# HackerboatControlBoard.net
KiCad netlist of a schematic drawn in EAGLE
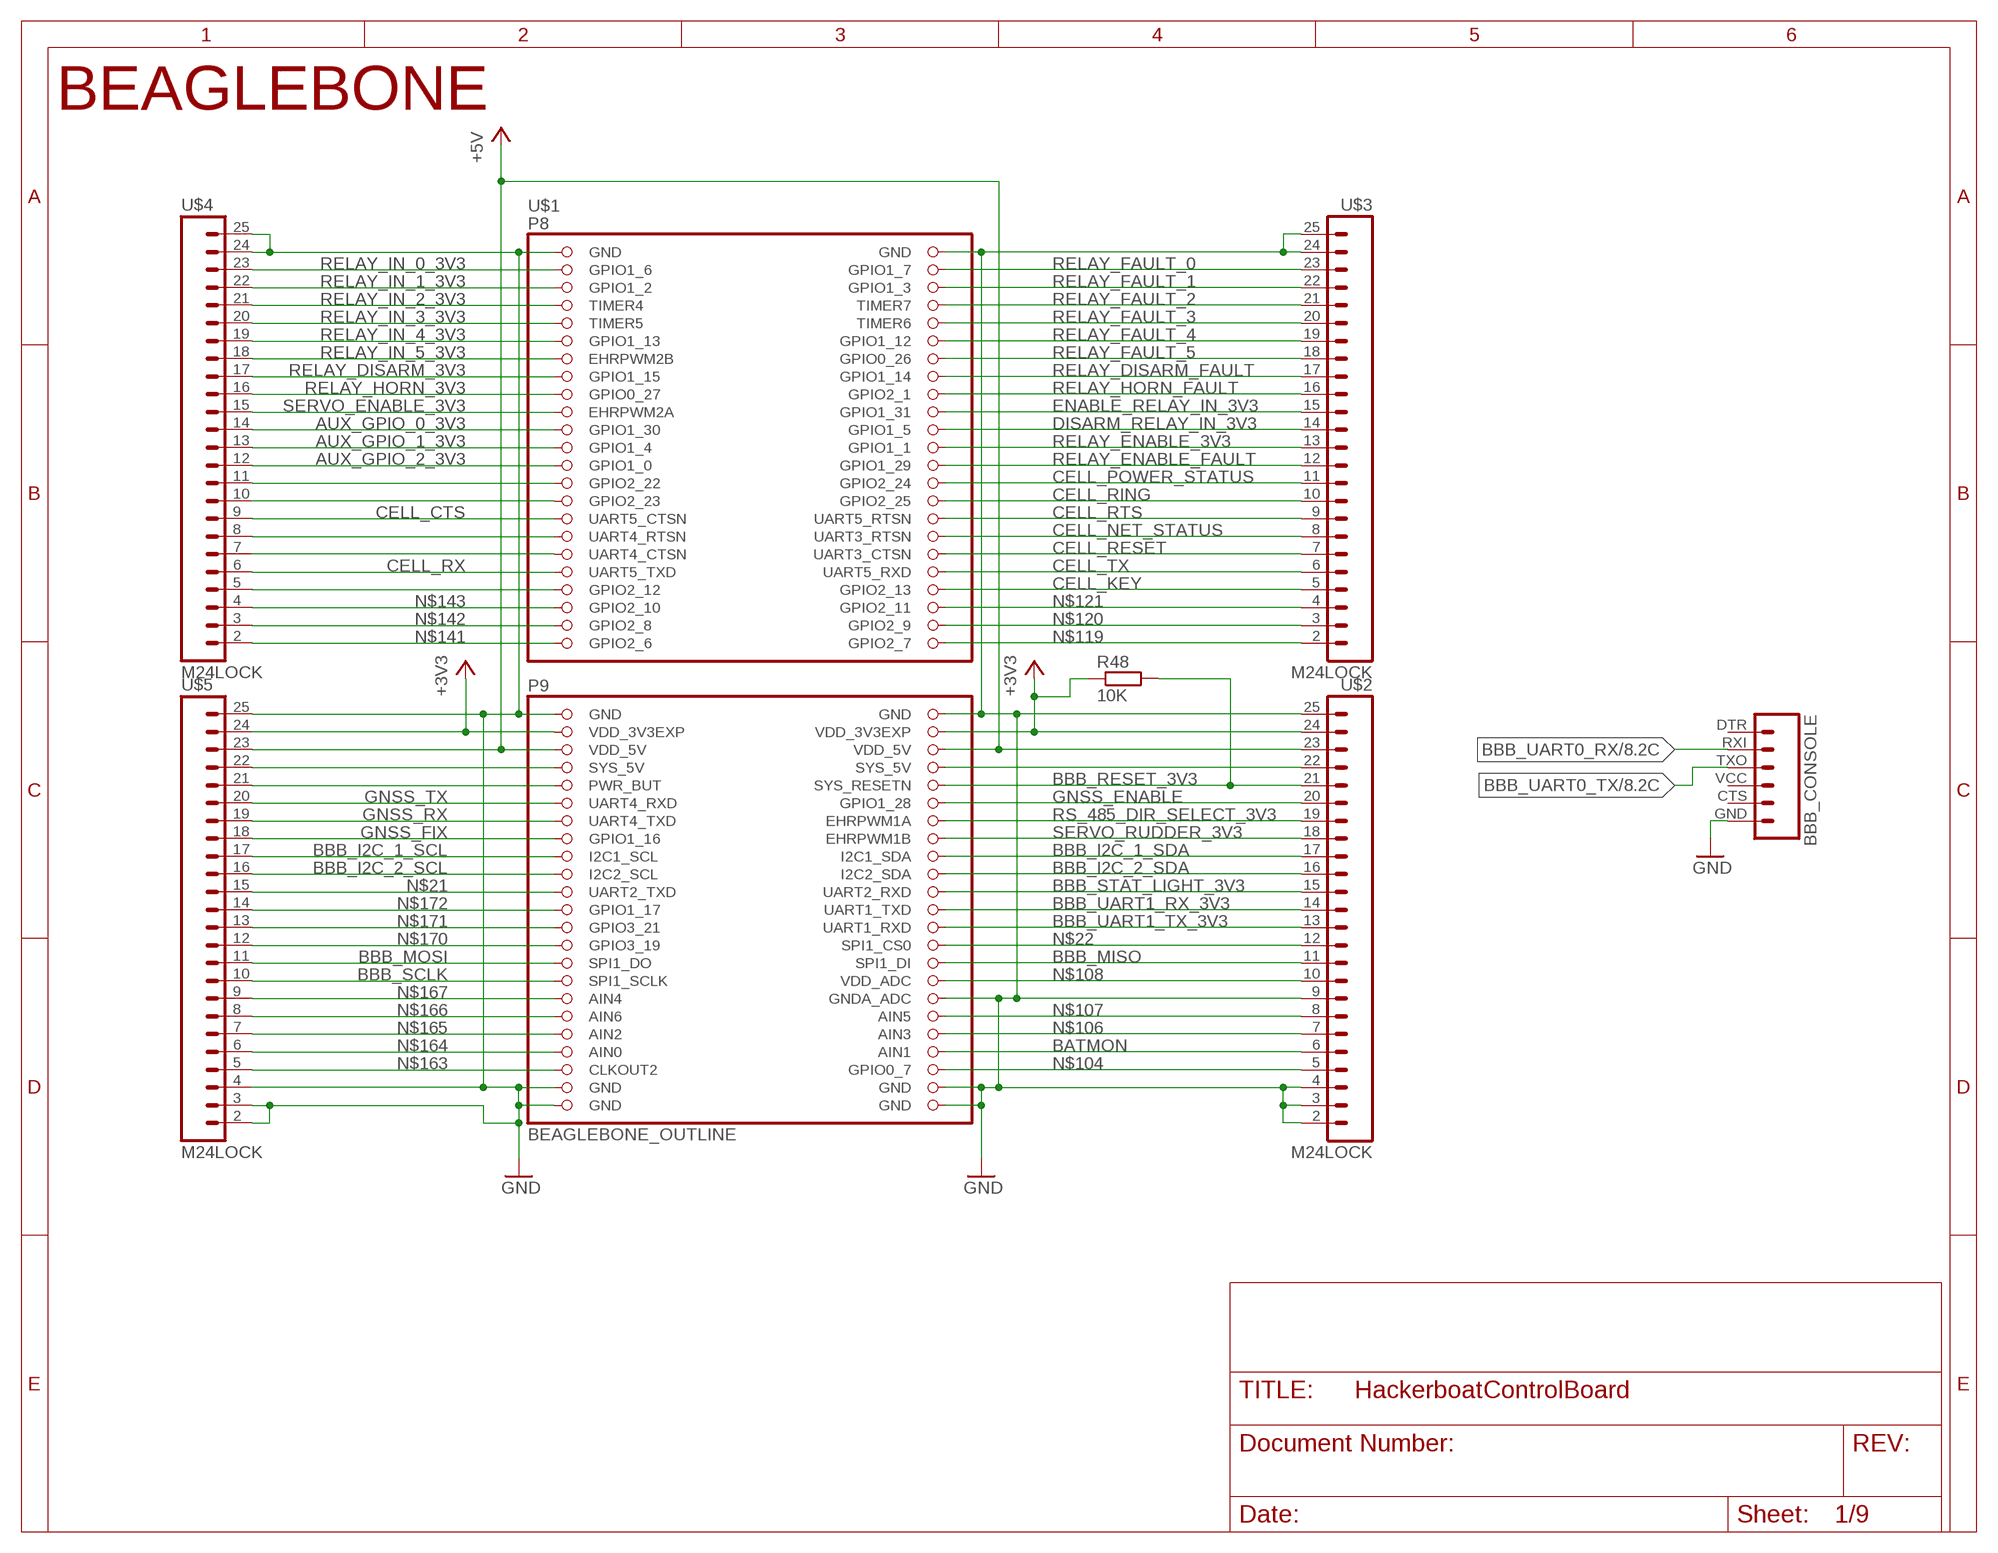
[diagram p0: schematic, sheet 1]
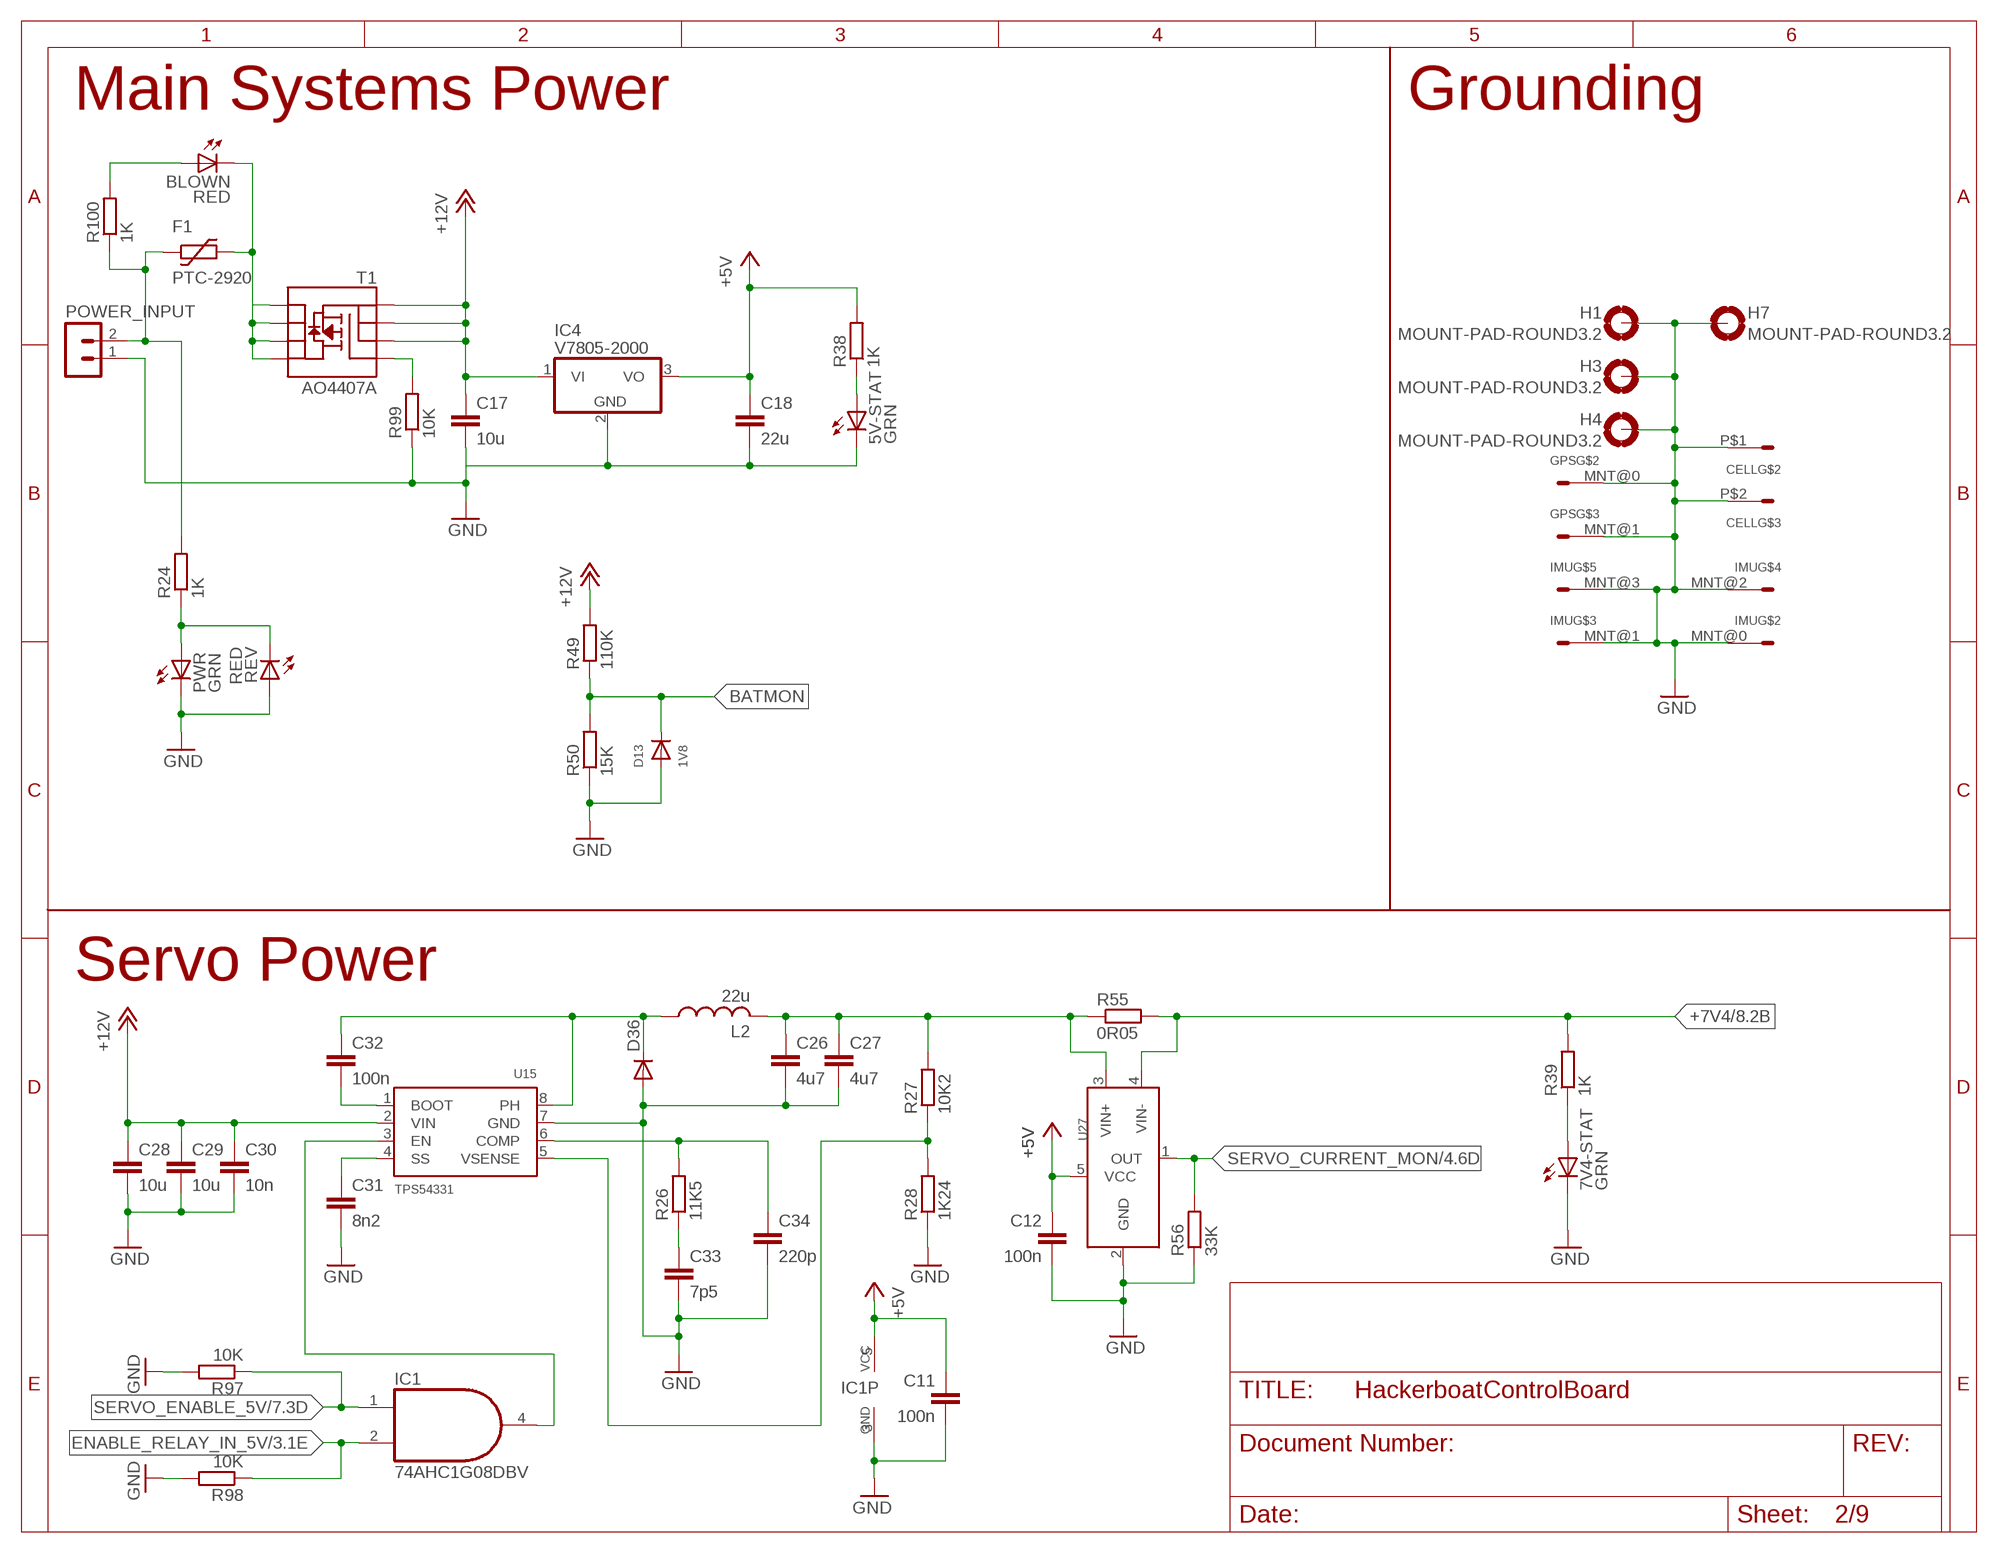
[diagram p1: schematic, sheet 2]
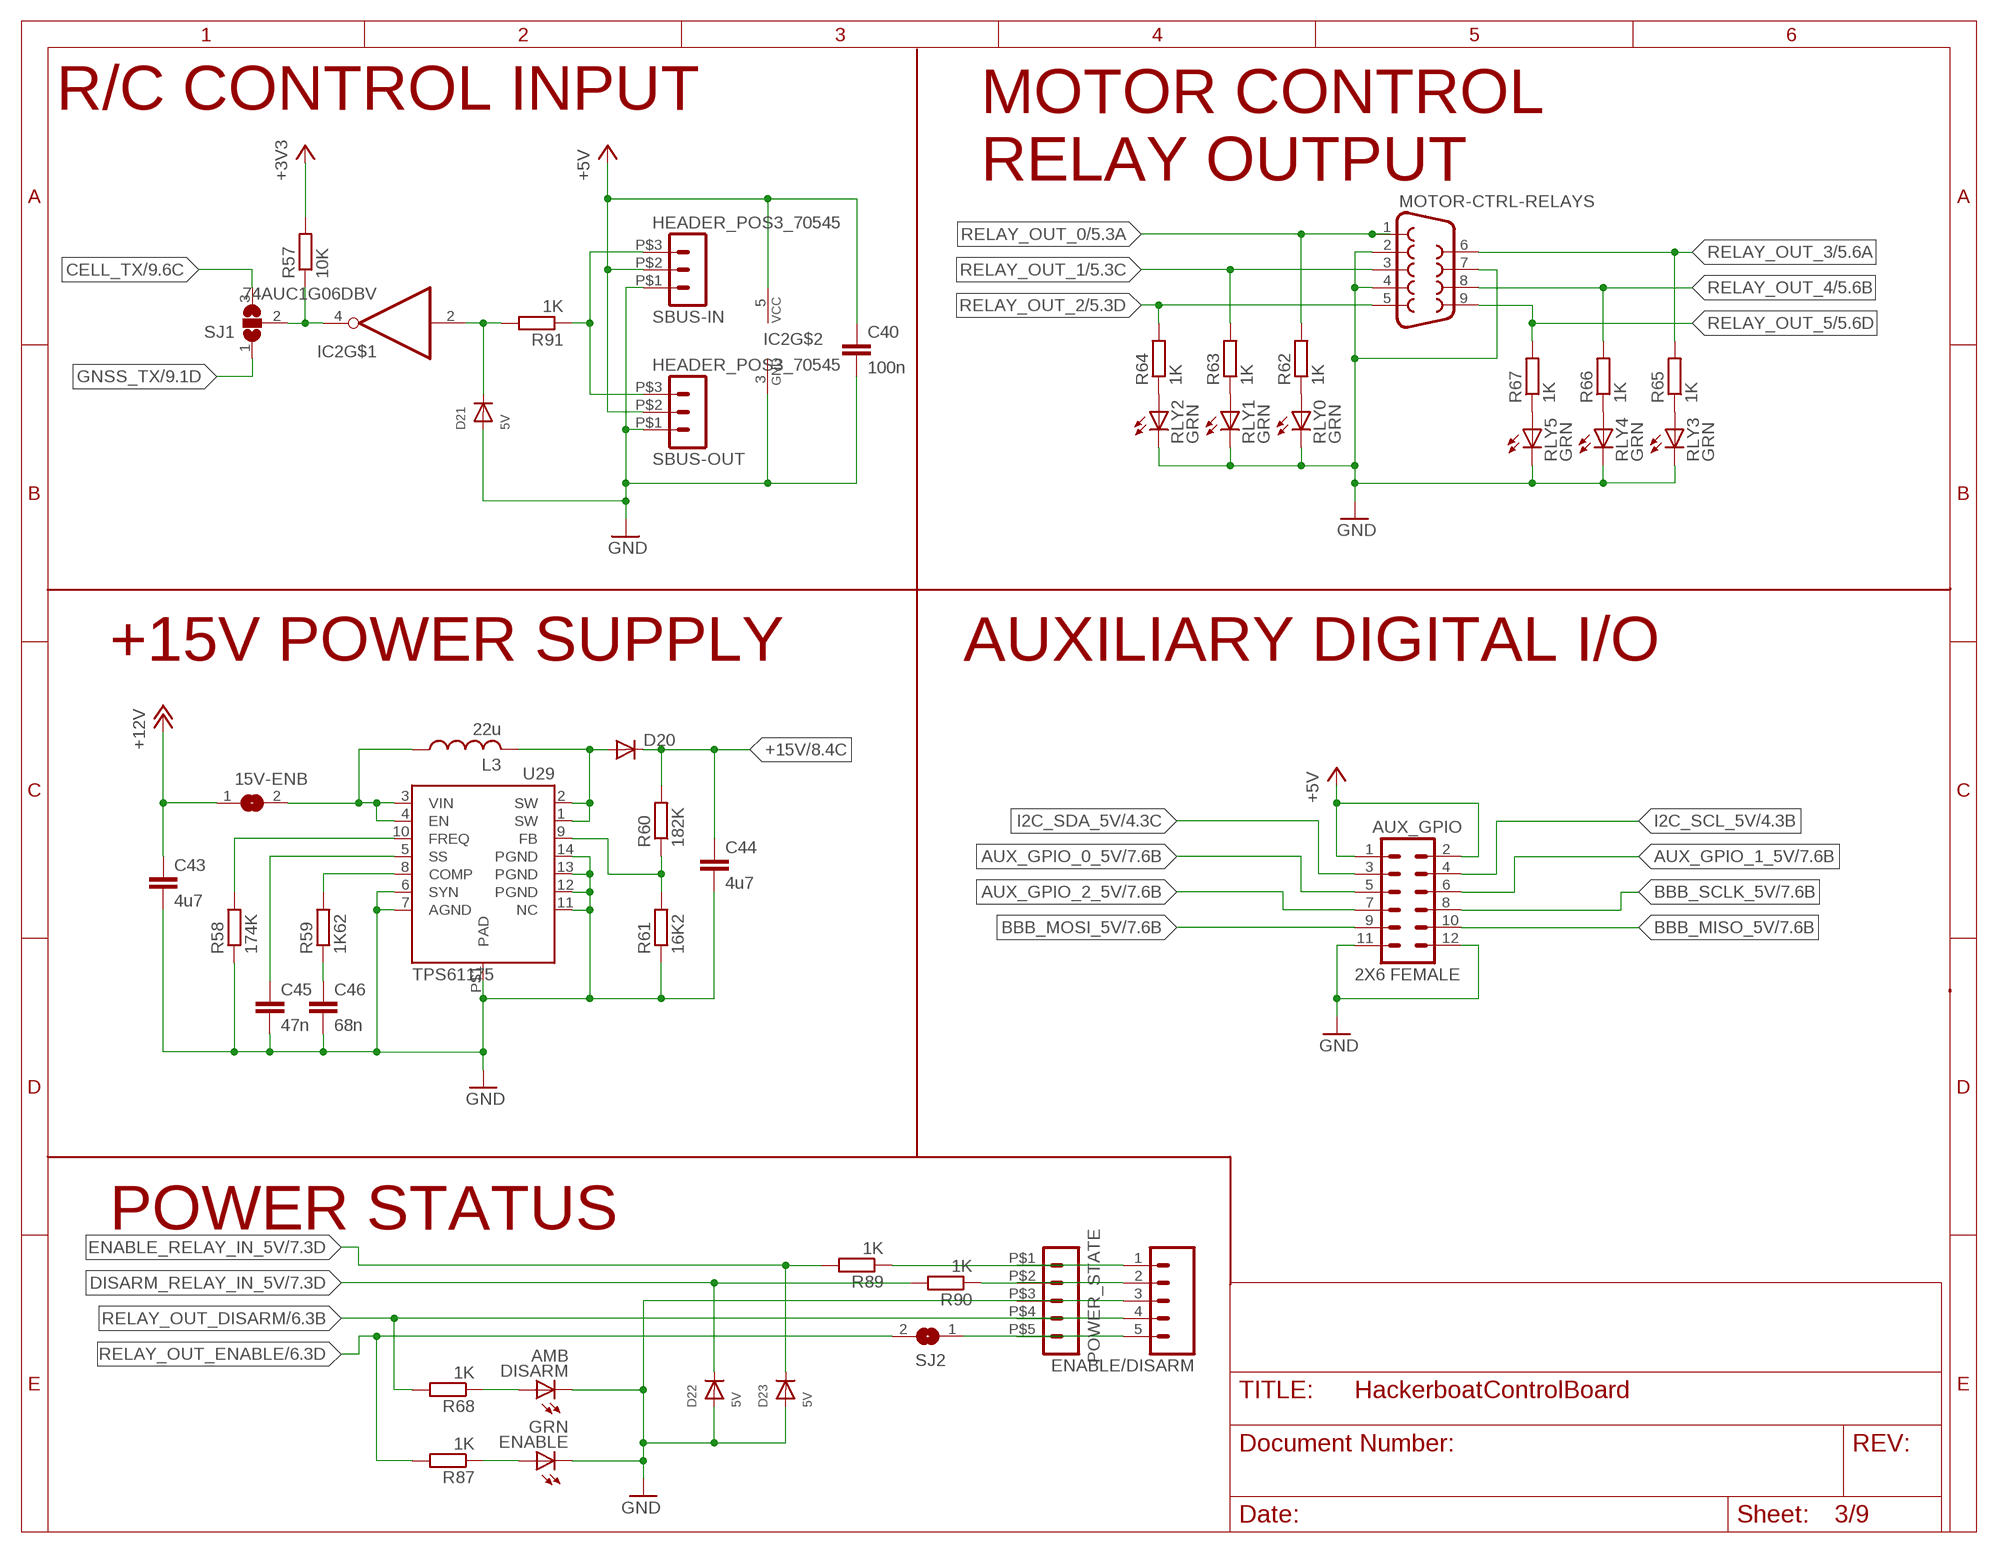
[diagram p2: schematic, sheet 3]
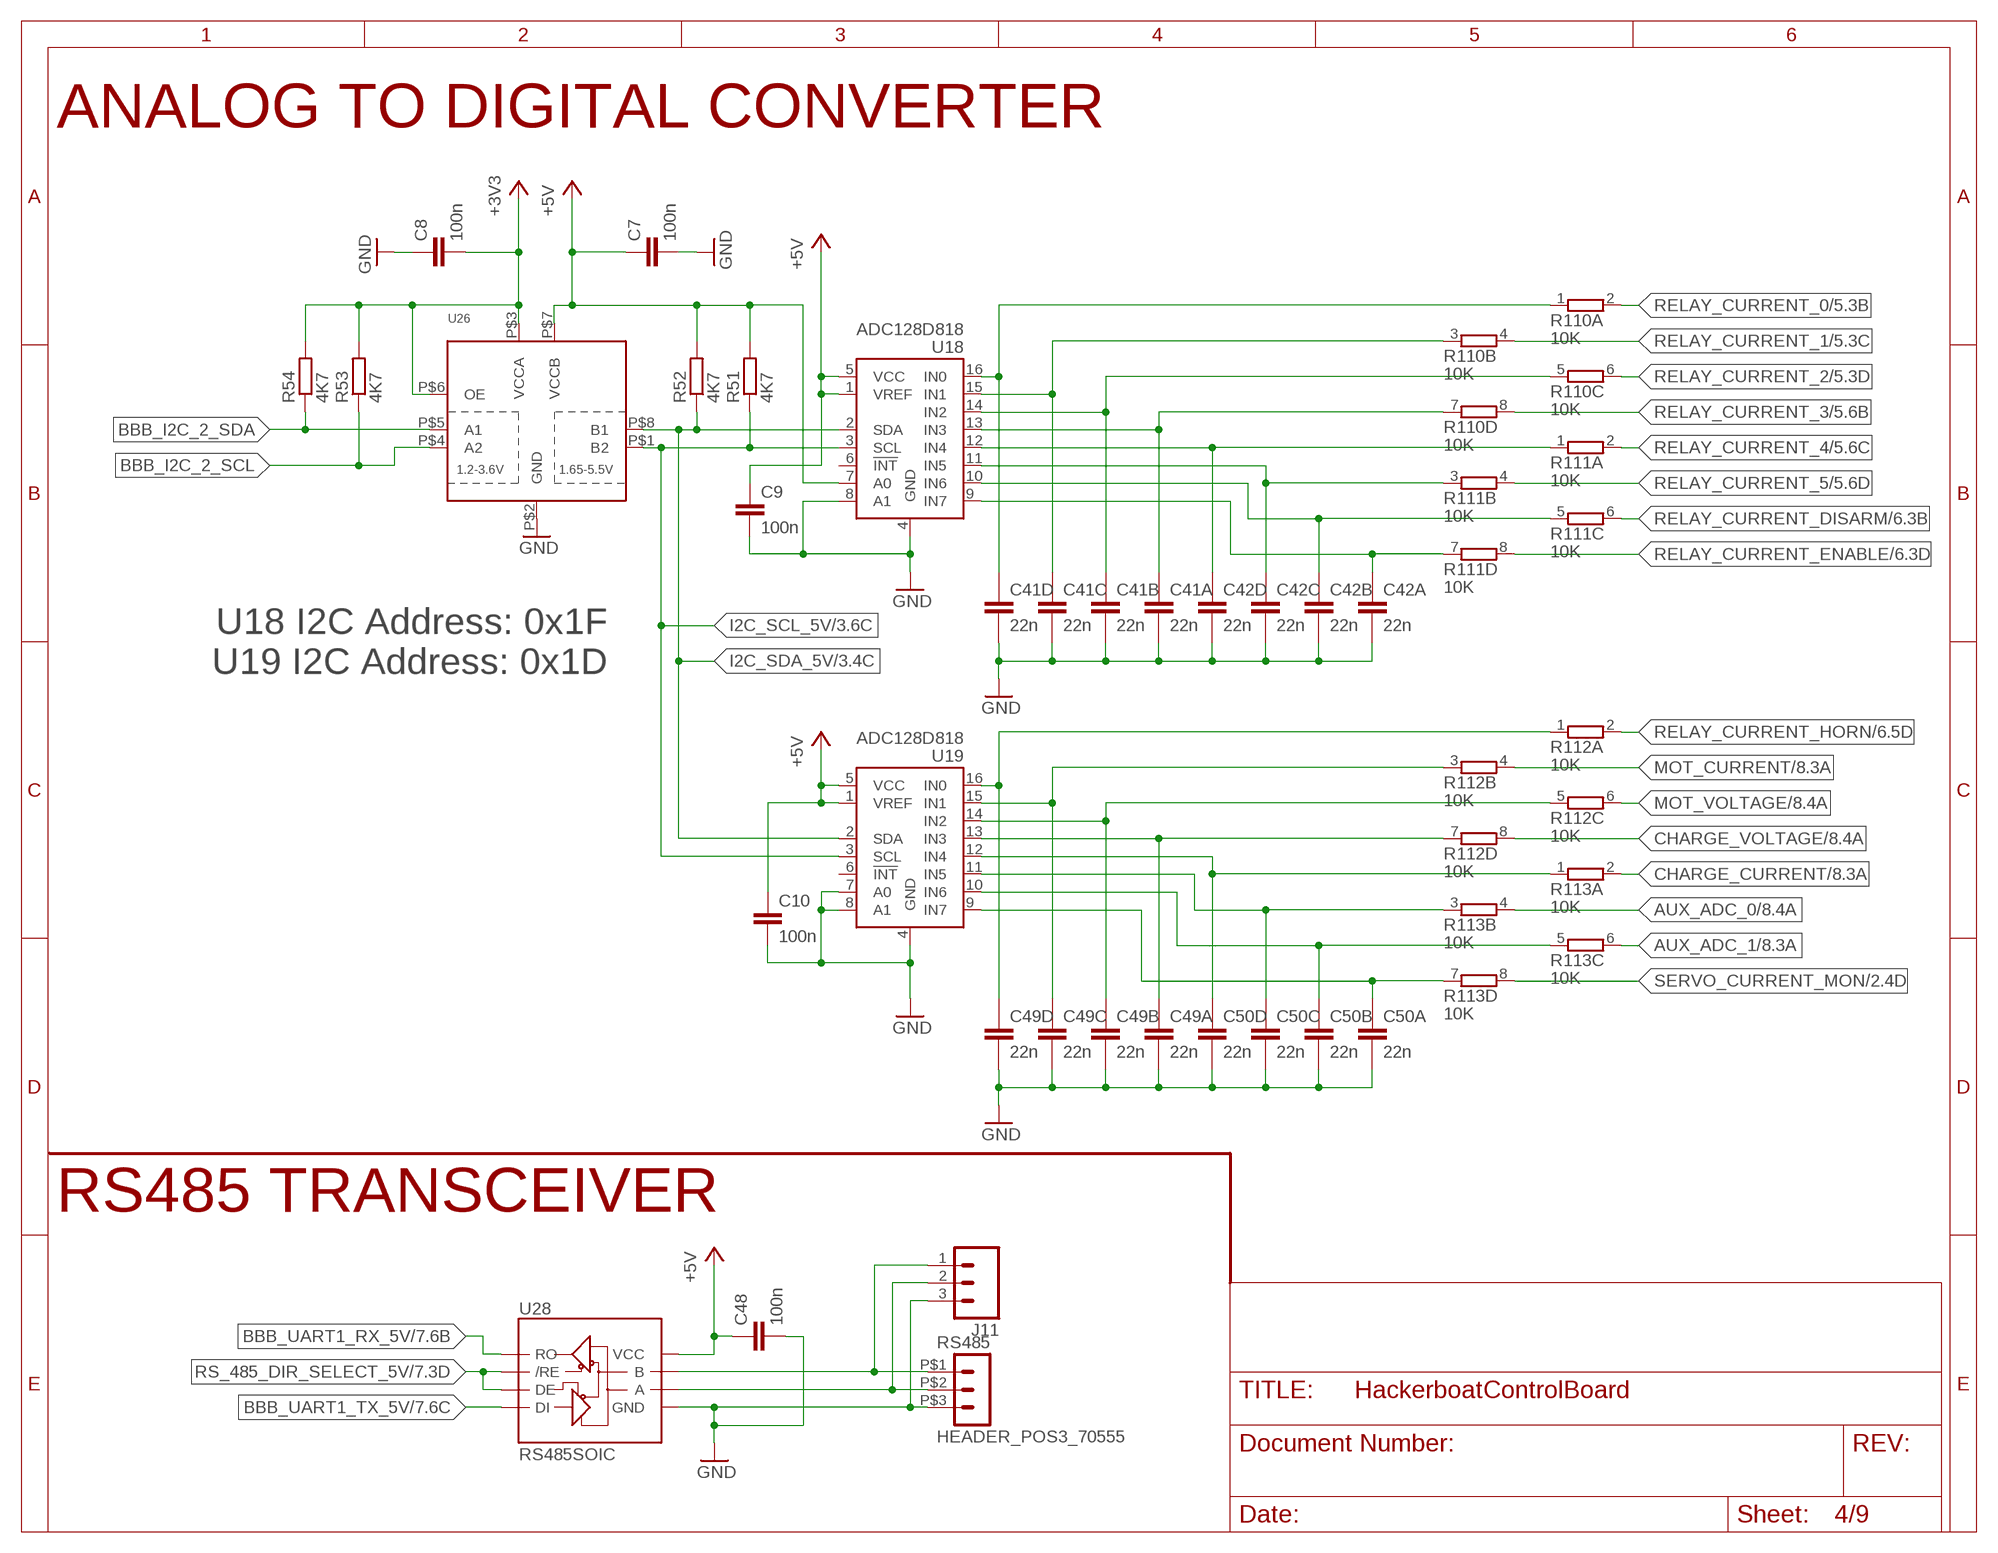
[diagram p3: schematic, sheet 4]
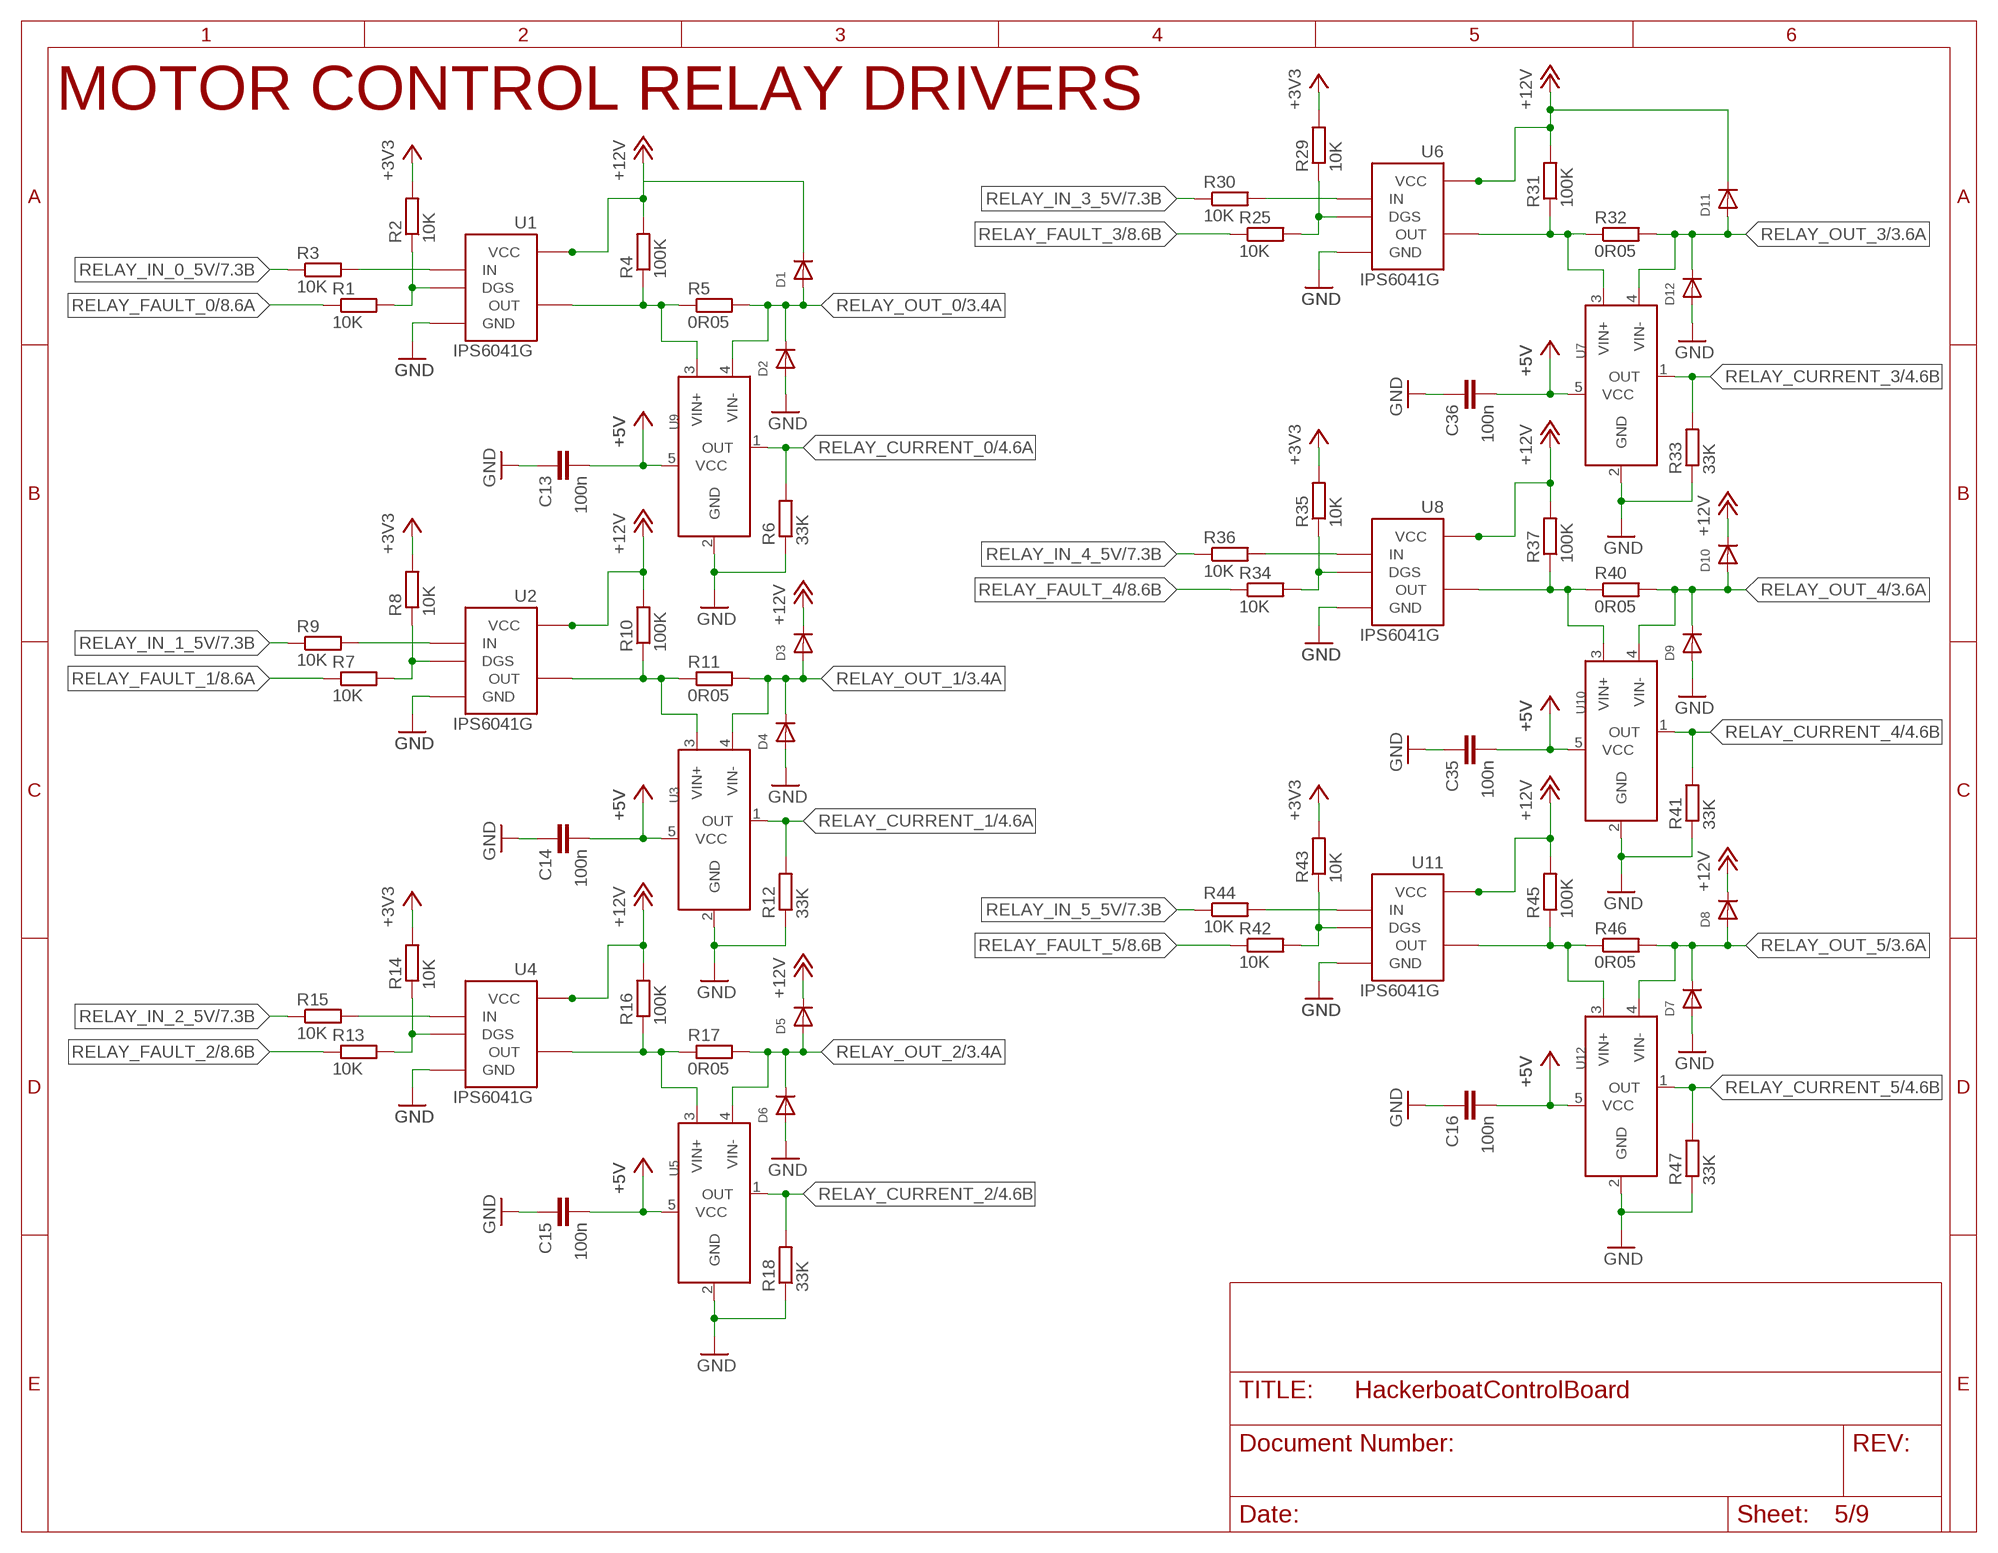
[diagram p4: schematic, sheet 5]
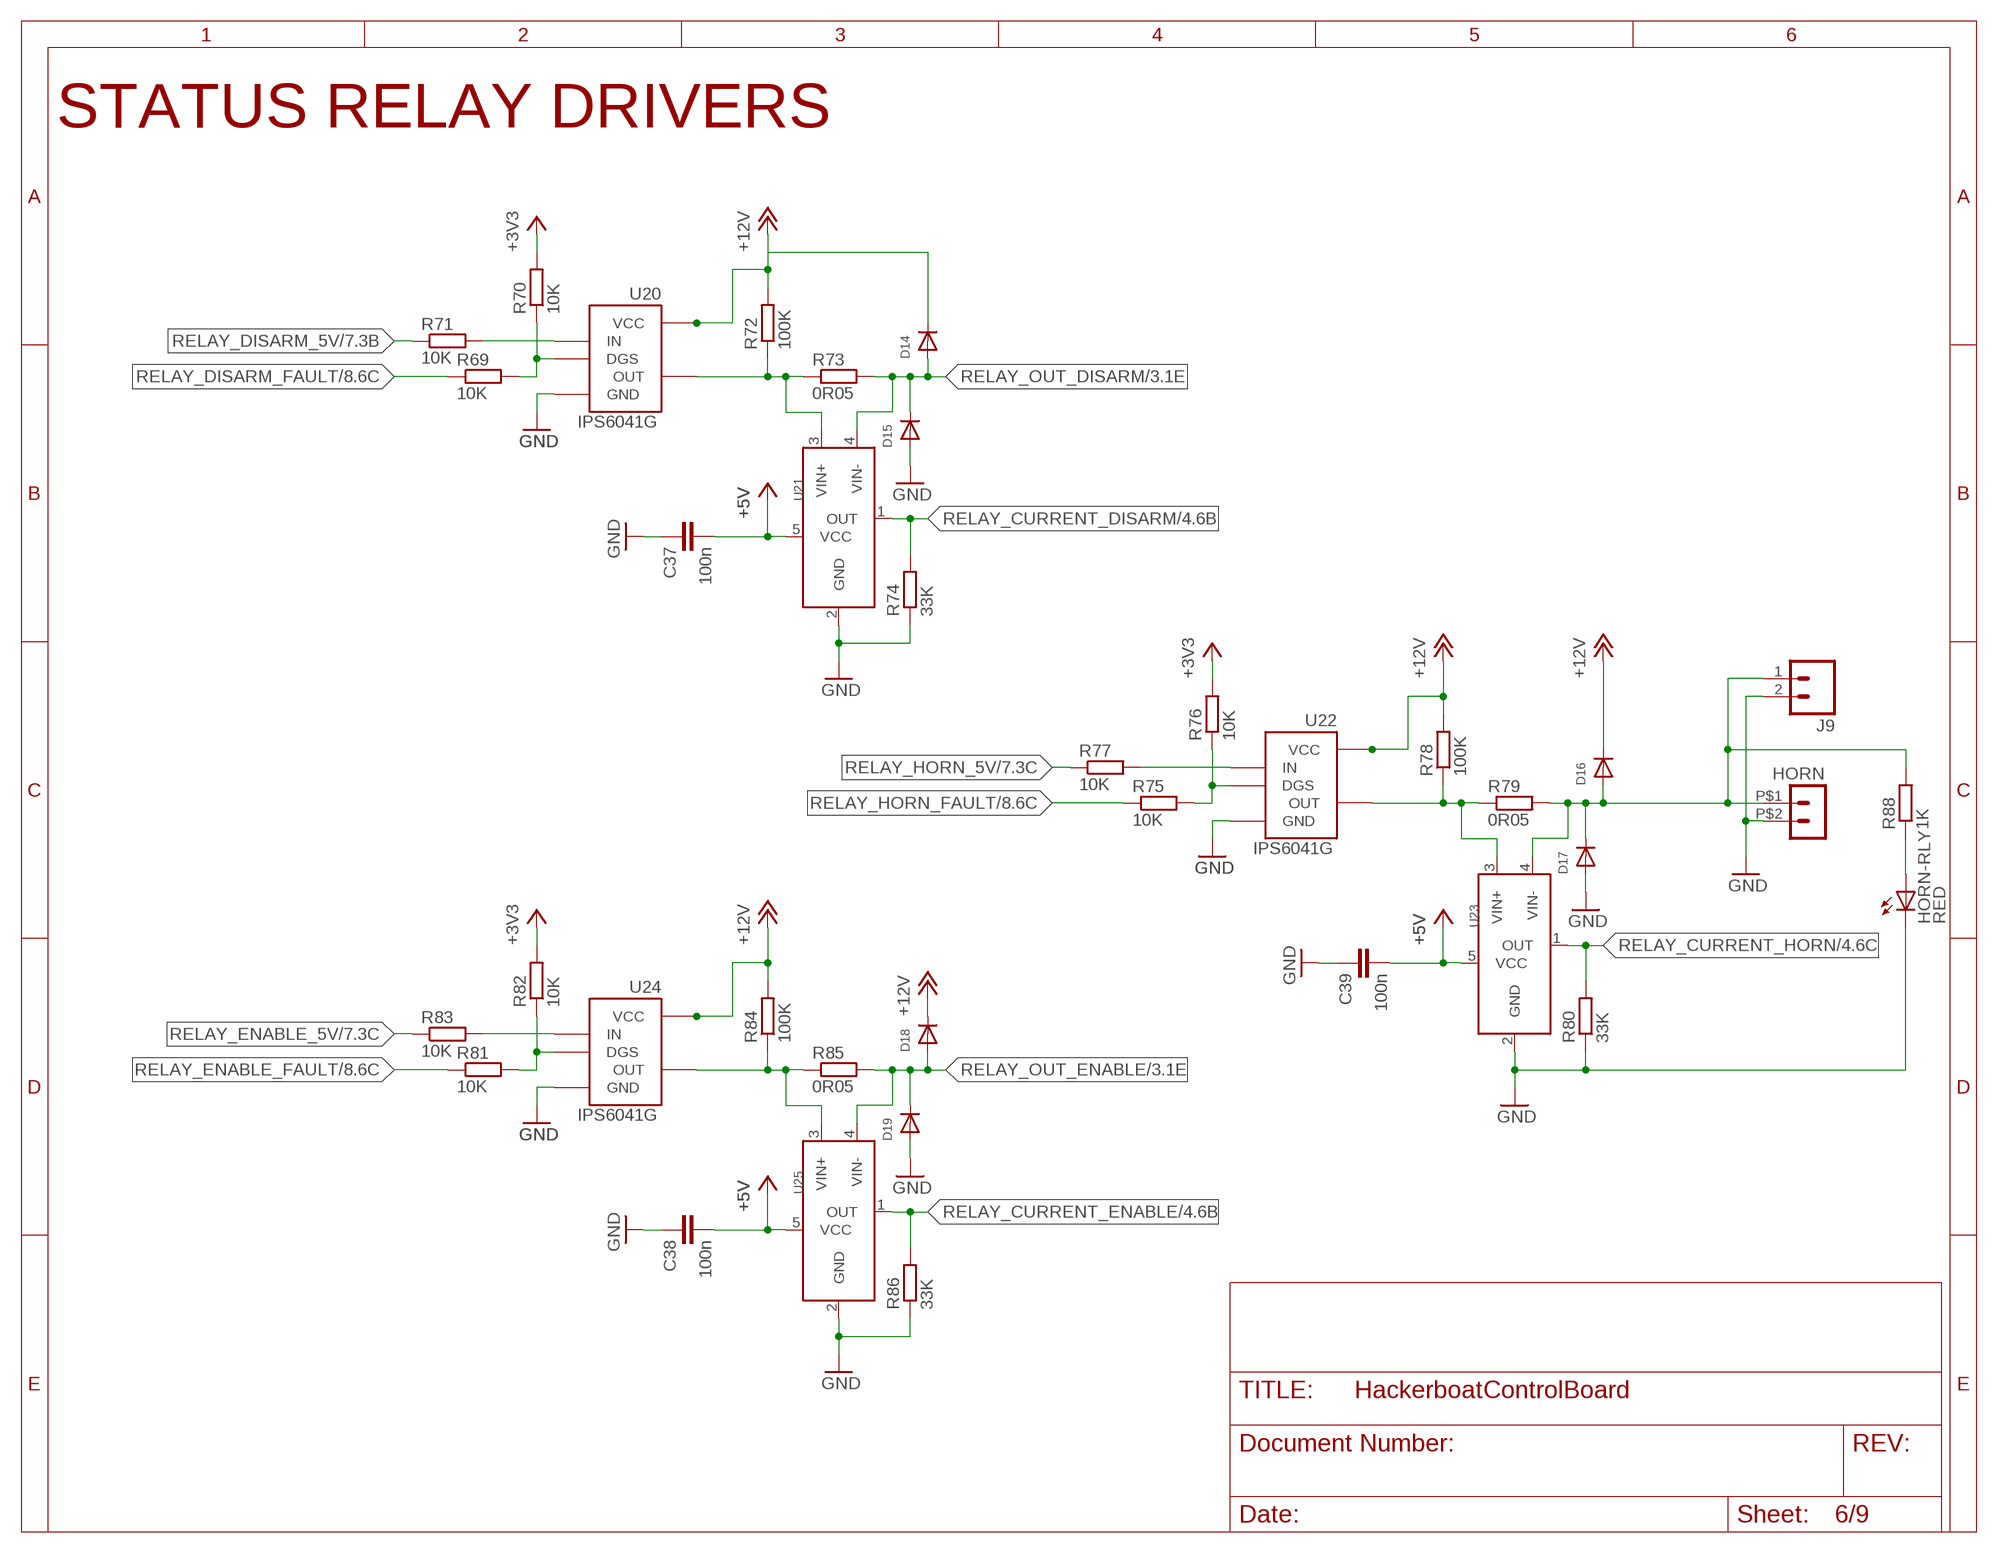
[diagram p5: schematic, sheet 6]
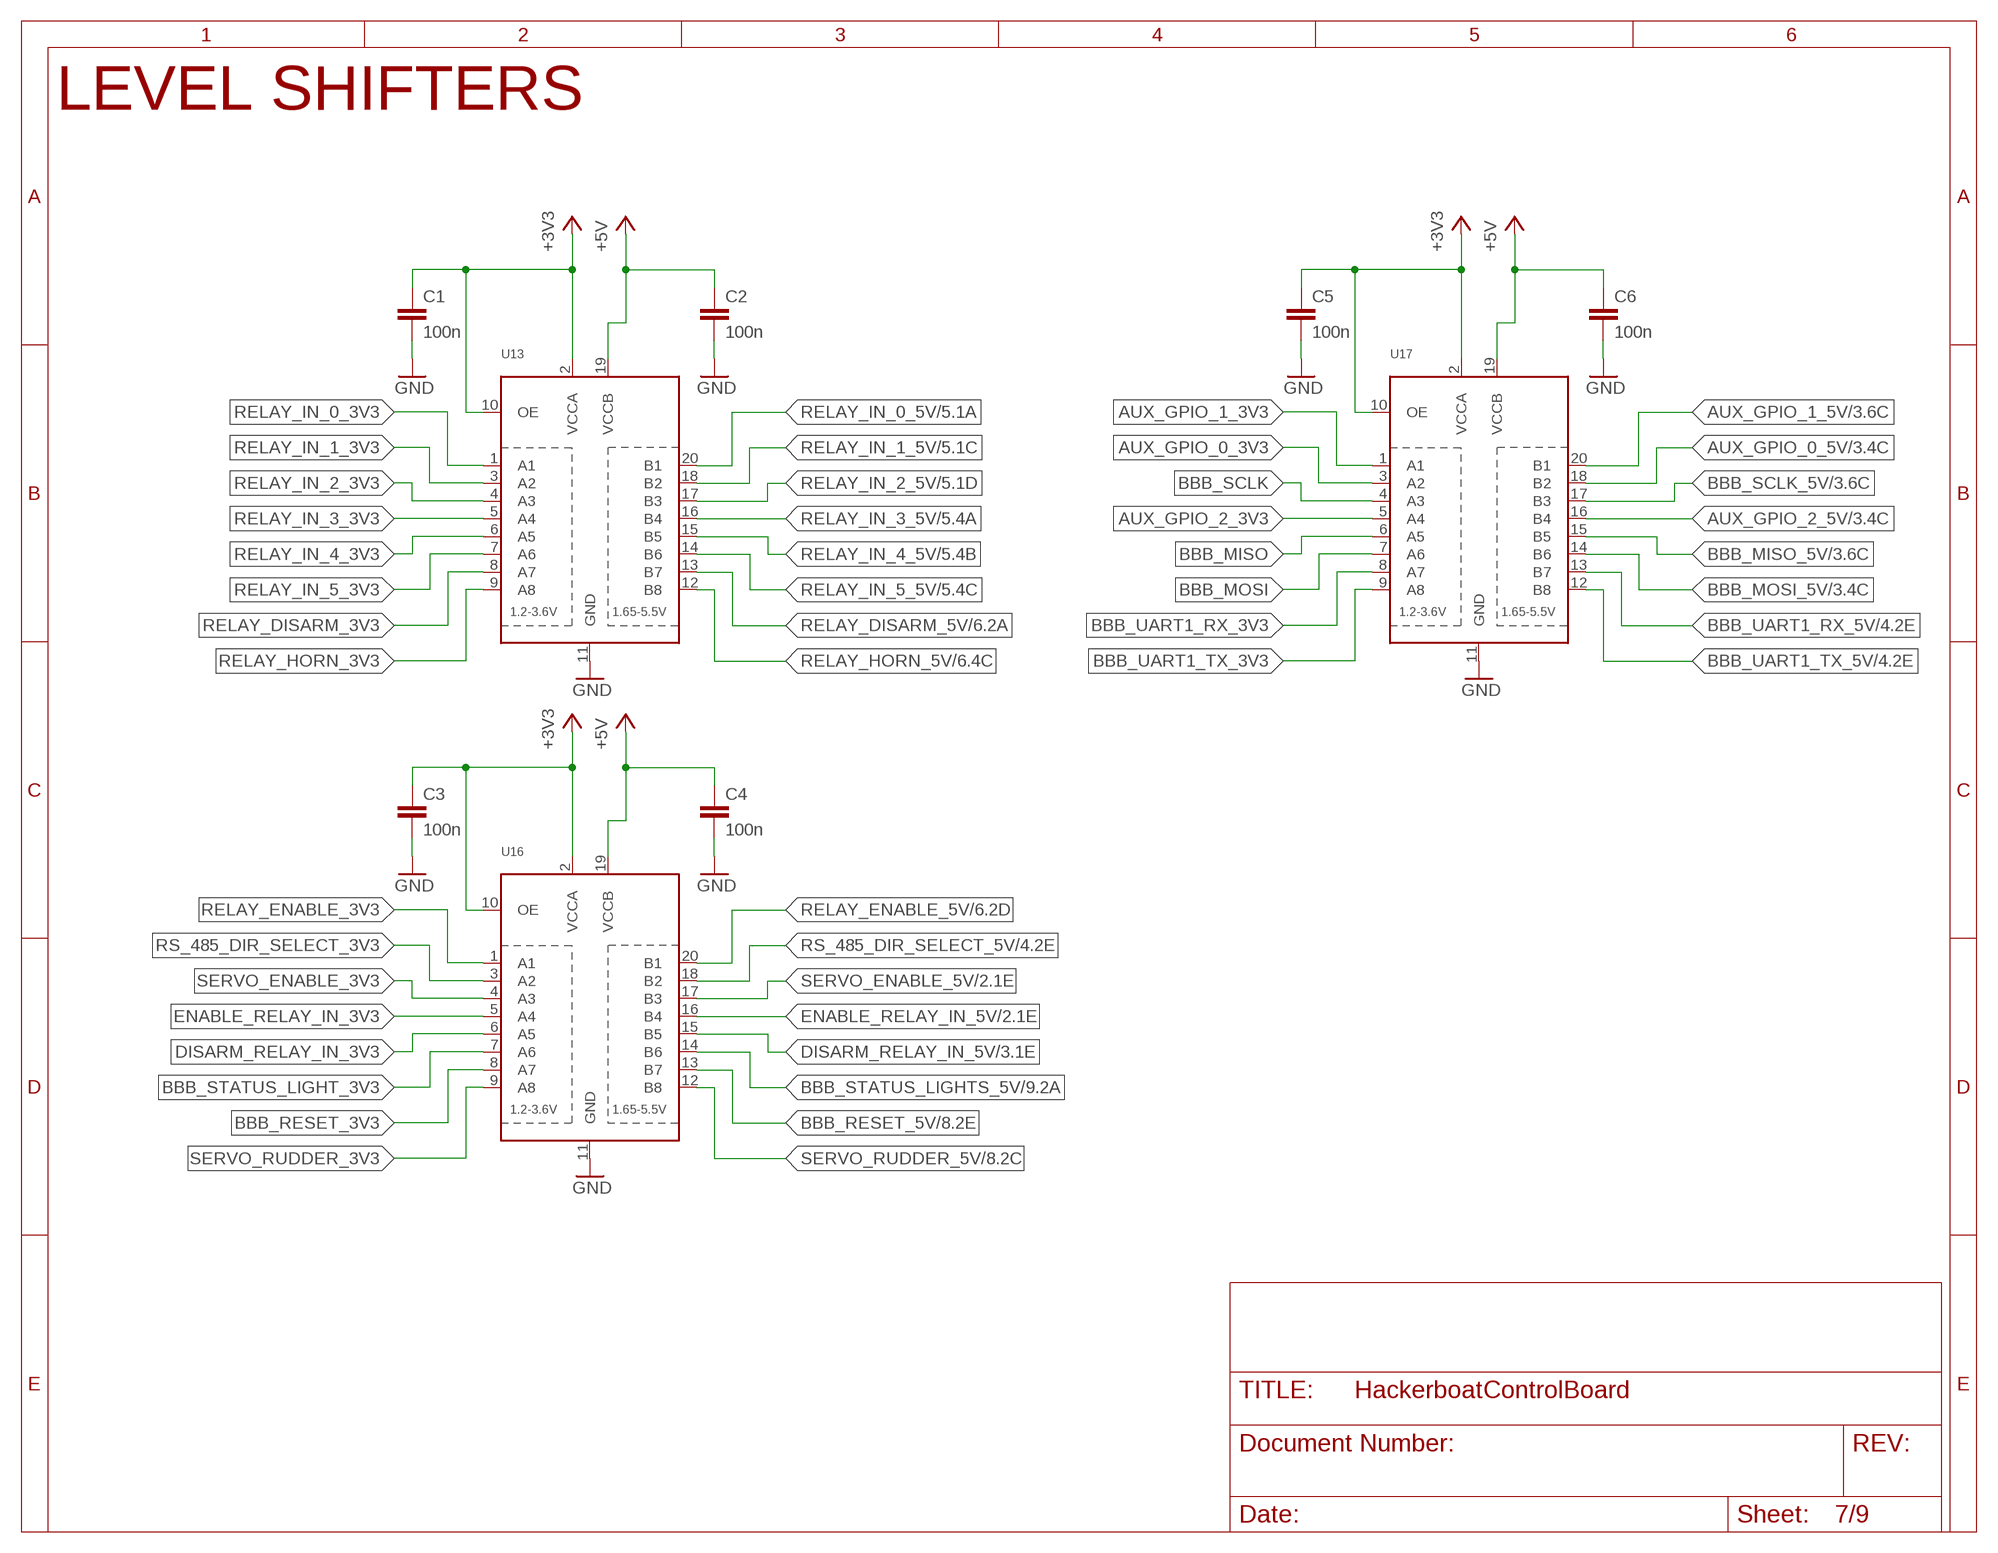
[diagram p6: schematic, sheet 7]
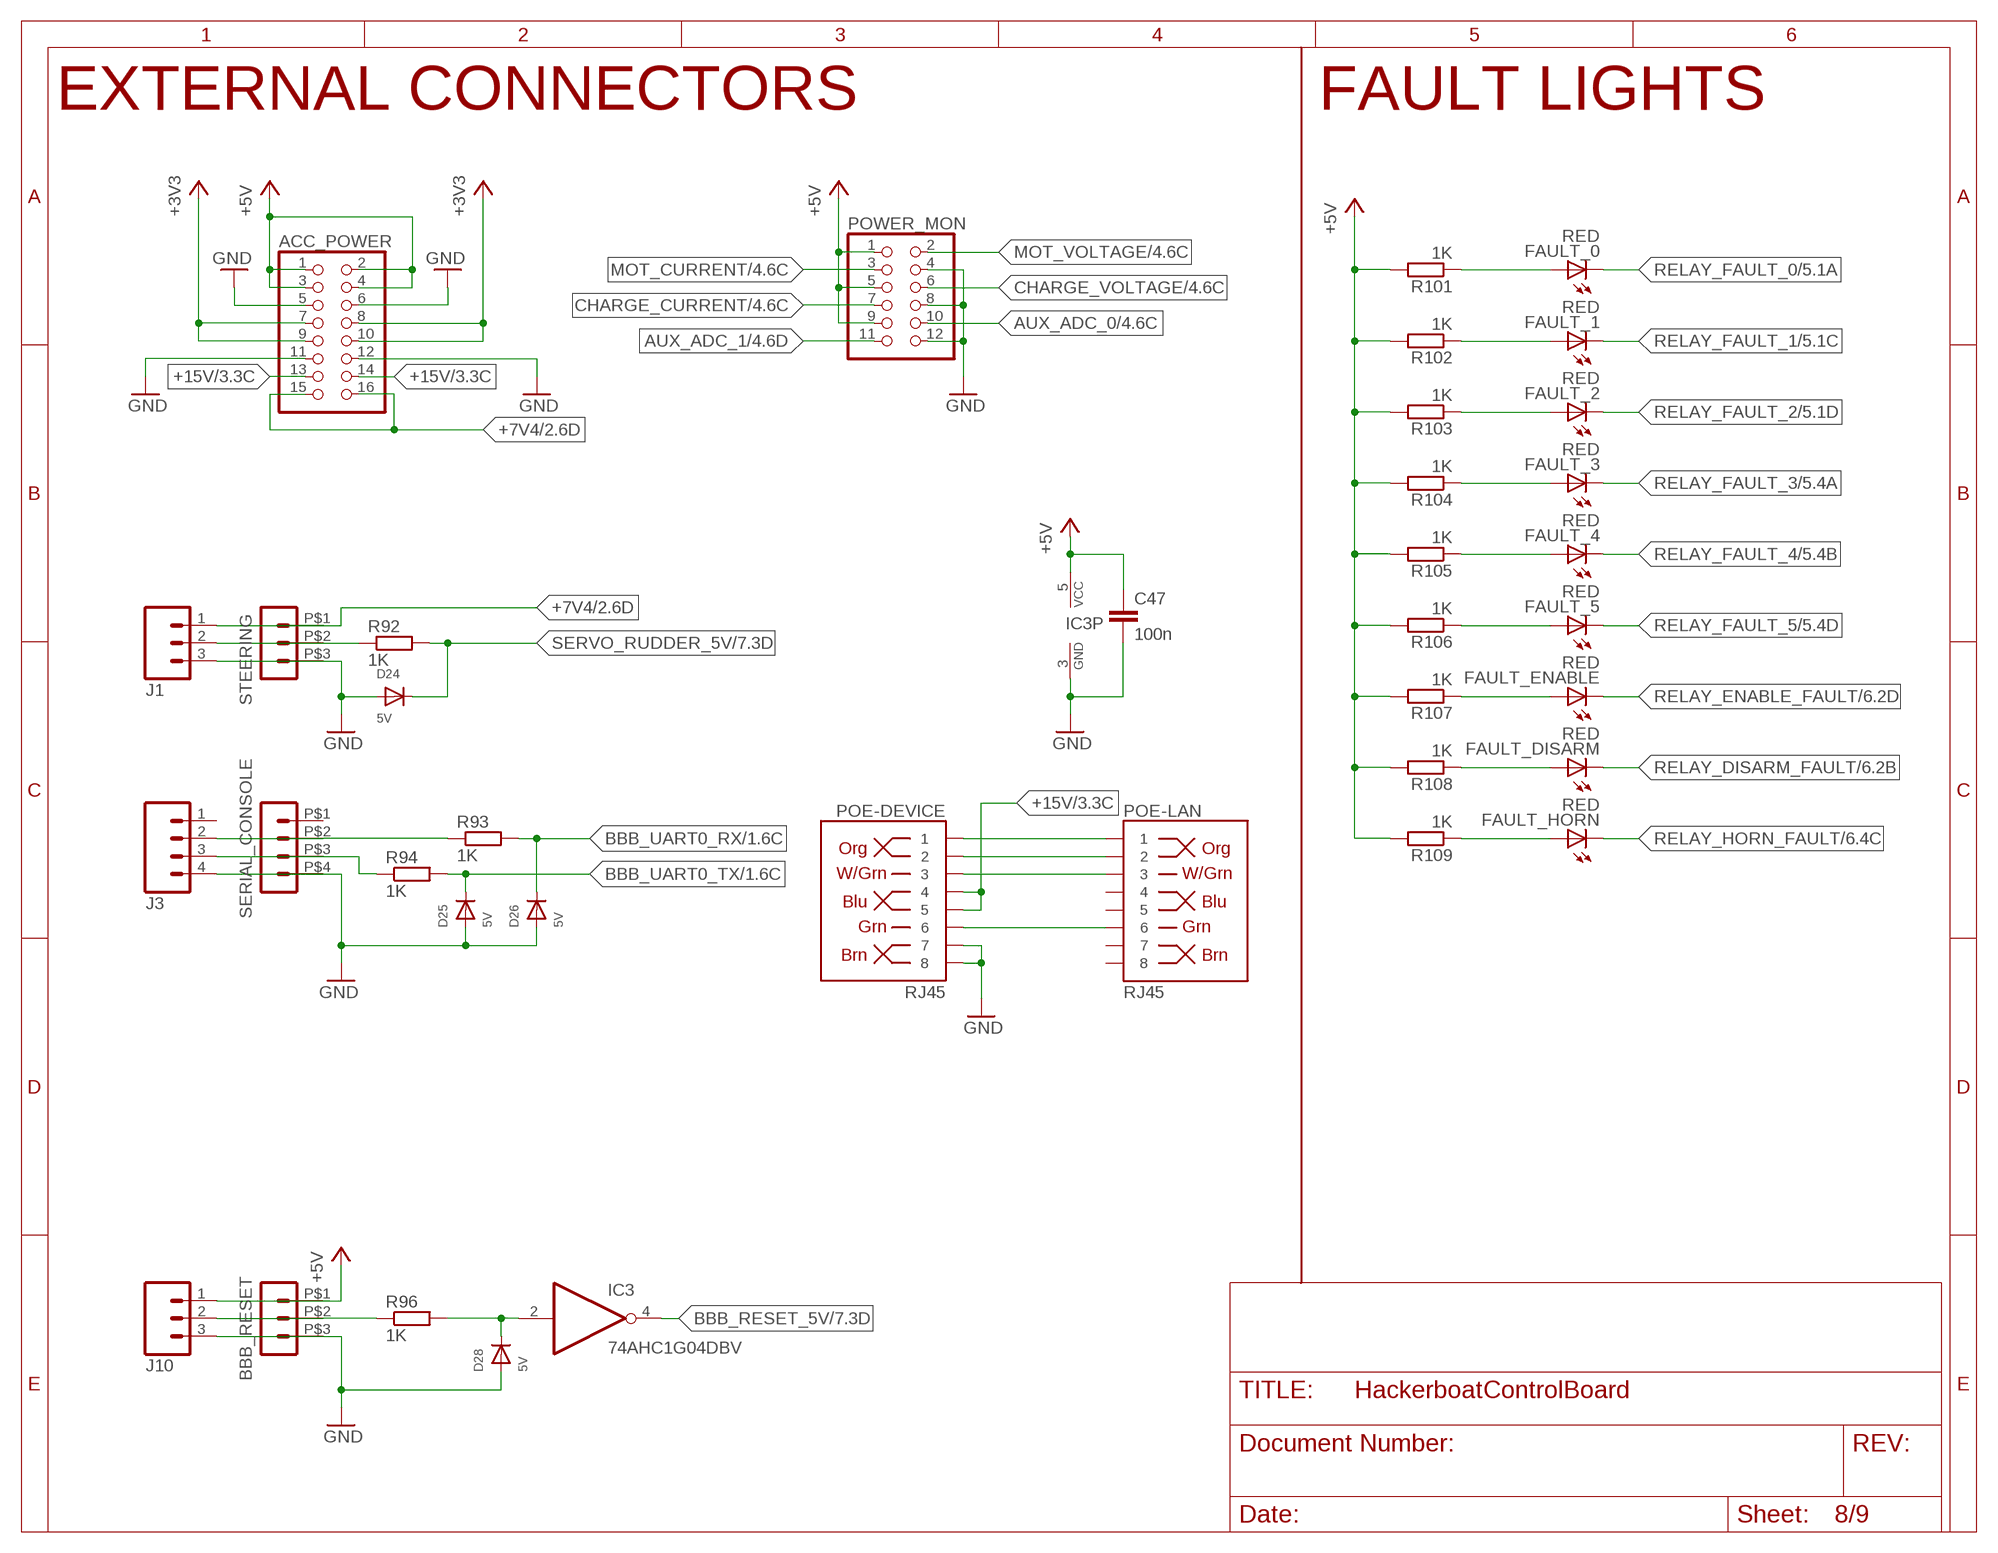
[diagram p7: schematic, sheet 8]
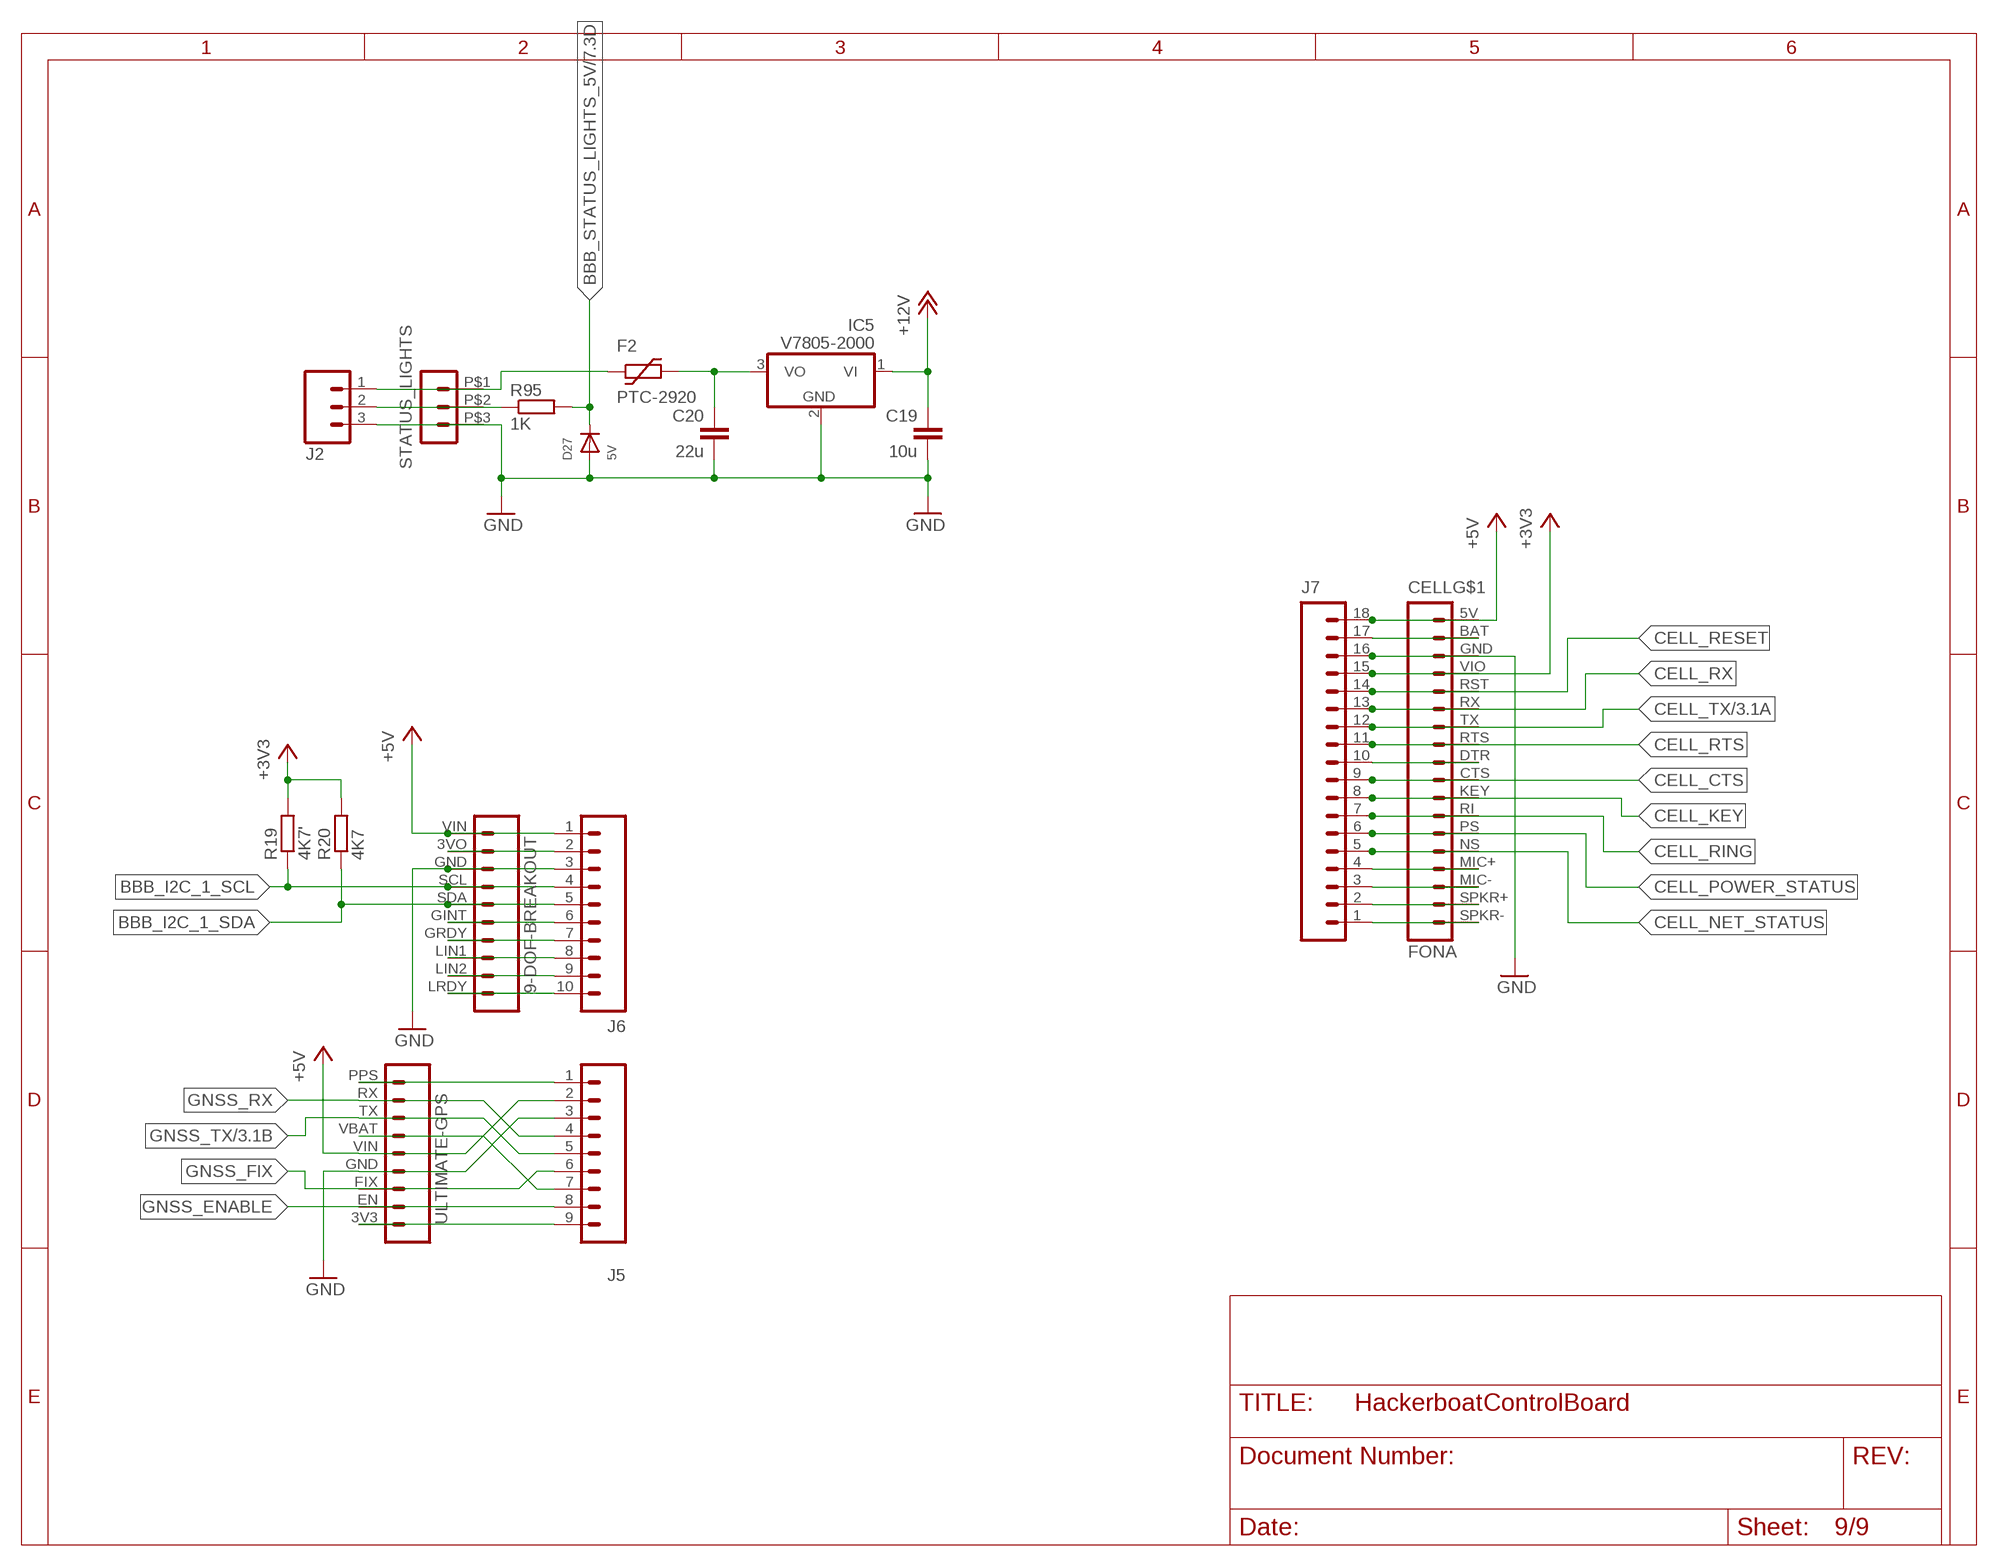
[diagram p8: schematic, sheet 9]

(export (version "E")
  (design (tool "Eeschema 10.0.6"))
  (components
    (comp (ref "5V-STAT")
      (value "GRN")
      (footprint "eagle-import:CHIPLED_0805")
      (fields (field (name "PARTNO") "LG R971-KN-1"))
      (libsource (lib "eagle-import") (part "LEDCHIPLED_0805"))
    )
    (comp (ref "7V4-STAT")
      (value "GRN")
      (footprint "eagle-import:CHIPLED_0805")
      (fields (field (name "PARTNO") "LG R971-KN-1"))
      (libsource (lib "eagle-import") (part "LEDCHIPLED_0805"))
    )
    (comp (ref "BLOWN")
      (value "RED")
      (footprint "eagle-import:CHIPLED_0805")
      (fields (field (name "PARTNO") "LH R974-LP-1"))
      (libsource (lib "eagle-import") (part "LEDCHIPLED_0805"))
    )
    (comp (ref "C11")
      (value "100n")
      (footprint "eagle-import:C0603")
      (fields (field (name "PARTNO") "CC0603KRX7R9BB104"))
      (libsource (lib "eagle-import") (part "C-EUC0603"))
    )
    (comp (ref "C12")
      (value "100n")
      (footprint "eagle-import:C0603")
      (fields (field (name "PARTNO") "CC0603KRX7R9BB104"))
      (libsource (lib "eagle-import") (part "C-EUC0603"))
    )
    (comp (ref "C17")
      (value "10u")
      (footprint "eagle-import:C1210")
      (fields (field (name "PARTNO") "UMK325BJ106MM"))
      (libsource (lib "eagle-import") (part "C-EUC1210"))
    )
    (comp (ref "C18")
      (value "22u")
      (footprint "eagle-import:C1210")
      (fields (field (name "PARTNO") "GRM32ER61E226KE15K"))
      (libsource (lib "eagle-import") (part "C-EUC1210"))
    )
    (comp (ref "C26")
      (value "4u7")
      (footprint "eagle-import:C1210")
      (fields (field (name "PARTNO") "UMK325F475ZH"))
      (libsource (lib "eagle-import") (part "C-EUC1210"))
    )
    (comp (ref "C27")
      (value "4u7")
      (footprint "eagle-import:C1210")
      (fields (field (name "PARTNO") "UMK325F475ZH"))
      (libsource (lib "eagle-import") (part "C-EUC1210"))
    )
    (comp (ref "C28")
      (value "10u")
      (footprint "eagle-import:C1210")
      (fields (field (name "PARTNO") "UMK325BJ106MM"))
      (libsource (lib "eagle-import") (part "C-EUC1210"))
    )
    (comp (ref "C29")
      (value "10u")
      (footprint "eagle-import:C1210")
      (fields (field (name "PARTNO") "UMK325BJ106MM"))
      (libsource (lib "eagle-import") (part "C-EUC1210"))
    )
    (comp (ref "C30")
      (value "10n")
      (footprint "eagle-import:C0603")
      (fields (field (name "PARTNO") "CL10B103KB8NCNC"))
      (libsource (lib "eagle-import") (part "C-EUC0603"))
    )
    (comp (ref "C31")
      (value "8n2")
      (footprint "eagle-import:C0603")
      (fields (field (name "PARTNO") "CL10B822KB8SFNC"))
      (libsource (lib "eagle-import") (part "C-EUC0603"))
    )
    (comp (ref "C32")
      (value "100n")
      (footprint "eagle-import:C0603")
      (fields (field (name "PARTNO") "CC0603KRX7R9BB104"))
      (libsource (lib "eagle-import") (part "C-EUC0603"))
    )
    (comp (ref "C33")
      (value "7p5")
      (footprint "eagle-import:C0603")
      (fields (field (name "PARTNO") "CL10C7R5DB8NNNC"))
      (libsource (lib "eagle-import") (part "C-EUC0603"))
    )
    (comp (ref "C34")
      (value "220p")
      (footprint "eagle-import:C0603")
      (fields (field (name "PARTNO") "CL10B221KC8WPNC"))
      (libsource (lib "eagle-import") (part "C-EUC0603"))
    )
    (comp (ref "CELL")
      (value "FONA")
      (footprint "eagle-import:FONA-3G")
      (fields (field (name "PARTNO") "BCS-118-L-S-TE"))
      (libsource (lib "eagle-import") (part "FONA"))
    )
    (comp (ref "D13")
      (value "1V8")
      (footprint "eagle-import:SOD-123")
      (fields (field (name "PARTNO") "MMSZ4678-TP"))
      (libsource (lib "eagle-import") (part "DIODESOD-123"))
    )
    (comp (ref "D36")
      (value "SPARKFUN_DIODESMA")
      (footprint "eagle-import:SPARKFUN_SMA-DIODE")
      (fields (field (name "PARTNO") "SK310A-LTP"))
      (libsource (lib "eagle-import") (part "SPARKFUN_DIODESMA"))
    )
    (comp (ref "F1")
      (value "PTC-2920")
      (footprint "eagle-import:2920L")
      (fields (field (name "PARTNO") "MF-LSMF300/24X-2"))
      (libsource (lib "eagle-import") (part "PTC-2920"))
    )
    (comp (ref "GPS")
      (value "ULTIMATE-GPS")
      (footprint "eagle-import:ULTIMATE-GPS")
      (fields (field (name "PARTNO") "BCS-109-L-S-TE"))
      (libsource (lib "eagle-import") (part "ULTIMATE-GPS"))
    )
    (comp (ref "H1")
      (value "MOUNT-PAD-ROUND3.2")
      (footprint "eagle-import:3,2-PAD")
      (fields (field (name "PARTNO") "?"))
      (libsource (lib "eagle-import") (part "MOUNT-PAD-ROUND3.2"))
    )
    (comp (ref "H3")
      (value "MOUNT-PAD-ROUND3.2")
      (footprint "eagle-import:3,2-PAD")
      (fields (field (name "PARTNO") "?"))
      (libsource (lib "eagle-import") (part "MOUNT-PAD-ROUND3.2"))
    )
    (comp (ref "H4")
      (value "MOUNT-PAD-ROUND3.2")
      (footprint "eagle-import:3,2-PAD")
      (fields (field (name "PARTNO") "?"))
      (libsource (lib "eagle-import") (part "MOUNT-PAD-ROUND3.2"))
    )
    (comp (ref "H7")
      (value "MOUNT-PAD-ROUND3.2")
      (footprint "eagle-import:3,2-PAD")
      (fields (field (name "PARTNO") "?"))
      (libsource (lib "eagle-import") (part "MOUNT-PAD-ROUND3.2"))
    )
    (comp (ref "IC1")
      (value "74AHC1G08DBV")
      (footprint "eagle-import:SOT23-5")
      (fields (field (name "PARTNO") "MC74HC1G08DTT1G"))
      (libsource (lib "eagle-import") (part "741G08DBVAHC"))
    )
    (comp (ref "IC4")
      (value "V7805-2000")
      (footprint "eagle-import:TO220V")
      (libsource (lib "eagle-import") (part "78TV05"))
    )
    (comp (ref "IMU")
      (value "9-DOF-BREAKOUT")
      (footprint "eagle-import:9-DOF-BREAKOUT")
      (fields (field (name "PARTNO") "BCS-110-L-S-TE"))
      (libsource (lib "eagle-import") (part "9-DOF-BREAKOUT"))
    )
    (comp (ref "L2")
      (value "22u")
      (footprint "eagle-import:NR60XX")
      (fields (field (name "PARTNO") "NR6045T220M"))
      (libsource (lib "eagle-import") (part "NR6045"))
    )
    (comp (ref "POWER_INPUT")
      (value "3-1437664-0")
      (footprint "eagle-import:CONN-2")
      (fields (field (name "PARTNO") "NC6-P108-02"))
      (libsource (lib "eagle-import") (part "3-1437664-0"))
    )
    (comp (ref "PWR")
      (value "GRN")
      (footprint "eagle-import:CHIPLED_0805")
      (fields (field (name "PARTNO") "LG R971-KN-1"))
      (libsource (lib "eagle-import") (part "LEDCHIPLED_0805"))
    )
    (comp (ref "R24")
      (value "1K")
      (footprint "eagle-import:R0603")
      (fields (field (name "PARTNO") "RMCF0603FT1K00"))
      (libsource (lib "eagle-import") (part "R-EU_R0603"))
    )
    (comp (ref "R26")
      (value "11K5")
      (footprint "eagle-import:R0603")
      (fields (field (name "PARTNO") "RC0603FR-0711K5L"))
      (libsource (lib "eagle-import") (part "R-EU_R0603"))
    )
    (comp (ref "R27")
      (value "10K2")
      (footprint "eagle-import:R0603")
      (fields (field (name "PARTNO") "RC0603FR-0710K2L"))
      (libsource (lib "eagle-import") (part "R-EU_R0603"))
    )
    (comp (ref "R28")
      (value "1K24")
      (footprint "eagle-import:R0603")
      (fields (field (name "PARTNO") "RC0603FR-071K24L"))
      (libsource (lib "eagle-import") (part "R-EU_R0603"))
    )
    (comp (ref "R38")
      (value "1K")
      (footprint "eagle-import:R0603")
      (fields (field (name "PARTNO") "RMCF0603FT1K00"))
      (libsource (lib "eagle-import") (part "R-EU_R0603"))
    )
    (comp (ref "R39")
      (value "1K")
      (footprint "eagle-import:R0603")
      (fields (field (name "PARTNO") "RMCF0603FT1K00"))
      (libsource (lib "eagle-import") (part "R-EU_R0603"))
    )
    (comp (ref "R49")
      (value "110K")
      (footprint "eagle-import:R0603")
      (fields (field (name "PARTNO") "RC0603JR-07110KL"))
      (libsource (lib "eagle-import") (part "R-EU_R0603"))
    )
    (comp (ref "R50")
      (value "15K")
      (footprint "eagle-import:R0603")
      (fields (field (name "PARTNO") "RC0603JR-0715KL"))
      (libsource (lib "eagle-import") (part "R-EU_R0603"))
    )
    (comp (ref "R55")
      (value "0R05")
      (footprint "eagle-import:R2512")
      (fields (field (name "PARTNO") "PE2512FKE070R05L"))
      (libsource (lib "eagle-import") (part "R-EU_R2512"))
    )
    (comp (ref "R56")
      (value "33K")
      (footprint "eagle-import:R0603")
      (fields (field (name "PARTNO") "ERJ-3EKF3302V"))
      (libsource (lib "eagle-import") (part "R-EU_R0603"))
    )
    (comp (ref "R97")
      (value "10K")
      (footprint "eagle-import:R0603")
      (fields (field (name "PARTNO") "RNCP0603FTD10K0"))
      (libsource (lib "eagle-import") (part "R-EU_R0603"))
    )
    (comp (ref "R98")
      (value "10K")
      (footprint "eagle-import:R0603")
      (fields (field (name "PARTNO") "RNCP0603FTD10K0"))
      (libsource (lib "eagle-import") (part "R-EU_R0603"))
    )
    (comp (ref "R99")
      (value "10K")
      (footprint "eagle-import:R0603")
      (fields (field (name "PARTNO") "RNCP0603FTD10K0"))
      (libsource (lib "eagle-import") (part "R-EU_R0603"))
    )
    (comp (ref "R100")
      (value "1K")
      (footprint "eagle-import:R0603")
      (fields (field (name "PARTNO") "RMCF0603FT1K00"))
      (libsource (lib "eagle-import") (part "R-EU_R0603"))
    )
    (comp (ref "REV")
      (value "RED")
      (footprint "eagle-import:CHIPLED_0805")
      (fields (field (name "PARTNO") "LH R974-LP-1"))
      (libsource (lib "eagle-import") (part "LEDCHIPLED_0805"))
    )
    (comp (ref "T1")
      (value "AO4407A")
      (footprint "eagle-import:SO08")
      (libsource (lib "eagle-import") (part "MOSFET-PCHANNEL-SOIC8SOIC8"))
    )
    (comp (ref "U15")
      (value "TPS54331")
      (footprint "eagle-import:SO08")
      (fields (field (name "PARTNO") "TPS54331DR"))
      (libsource (lib "eagle-import") (part "TPS54331"))
    )
    (comp (ref "U27")
      (value "INA169")
      (footprint "eagle-import:SOT23-5L")
      (fields (field (name "PARTNO") "INA169NA/3K"))
      (libsource (lib "eagle-import") (part "INA169"))
    )
    (comp (ref "C7")
      (value "100n")
      (footprint "eagle-import:C0603")
      (fields (field (name "PARTNO") "CC0603KRX7R9BB104"))
      (libsource (lib "eagle-import") (part "C-EUC0603"))
    )
    (comp (ref "C8")
      (value "100n")
      (footprint "eagle-import:C0603")
      (fields (field (name "PARTNO") "CC0603KRX7R9BB104"))
      (libsource (lib "eagle-import") (part "C-EUC0603"))
    )
    (comp (ref "C9")
      (value "100n")
      (footprint "eagle-import:C0603")
      (fields (field (name "PARTNO") "CC0603KRX7R9BB104"))
      (libsource (lib "eagle-import") (part "C-EUC0603"))
    )
    (comp (ref "C10")
      (value "100n")
      (footprint "eagle-import:C0603")
      (fields (field (name "PARTNO") "CC0603KRX7R9BB104"))
      (libsource (lib "eagle-import") (part "C-EUC0603"))
    )
    (comp (ref "C41")
      (value "22n")
      (footprint "eagle-import:0805X4-CAP")
      (fields (field (name "PARTNO") "CKCL44X5R1C223M085AA"))
      (libsource (lib "eagle-import") (part "4CAP0805"))
    )
    (comp (ref "C42")
      (value "22n")
      (footprint "eagle-import:0805X4-CAP")
      (fields (field (name "PARTNO") "CKCL44X5R1C223M085AA"))
      (libsource (lib "eagle-import") (part "4CAP0805"))
    )
    (comp (ref "C48")
      (value "100n")
      (footprint "eagle-import:C0603")
      (fields (field (name "PARTNO") "CC0603KRX7R9BB104"))
      (libsource (lib "eagle-import") (part "C-EUC0603"))
    )
    (comp (ref "C49")
      (value "22n")
      (footprint "eagle-import:0805X4-CAP")
      (fields (field (name "PARTNO") "CKCL44X5R1C223M085AA"))
      (libsource (lib "eagle-import") (part "4CAP0805"))
    )
    (comp (ref "C50")
      (value "22n")
      (footprint "eagle-import:0805X4-CAP")
      (fields (field (name "PARTNO") "CKCL44X5R1C223M085AA"))
      (libsource (lib "eagle-import") (part "4CAP0805"))
    )
    (comp (ref "J11")
      (value "M03LOCK")
      (footprint "eagle-import:1X03_LOCK")
      (fields (field (name "PARTNO") "?"))
      (libsource (lib "eagle-import") (part "M03LOCK"))
    )
    (comp (ref "R51")
      (value "4K7")
      (footprint "eagle-import:R0603")
      (fields (field (name "PARTNO") "RC1608J472CS"))
      (libsource (lib "eagle-import") (part "R-EU_R0603"))
    )
    (comp (ref "R52")
      (value "4K7")
      (footprint "eagle-import:R0603")
      (fields (field (name "PARTNO") "RC1608J472CS"))
      (libsource (lib "eagle-import") (part "R-EU_R0603"))
    )
    (comp (ref "R53")
      (value "4K7")
      (footprint "eagle-import:R0603")
      (fields (field (name "PARTNO") "RC1608J472CS"))
      (libsource (lib "eagle-import") (part "R-EU_R0603"))
    )
    (comp (ref "R54")
      (value "4K7")
      (footprint "eagle-import:R0603")
      (fields (field (name "PARTNO") "RC1608J472CS"))
      (libsource (lib "eagle-import") (part "R-EU_R0603"))
    )
    (comp (ref "R110")
      (value "10K")
      (footprint "eagle-import:CTS742C083-RES")
      (fields (field (name "PARTNO") "742C083103JPTR"))
      (libsource (lib "eagle-import") (part "4R-NCTS742C083"))
    )
    (comp (ref "R111")
      (value "10K")
      (footprint "eagle-import:CTS742C083-RES")
      (fields (field (name "PARTNO") "742C083103JPTR"))
      (libsource (lib "eagle-import") (part "4R-NCTS742C083"))
    )
    (comp (ref "R112")
      (value "10K")
      (footprint "eagle-import:CTS742C083-RES")
      (fields (field (name "PARTNO") "742C083103JPTR"))
      (libsource (lib "eagle-import") (part "4R-NCTS742C083"))
    )
    (comp (ref "R113")
      (value "10K")
      (footprint "eagle-import:CTS742C083-RES")
      (fields (field (name "PARTNO") "742C083103JPTR"))
      (libsource (lib "eagle-import") (part "4R-NCTS742C083"))
    )
    (comp (ref "RS485")
      (value "HEADER_POS3_70555")
      (footprint "eagle-import:70555-POS3")
      (fields (field (name "PARTNO") "0705550037"))
      (libsource (lib "eagle-import") (part "HEADER_POS3_?70555"))
    )
    (comp (ref "U18")
      (value "ADC128D818")
      (footprint "eagle-import:TSSOP16")
      (fields (field (name "PARTNO") "ADC128D818CIMTX"))
      (libsource (lib "eagle-import") (part "ADC128D818"))
    )
    (comp (ref "U19")
      (value "ADC128D818")
      (footprint "eagle-import:TSSOP16")
      (fields (field (name "PARTNO") "ADC128D818CIMTX"))
      (libsource (lib "eagle-import") (part "ADC128D818"))
    )
    (comp (ref "U26")
      (value "TXS0102")
      (footprint "eagle-import:VFSOP-8")
      (fields (field (name "PARTNO") "TXS0102DCURG4"))
      (libsource (lib "eagle-import") (part "TXS0102"))
    )
    (comp (ref "U28")
      (value "RS485SOIC")
      (footprint "eagle-import:SO08")
      (fields (field (name "PARTNO") "SN75176BDR"))
      (libsource (lib "eagle-import") (part "RS485SOIC"))
    )
    (comp (ref "C37")
      (value "100n")
      (footprint "eagle-import:C0603")
      (fields (field (name "PARTNO") "CC0603KRX7R9BB104"))
      (libsource (lib "eagle-import") (part "C-EUC0603"))
    )
    (comp (ref "C38")
      (value "100n")
      (footprint "eagle-import:C0603")
      (fields (field (name "PARTNO") "CC0603KRX7R9BB104"))
      (libsource (lib "eagle-import") (part "C-EUC0603"))
    )
    (comp (ref "C39")
      (value "100n")
      (footprint "eagle-import:C0603")
      (fields (field (name "PARTNO") "CC0603KRX7R9BB104"))
      (libsource (lib "eagle-import") (part "C-EUC0603"))
    )
    (comp (ref "D14")
      (value "DIODESOD-123")
      (footprint "eagle-import:SOD-123")
      (fields (field (name "PARTNO") "CDBW140-G"))
      (libsource (lib "eagle-import") (part "DIODESOD-123"))
    )
    (comp (ref "D15")
      (value "DIODESOD-123")
      (footprint "eagle-import:SOD-123")
      (fields (field (name "PARTNO") "CDBW140-G"))
      (libsource (lib "eagle-import") (part "DIODESOD-123"))
    )
    (comp (ref "D16")
      (value "DIODESOD-123")
      (footprint "eagle-import:SOD-123")
      (fields (field (name "PARTNO") "CDBW140-G"))
      (libsource (lib "eagle-import") (part "DIODESOD-123"))
    )
    (comp (ref "D17")
      (value "DIODESOD-123")
      (footprint "eagle-import:SOD-123")
      (fields (field (name "PARTNO") "CDBW140-G"))
      (libsource (lib "eagle-import") (part "DIODESOD-123"))
    )
    (comp (ref "D18")
      (value "DIODESOD-123")
      (footprint "eagle-import:SOD-123")
      (fields (field (name "PARTNO") "CDBW140-G"))
      (libsource (lib "eagle-import") (part "DIODESOD-123"))
    )
    (comp (ref "D19")
      (value "DIODESOD-123")
      (footprint "eagle-import:SOD-123")
      (fields (field (name "PARTNO") "CDBW140-G"))
      (libsource (lib "eagle-import") (part "DIODESOD-123"))
    )
    (comp (ref "HORN")
      (value "HEADER_POS2_70555")
      (footprint "eagle-import:70555-POS2")
      (fields (field (name "PARTNO") "0705550036"))
      (libsource (lib "eagle-import") (part "HEADER_POS2_?70555"))
    )
    (comp (ref "HORN-RLY")
      (value "RED")
      (footprint "eagle-import:CHIPLED_0805")
      (fields (field (name "PARTNO") "LH R974-LP-1"))
      (libsource (lib "eagle-import") (part "LEDCHIPLED_0805"))
    )
    (comp (ref "J9")
      (value "M02LOCK")
      (footprint "eagle-import:1X02_LOCK")
      (fields (field (name "PARTNO") "?"))
      (libsource (lib "eagle-import") (part "M02LOCK"))
    )
    (comp (ref "R69")
      (value "10K")
      (footprint "eagle-import:R0603")
      (fields (field (name "PARTNO") "RNCP0603FTD10K0"))
      (libsource (lib "eagle-import") (part "R-EU_R0603"))
    )
    (comp (ref "R70")
      (value "10K")
      (footprint "eagle-import:R0603")
      (fields (field (name "PARTNO") "RNCP0603FTD10K0"))
      (libsource (lib "eagle-import") (part "R-EU_R0603"))
    )
    (comp (ref "R71")
      (value "10K")
      (footprint "eagle-import:R0603")
      (fields (field (name "PARTNO") "RNCP0603FTD10K0"))
      (libsource (lib "eagle-import") (part "R-EU_R0603"))
    )
    (comp (ref "R72")
      (value "100K")
      (footprint "eagle-import:R0603")
      (fields (field (name "PARTNO") "CRCW0603100KFKEA"))
      (libsource (lib "eagle-import") (part "R-EU_R0603"))
    )
    (comp (ref "R73")
      (value "0R05")
      (footprint "eagle-import:R2512")
      (fields (field (name "PARTNO") "PE2512FKE070R05L"))
      (libsource (lib "eagle-import") (part "R-EU_R2512"))
    )
    (comp (ref "R74")
      (value "33K")
      (footprint "eagle-import:R0603")
      (fields (field (name "PARTNO") "ERJ-3EKF3302V"))
      (libsource (lib "eagle-import") (part "R-EU_R0603"))
    )
    (comp (ref "R75")
      (value "10K")
      (footprint "eagle-import:R0603")
      (fields (field (name "PARTNO") "RNCP0603FTD10K0"))
      (libsource (lib "eagle-import") (part "R-EU_R0603"))
    )
    (comp (ref "R76")
      (value "10K")
      (footprint "eagle-import:R0603")
      (fields (field (name "PARTNO") "RNCP0603FTD10K0"))
      (libsource (lib "eagle-import") (part "R-EU_R0603"))
    )
    (comp (ref "R77")
      (value "10K")
      (footprint "eagle-import:R0603")
      (fields (field (name "PARTNO") "RNCP0603FTD10K0"))
      (libsource (lib "eagle-import") (part "R-EU_R0603"))
    )
    (comp (ref "R78")
      (value "100K")
      (footprint "eagle-import:R0603")
      (fields (field (name "PARTNO") "CRCW0603100KFKEA"))
      (libsource (lib "eagle-import") (part "R-EU_R0603"))
    )
    (comp (ref "R79")
      (value "0R05")
      (footprint "eagle-import:R2512")
      (fields (field (name "PARTNO") "PE2512FKE070R05L"))
      (libsource (lib "eagle-import") (part "R-EU_R2512"))
    )
    (comp (ref "R80")
      (value "33K")
      (footprint "eagle-import:R0603")
      (fields (field (name "PARTNO") "ERJ-3EKF3302V"))
      (libsource (lib "eagle-import") (part "R-EU_R0603"))
    )
    (comp (ref "R81")
      (value "10K")
      (footprint "eagle-import:R0603")
      (fields (field (name "PARTNO") "RNCP0603FTD10K0"))
      (libsource (lib "eagle-import") (part "R-EU_R0603"))
    )
    (comp (ref "R82")
      (value "10K")
      (footprint "eagle-import:R0603")
      (fields (field (name "PARTNO") "RNCP0603FTD10K0"))
      (libsource (lib "eagle-import") (part "R-EU_R0603"))
    )
    (comp (ref "R83")
      (value "10K")
      (footprint "eagle-import:R0603")
      (fields (field (name "PARTNO") "RNCP0603FTD10K0"))
      (libsource (lib "eagle-import") (part "R-EU_R0603"))
    )
    (comp (ref "R84")
      (value "100K")
      (footprint "eagle-import:R0603")
      (fields (field (name "PARTNO") "CRCW0603100KFKEA"))
      (libsource (lib "eagle-import") (part "R-EU_R0603"))
    )
    (comp (ref "R85")
      (value "0R05")
      (footprint "eagle-import:R2512")
      (fields (field (name "PARTNO") "PE2512FKE070R05L"))
      (libsource (lib "eagle-import") (part "R-EU_R2512"))
    )
    (comp (ref "R86")
      (value "33K")
      (footprint "eagle-import:R0603")
      (fields (field (name "PARTNO") "ERJ-3EKF3302V"))
      (libsource (lib "eagle-import") (part "R-EU_R0603"))
    )
    (comp (ref "R88")
      (value "1K")
      (footprint "eagle-import:R0603")
      (fields (field (name "PARTNO") "RMCF0603FT1K00"))
      (libsource (lib "eagle-import") (part "R-EU_R0603"))
    )
    (comp (ref "U20")
      (value "IPS6041G")
      (footprint "eagle-import:SO08")
      (fields (field (name "PARTNO") "IPS6041GPBF"))
      (libsource (lib "eagle-import") (part "IPS6041G"))
    )
    (comp (ref "U21")
      (value "INA169")
      (footprint "eagle-import:SOT23-5L")
      (fields (field (name "PARTNO") "INA169NA/3K"))
      (libsource (lib "eagle-import") (part "INA169"))
    )
    (comp (ref "U22")
      (value "IPS6041G")
      (footprint "eagle-import:SO08")
      (fields (field (name "PARTNO") "IPS6041GPBF"))
      (libsource (lib "eagle-import") (part "IPS6041G"))
    )
    (comp (ref "U23")
      (value "INA169")
      (footprint "eagle-import:SOT23-5L")
      (fields (field (name "PARTNO") "INA169NA/3K"))
      (libsource (lib "eagle-import") (part "INA169"))
    )
    (comp (ref "U24")
      (value "IPS6041G")
      (footprint "eagle-import:SO08")
      (fields (field (name "PARTNO") "IPS6041GPBF"))
      (libsource (lib "eagle-import") (part "IPS6041G"))
    )
    (comp (ref "U25")
      (value "INA169")
      (footprint "eagle-import:SOT23-5L")
      (fields (field (name "PARTNO") "INA169NA/3K"))
      (libsource (lib "eagle-import") (part "INA169"))
    )
    (comp (ref "BBB_CONSOLE")
      (value "FTDI_BASICPTH")
      (footprint "eagle-import:FTDI_BASIC")
      (fields (field (name "PARTNO") "215299-6"))
      (libsource (lib "eagle-import") (part "FTDI_BASICPTH"))
    )
    (comp (ref "R48")
      (value "10K")
      (footprint "eagle-import:R0603")
      (fields (field (name "PARTNO") "RNCP0603FTD10K0"))
      (libsource (lib "eagle-import") (part "R-EU_R0603"))
    )
    (comp (ref "U$1")
      (value "BEAGLEBONE_OUTLINE")
      (footprint "eagle-import:BEAGLEBONE_SHIELD")
      (fields (field (name "PARTNO") "?"))
      (libsource (lib "eagle-import") (part "BEAGLEBONE_OUTLINE"))
    )
    (comp (ref "U$2")
      (value "M24LOCK")
      (footprint "eagle-import:1X24_LOCK")
      (libsource (lib "eagle-import") (part "M24LOCK"))
    )
    (comp (ref "U$3")
      (value "M24LOCK")
      (footprint "eagle-import:1X24_LOCK")
      (libsource (lib "eagle-import") (part "M24LOCK"))
    )
    (comp (ref "U$4")
      (value "M24LOCK")
      (footprint "eagle-import:1X24_LOCK")
      (libsource (lib "eagle-import") (part "M24LOCK"))
    )
    (comp (ref "U$5")
      (value "M24LOCK")
      (footprint "eagle-import:1X24_LOCK")
      (libsource (lib "eagle-import") (part "M24LOCK"))
    )
    (comp (ref "ACC_POWER")
      (value "PINHD-2X8_2.54")
      (footprint "eagle-import:2X08")
      (libsource (lib "eagle-import") (part "PINHD-2X8_2.54"))
    )
    (comp (ref "BBB_RESET")
      (value "HEADER_POS3_70555")
      (footprint "eagle-import:70555-POS3")
      (fields (field (name "PARTNO") "0705550037"))
      (libsource (lib "eagle-import") (part "HEADER_POS3_?70555"))
    )
    (comp (ref "C47")
      (value "100n")
      (footprint "eagle-import:C0603")
      (fields (field (name "PARTNO") "CC0603KRX7R9BB104"))
      (libsource (lib "eagle-import") (part "C-EUC0603"))
    )
    (comp (ref "D24")
      (value "5V")
      (footprint "eagle-import:SOD-123")
      (fields (field (name "PARTNO") "SMF5.0A"))
      (libsource (lib "eagle-import") (part "DIODESOD-123"))
    )
    (comp (ref "D25")
      (value "5V")
      (footprint "eagle-import:SOD-123")
      (fields (field (name "PARTNO") "SMF5.0A"))
      (libsource (lib "eagle-import") (part "DIODESOD-123"))
    )
    (comp (ref "D26")
      (value "5V")
      (footprint "eagle-import:SOD-123")
      (fields (field (name "PARTNO") "SMF5.0A"))
      (libsource (lib "eagle-import") (part "DIODESOD-123"))
    )
    (comp (ref "D28")
      (value "5V")
      (footprint "eagle-import:SOD-123")
      (fields (field (name "PARTNO") "SMF5.0A"))
      (libsource (lib "eagle-import") (part "DIODESOD-123"))
    )
    (comp (ref "FAULT_0")
      (value "RED")
      (footprint "eagle-import:CHIPLED_0805")
      (fields (field (name "PARTNO") "LH R974-LP-1"))
      (libsource (lib "eagle-import") (part "LEDCHIPLED_0805"))
    )
    (comp (ref "FAULT_1")
      (value "RED")
      (footprint "eagle-import:CHIPLED_0805")
      (fields (field (name "PARTNO") "LH R974-LP-1"))
      (libsource (lib "eagle-import") (part "LEDCHIPLED_0805"))
    )
    (comp (ref "FAULT_2")
      (value "RED")
      (footprint "eagle-import:CHIPLED_0805")
      (fields (field (name "PARTNO") "LH R974-LP-1"))
      (libsource (lib "eagle-import") (part "LEDCHIPLED_0805"))
    )
    (comp (ref "FAULT_3")
      (value "RED")
      (footprint "eagle-import:CHIPLED_0805")
      (fields (field (name "PARTNO") "LH R974-LP-1"))
      (libsource (lib "eagle-import") (part "LEDCHIPLED_0805"))
    )
    (comp (ref "FAULT_4")
      (value "RED")
      (footprint "eagle-import:CHIPLED_0805")
      (fields (field (name "PARTNO") "LH R974-LP-1"))
      (libsource (lib "eagle-import") (part "LEDCHIPLED_0805"))
    )
    (comp (ref "FAULT_5")
      (value "RED")
      (footprint "eagle-import:CHIPLED_0805")
      (fields (field (name "PARTNO") "LH R974-LP-1"))
      (libsource (lib "eagle-import") (part "LEDCHIPLED_0805"))
    )
    (comp (ref "FAULT_DISARM")
      (value "RED")
      (footprint "eagle-import:CHIPLED_0805")
      (fields (field (name "PARTNO") "LH R974-LP-1"))
      (libsource (lib "eagle-import") (part "LEDCHIPLED_0805"))
    )
    (comp (ref "FAULT_ENABLE")
      (value "RED")
      (footprint "eagle-import:CHIPLED_0805")
      (fields (field (name "PARTNO") "LH R974-LP-1"))
      (libsource (lib "eagle-import") (part "LEDCHIPLED_0805"))
    )
    (comp (ref "FAULT_HORN")
      (value "RED")
      (footprint "eagle-import:CHIPLED_0805")
      (fields (field (name "PARTNO") "LH R974-LP-1"))
      (libsource (lib "eagle-import") (part "LEDCHIPLED_0805"))
    )
    (comp (ref "IC3")
      (value "74AHC1G04DBV")
      (footprint "eagle-import:SOT23-5")
      (fields (field (name "PARTNO") "MC74HC1G04DTT1G"))
      (libsource (lib "eagle-import") (part "741G04DBVAHC"))
    )
    (comp (ref "J1")
      (value "M03LOCK")
      (footprint "eagle-import:1X03_LOCK")
      (fields (field (name "PARTNO") "?"))
      (libsource (lib "eagle-import") (part "M03LOCK"))
    )
    (comp (ref "J3")
      (value "M04LOCK")
      (footprint "eagle-import:1X04_LOCK")
      (libsource (lib "eagle-import") (part "M04LOCK"))
    )
    (comp (ref "J10")
      (value "M03LOCK")
      (footprint "eagle-import:1X03_LOCK")
      (fields (field (name "PARTNO") "?"))
      (libsource (lib "eagle-import") (part "M03LOCK"))
    )
    (comp (ref "POE-DEVICE")
      (value "RJ45")
      (footprint "eagle-import:RJ45-8")
      (fields (field (name "PARTNO") "615008137121"))
      (libsource (lib "eagle-import") (part "RJ45-8PTH"))
    )
    (comp (ref "POE-LAN")
      (value "RJ45")
      (footprint "eagle-import:RJ45-8")
      (fields (field (name "PARTNO") "615008137121"))
      (libsource (lib "eagle-import") (part "RJ45-8PTH"))
    )
    (comp (ref "POWER_MON")
      (value "PINHD-2X6_2.54")
      (footprint "eagle-import:2X06")
      (libsource (lib "eagle-import") (part "PINHD-2X6_2.54"))
    )
    (comp (ref "R92")
      (value "1K")
      (footprint "eagle-import:R0603")
      (fields (field (name "PARTNO") "RMCF0603FT1K00"))
      (libsource (lib "eagle-import") (part "R-EU_R0603"))
    )
    (comp (ref "R93")
      (value "1K")
      (footprint "eagle-import:R0603")
      (fields (field (name "PARTNO") "RMCF0603FT1K00"))
      (libsource (lib "eagle-import") (part "R-EU_R0603"))
    )
    (comp (ref "R94")
      (value "1K")
      (footprint "eagle-import:R0603")
      (fields (field (name "PARTNO") "RMCF0603FT1K00"))
      (libsource (lib "eagle-import") (part "R-EU_R0603"))
    )
    (comp (ref "R96")
      (value "1K")
      (footprint "eagle-import:R0603")
      (fields (field (name "PARTNO") "RMCF0603FT1K00"))
      (libsource (lib "eagle-import") (part "R-EU_R0603"))
    )
    (comp (ref "R101")
      (value "1K")
      (footprint "eagle-import:R0603")
      (fields (field (name "PARTNO") "RMCF0603FT1K00"))
      (libsource (lib "eagle-import") (part "R-EU_R0603"))
    )
    (comp (ref "R102")
      (value "1K")
      (footprint "eagle-import:R0603")
      (fields (field (name "PARTNO") "RMCF0603FT1K00"))
      (libsource (lib "eagle-import") (part "R-EU_R0603"))
    )
    (comp (ref "R103")
      (value "1K")
      (footprint "eagle-import:R0603")
      (fields (field (name "PARTNO") "RMCF0603FT1K00"))
      (libsource (lib "eagle-import") (part "R-EU_R0603"))
    )
    (comp (ref "R104")
      (value "1K")
      (footprint "eagle-import:R0603")
      (fields (field (name "PARTNO") "RMCF0603FT1K00"))
      (libsource (lib "eagle-import") (part "R-EU_R0603"))
    )
    (comp (ref "R105")
      (value "1K")
      (footprint "eagle-import:R0603")
      (fields (field (name "PARTNO") "RMCF0603FT1K00"))
      (libsource (lib "eagle-import") (part "R-EU_R0603"))
    )
    (comp (ref "R106")
      (value "1K")
      (footprint "eagle-import:R0603")
      (fields (field (name "PARTNO") "RMCF0603FT1K00"))
      (libsource (lib "eagle-import") (part "R-EU_R0603"))
    )
    (comp (ref "R107")
      (value "1K")
      (footprint "eagle-import:R0603")
      (fields (field (name "PARTNO") "RMCF0603FT1K00"))
      (libsource (lib "eagle-import") (part "R-EU_R0603"))
    )
    (comp (ref "R108")
      (value "1K")
      (footprint "eagle-import:R0603")
      (fields (field (name "PARTNO") "RMCF0603FT1K00"))
      (libsource (lib "eagle-import") (part "R-EU_R0603"))
    )
    (comp (ref "R109")
      (value "1K")
      (footprint "eagle-import:R0603")
      (fields (field (name "PARTNO") "RMCF0603FT1K00"))
      (libsource (lib "eagle-import") (part "R-EU_R0603"))
    )
    (comp (ref "SERIAL_CONSOLE")
      (value "HEADER_POS4_70555")
      (footprint "eagle-import:70555-POS4")
      (fields (field (name "PARTNO") "0705550038"))
      (libsource (lib "eagle-import") (part "HEADER_POS4_?70555"))
    )
    (comp (ref "STEERING")
      (value "HEADER_POS3_70555")
      (footprint "eagle-import:70555-POS3")
      (fields (field (name "PARTNO") "0705550037"))
      (libsource (lib "eagle-import") (part "HEADER_POS3_?70555"))
    )
    (comp (ref "C13")
      (value "100n")
      (footprint "eagle-import:C0603")
      (fields (field (name "PARTNO") "CC0603KRX7R9BB104"))
      (libsource (lib "eagle-import") (part "C-EUC0603"))
    )
    (comp (ref "C14")
      (value "100n")
      (footprint "eagle-import:C0603")
      (fields (field (name "PARTNO") "CC0603KRX7R9BB104"))
      (libsource (lib "eagle-import") (part "C-EUC0603"))
    )
    (comp (ref "C15")
      (value "100n")
      (footprint "eagle-import:C0603")
      (fields (field (name "PARTNO") "CC0603KRX7R9BB104"))
      (libsource (lib "eagle-import") (part "C-EUC0603"))
    )
    (comp (ref "C16")
      (value "100n")
      (footprint "eagle-import:C0603")
      (fields (field (name "PARTNO") "CC0603KRX7R9BB104"))
      (libsource (lib "eagle-import") (part "C-EUC0603"))
    )
    (comp (ref "C35")
      (value "100n")
      (footprint "eagle-import:C0603")
      (fields (field (name "PARTNO") "CC0603KRX7R9BB104"))
      (libsource (lib "eagle-import") (part "C-EUC0603"))
    )
    (comp (ref "C36")
      (value "100n")
      (footprint "eagle-import:C0603")
      (fields (field (name "PARTNO") "CC0603KRX7R9BB104"))
      (libsource (lib "eagle-import") (part "C-EUC0603"))
    )
    (comp (ref "D1")
      (value "DIODESOD-123")
      (footprint "eagle-import:SOD-123")
      (fields (field (name "PARTNO") "CDBW140-G"))
      (libsource (lib "eagle-import") (part "DIODESOD-123"))
    )
    (comp (ref "D2")
      (value "DIODESOD-123")
      (footprint "eagle-import:SOD-123")
      (fields (field (name "PARTNO") "CDBW140-G"))
      (libsource (lib "eagle-import") (part "DIODESOD-123"))
    )
    (comp (ref "D3")
      (value "DIODESOD-123")
      (footprint "eagle-import:SOD-123")
      (fields (field (name "PARTNO") "CDBW140-G"))
      (libsource (lib "eagle-import") (part "DIODESOD-123"))
    )
    (comp (ref "D4")
      (value "DIODESOD-123")
      (footprint "eagle-import:SOD-123")
      (fields (field (name "PARTNO") "CDBW140-G"))
      (libsource (lib "eagle-import") (part "DIODESOD-123"))
    )
    (comp (ref "D5")
      (value "DIODESOD-123")
      (footprint "eagle-import:SOD-123")
      (fields (field (name "PARTNO") "CDBW140-G"))
      (libsource (lib "eagle-import") (part "DIODESOD-123"))
    )
    (comp (ref "D6")
      (value "DIODESOD-123")
      (footprint "eagle-import:SOD-123")
      (fields (field (name "PARTNO") "CDBW140-G"))
      (libsource (lib "eagle-import") (part "DIODESOD-123"))
    )
    (comp (ref "D7")
      (value "DIODESOD-123")
      (footprint "eagle-import:SOD-123")
      (fields (field (name "PARTNO") "CDBW140-G"))
      (libsource (lib "eagle-import") (part "DIODESOD-123"))
    )
    (comp (ref "D8")
      (value "DIODESOD-123")
      (footprint "eagle-import:SOD-123")
      (fields (field (name "PARTNO") "CDBW140-G"))
      (libsource (lib "eagle-import") (part "DIODESOD-123"))
    )
    (comp (ref "D9")
      (value "DIODESOD-123")
      (footprint "eagle-import:SOD-123")
      (fields (field (name "PARTNO") "CDBW140-G"))
      (libsource (lib "eagle-import") (part "DIODESOD-123"))
    )
    (comp (ref "D10")
      (value "DIODESOD-123")
      (footprint "eagle-import:SOD-123")
      (fields (field (name "PARTNO") "CDBW140-G"))
      (libsource (lib "eagle-import") (part "DIODESOD-123"))
    )
    (comp (ref "D11")
      (value "DIODESOD-123")
      (footprint "eagle-import:SOD-123")
      (fields (field (name "PARTNO") "CDBW140-G"))
      (libsource (lib "eagle-import") (part "DIODESOD-123"))
    )
    (comp (ref "D12")
      (value "DIODESOD-123")
      (footprint "eagle-import:SOD-123")
      (fields (field (name "PARTNO") "CDBW140-G"))
      (libsource (lib "eagle-import") (part "DIODESOD-123"))
    )
    (comp (ref "R1")
      (value "10K")
      (footprint "eagle-import:R0603")
      (fields (field (name "PARTNO") "RNCP0603FTD10K0"))
      (libsource (lib "eagle-import") (part "R-EU_R0603"))
    )
    (comp (ref "R2")
      (value "10K")
      (footprint "eagle-import:R0603")
      (fields (field (name "PARTNO") "RNCP0603FTD10K0"))
      (libsource (lib "eagle-import") (part "R-EU_R0603"))
    )
    (comp (ref "R3")
      (value "10K")
      (footprint "eagle-import:R0603")
      (fields (field (name "PARTNO") "RNCP0603FTD10K0"))
      (libsource (lib "eagle-import") (part "R-EU_R0603"))
    )
    (comp (ref "R4")
      (value "100K")
      (footprint "eagle-import:R0603")
      (fields (field (name "PARTNO") "CRCW0603100KFKEA"))
      (libsource (lib "eagle-import") (part "R-EU_R0603"))
    )
    (comp (ref "R5")
      (value "0R05")
      (footprint "eagle-import:R2512")
      (fields (field (name "PARTNO") "PE2512FKE070R05L"))
      (libsource (lib "eagle-import") (part "R-EU_R2512"))
    )
    (comp (ref "R6")
      (value "33K")
      (footprint "eagle-import:R0603")
      (fields (field (name "PARTNO") "ERJ-3EKF3302V"))
      (libsource (lib "eagle-import") (part "R-EU_R0603"))
    )
    (comp (ref "R7")
      (value "10K")
      (footprint "eagle-import:R0603")
      (fields (field (name "PARTNO") "RNCP0603FTD10K0"))
      (libsource (lib "eagle-import") (part "R-EU_R0603"))
    )
    (comp (ref "R8")
      (value "10K")
      (footprint "eagle-import:R0603")
      (fields (field (name "PARTNO") "RNCP0603FTD10K0"))
      (libsource (lib "eagle-import") (part "R-EU_R0603"))
    )
    (comp (ref "R9")
      (value "10K")
      (footprint "eagle-import:R0603")
      (fields (field (name "PARTNO") "RNCP0603FTD10K0"))
      (libsource (lib "eagle-import") (part "R-EU_R0603"))
    )
    (comp (ref "R10")
      (value "100K")
      (footprint "eagle-import:R0603")
      (fields (field (name "PARTNO") "CRCW0603100KFKEA"))
      (libsource (lib "eagle-import") (part "R-EU_R0603"))
    )
    (comp (ref "R11")
      (value "0R05")
      (footprint "eagle-import:R2512")
      (fields (field (name "PARTNO") "PE2512FKE070R05L"))
      (libsource (lib "eagle-import") (part "R-EU_R2512"))
    )
    (comp (ref "R12")
      (value "33K")
      (footprint "eagle-import:R0603")
      (fields (field (name "PARTNO") "ERJ-3EKF3302V"))
      (libsource (lib "eagle-import") (part "R-EU_R0603"))
    )
    (comp (ref "R13")
      (value "10K")
      (footprint "eagle-import:R0603")
      (fields (field (name "PARTNO") "RNCP0603FTD10K0"))
      (libsource (lib "eagle-import") (part "R-EU_R0603"))
    )
    (comp (ref "R14")
      (value "10K")
      (footprint "eagle-import:R0603")
      (fields (field (name "PARTNO") "RNCP0603FTD10K0"))
      (libsource (lib "eagle-import") (part "R-EU_R0603"))
    )
    (comp (ref "R15")
      (value "10K")
      (footprint "eagle-import:R0603")
      (fields (field (name "PARTNO") "RNCP0603FTD10K0"))
      (libsource (lib "eagle-import") (part "R-EU_R0603"))
    )
    (comp (ref "R16")
      (value "100K")
      (footprint "eagle-import:R0603")
      (fields (field (name "PARTNO") "CRCW0603100KFKEA"))
      (libsource (lib "eagle-import") (part "R-EU_R0603"))
    )
    (comp (ref "R17")
      (value "0R05")
      (footprint "eagle-import:R2512")
      (fields (field (name "PARTNO") "PE2512FKE070R05L"))
      (libsource (lib "eagle-import") (part "R-EU_R2512"))
    )
    (comp (ref "R18")
      (value "33K")
      (footprint "eagle-import:R0603")
      (fields (field (name "PARTNO") "ERJ-3EKF3302V"))
      (libsource (lib "eagle-import") (part "R-EU_R0603"))
    )
    (comp (ref "R25")
      (value "10K")
      (footprint "eagle-import:R0603")
      (fields (field (name "PARTNO") "RNCP0603FTD10K0"))
      (libsource (lib "eagle-import") (part "R-EU_R0603"))
    )
    (comp (ref "R29")
      (value "10K")
      (footprint "eagle-import:R0603")
      (fields (field (name "PARTNO") "RNCP0603FTD10K0"))
      (libsource (lib "eagle-import") (part "R-EU_R0603"))
    )
    (comp (ref "R30")
      (value "10K")
      (footprint "eagle-import:R0603")
      (fields (field (name "PARTNO") "RNCP0603FTD10K0"))
      (libsource (lib "eagle-import") (part "R-EU_R0603"))
    )
    (comp (ref "R31")
      (value "100K")
      (footprint "eagle-import:R0603")
      (fields (field (name "PARTNO") "CRCW0603100KFKEA"))
      (libsource (lib "eagle-import") (part "R-EU_R0603"))
    )
    (comp (ref "R32")
      (value "0R05")
      (footprint "eagle-import:R2512")
      (fields (field (name "PARTNO") "PE2512FKE070R05L"))
      (libsource (lib "eagle-import") (part "R-EU_R2512"))
    )
    (comp (ref "R33")
      (value "33K")
      (footprint "eagle-import:R0603")
      (fields (field (name "PARTNO") "ERJ-3EKF3302V"))
      (libsource (lib "eagle-import") (part "R-EU_R0603"))
    )
    (comp (ref "R34")
      (value "10K")
      (footprint "eagle-import:R0603")
      (fields (field (name "PARTNO") "RNCP0603FTD10K0"))
      (libsource (lib "eagle-import") (part "R-EU_R0603"))
    )
    (comp (ref "R35")
      (value "10K")
      (footprint "eagle-import:R0603")
      (fields (field (name "PARTNO") "RNCP0603FTD10K0"))
      (libsource (lib "eagle-import") (part "R-EU_R0603"))
    )
    (comp (ref "R36")
      (value "10K")
      (footprint "eagle-import:R0603")
      (fields (field (name "PARTNO") "RNCP0603FTD10K0"))
      (libsource (lib "eagle-import") (part "R-EU_R0603"))
    )
    (comp (ref "R37")
      (value "100K")
      (footprint "eagle-import:R0603")
      (fields (field (name "PARTNO") "CRCW0603100KFKEA"))
      (libsource (lib "eagle-import") (part "R-EU_R0603"))
    )
    (comp (ref "R40")
      (value "0R05")
      (footprint "eagle-import:R2512")
      (fields (field (name "PARTNO") "PE2512FKE070R05L"))
      (libsource (lib "eagle-import") (part "R-EU_R2512"))
    )
    (comp (ref "R41")
      (value "33K")
      (footprint "eagle-import:R0603")
      (fields (field (name "PARTNO") "ERJ-3EKF3302V"))
      (libsource (lib "eagle-import") (part "R-EU_R0603"))
    )
    (comp (ref "R42")
      (value "10K")
      (footprint "eagle-import:R0603")
      (fields (field (name "PARTNO") "RNCP0603FTD10K0"))
      (libsource (lib "eagle-import") (part "R-EU_R0603"))
    )
    (comp (ref "R43")
      (value "10K")
      (footprint "eagle-import:R0603")
      (fields (field (name "PARTNO") "RNCP0603FTD10K0"))
      (libsource (lib "eagle-import") (part "R-EU_R0603"))
    )
    (comp (ref "R44")
      (value "10K")
      (footprint "eagle-import:R0603")
      (fields (field (name "PARTNO") "RNCP0603FTD10K0"))
      (libsource (lib "eagle-import") (part "R-EU_R0603"))
    )
    (comp (ref "R45")
      (value "100K")
      (footprint "eagle-import:R0603")
      (fields (field (name "PARTNO") "CRCW0603100KFKEA"))
      (libsource (lib "eagle-import") (part "R-EU_R0603"))
    )
    (comp (ref "R46")
      (value "0R05")
      (footprint "eagle-import:R2512")
      (fields (field (name "PARTNO") "PE2512FKE070R05L"))
      (libsource (lib "eagle-import") (part "R-EU_R2512"))
    )
    (comp (ref "R47")
      (value "33K")
      (footprint "eagle-import:R0603")
      (fields (field (name "PARTNO") "ERJ-3EKF3302V"))
      (libsource (lib "eagle-import") (part "R-EU_R0603"))
    )
    (comp (ref "U1")
      (value "IPS6041G")
      (footprint "eagle-import:SO08")
      (fields (field (name "PARTNO") "IPS6041GPBF"))
      (libsource (lib "eagle-import") (part "IPS6041G"))
    )
    (comp (ref "U2")
      (value "IPS6041G")
      (footprint "eagle-import:SO08")
      (fields (field (name "PARTNO") "IPS6041GPBF"))
      (libsource (lib "eagle-import") (part "IPS6041G"))
    )
    (comp (ref "U3")
      (value "INA169")
      (footprint "eagle-import:SOT23-5L")
      (fields (field (name "PARTNO") "INA169NA/3K"))
      (libsource (lib "eagle-import") (part "INA169"))
    )
    (comp (ref "U4")
      (value "IPS6041G")
      (footprint "eagle-import:SO08")
      (fields (field (name "PARTNO") "IPS6041GPBF"))
      (libsource (lib "eagle-import") (part "IPS6041G"))
    )
    (comp (ref "U5")
      (value "INA169")
      (footprint "eagle-import:SOT23-5L")
      (fields (field (name "PARTNO") "INA169NA/3K"))
      (libsource (lib "eagle-import") (part "INA169"))
    )
    (comp (ref "U6")
      (value "IPS6041G")
      (footprint "eagle-import:SO08")
      (fields (field (name "PARTNO") "IPS6041GPBF"))
      (libsource (lib "eagle-import") (part "IPS6041G"))
    )
    (comp (ref "U7")
      (value "INA169")
      (footprint "eagle-import:SOT23-5L")
      (fields (field (name "PARTNO") "INA169NA/3K"))
      (libsource (lib "eagle-import") (part "INA169"))
    )
    (comp (ref "U8")
      (value "IPS6041G")
      (footprint "eagle-import:SO08")
      (fields (field (name "PARTNO") "IPS6041GPBF"))
      (libsource (lib "eagle-import") (part "IPS6041G"))
    )
    (comp (ref "U9")
      (value "INA169")
      (footprint "eagle-import:SOT23-5L")
      (fields (field (name "PARTNO") "INA169NA/3K"))
      (libsource (lib "eagle-import") (part "INA169"))
    )
    (comp (ref "U10")
      (value "INA169")
      (footprint "eagle-import:SOT23-5L")
      (fields (field (name "PARTNO") "INA169NA/3K"))
      (libsource (lib "eagle-import") (part "INA169"))
    )
    (comp (ref "U11")
      (value "IPS6041G")
      (footprint "eagle-import:SO08")
      (fields (field (name "PARTNO") "IPS6041GPBF"))
      (libsource (lib "eagle-import") (part "IPS6041G"))
    )
    (comp (ref "U12")
      (value "INA169")
      (footprint "eagle-import:SOT23-5L")
      (fields (field (name "PARTNO") "INA169NA/3K"))
      (libsource (lib "eagle-import") (part "INA169"))
    )
    (comp (ref "C19")
      (value "10u")
      (footprint "eagle-import:C1210")
      (fields (field (name "PARTNO") "UMK325BJ106MM"))
      (libsource (lib "eagle-import") (part "C-EUC1210"))
    )
    (comp (ref "C20")
      (value "22u")
      (footprint "eagle-import:C1210")
      (fields (field (name "PARTNO") "GRM32ER61E226KE15K"))
      (libsource (lib "eagle-import") (part "C-EUC1210"))
    )
    (comp (ref "D27")
      (value "5V")
      (footprint "eagle-import:SOD-123")
      (fields (field (name "PARTNO") "SMF5.0A"))
      (libsource (lib "eagle-import") (part "DIODESOD-123"))
    )
    (comp (ref "F2")
      (value "PTC-2920")
      (footprint "eagle-import:2920L")
      (fields (field (name "PARTNO") "MF-LSMF300/24X-2"))
      (libsource (lib "eagle-import") (part "PTC-2920"))
    )
    (comp (ref "IC5")
      (value "V7805-2000")
      (footprint "eagle-import:TO220V")
      (libsource (lib "eagle-import") (part "78TV05"))
    )
    (comp (ref "J2")
      (value "M03LOCK")
      (footprint "eagle-import:1X03_LOCK")
      (fields (field (name "PARTNO") "?"))
      (libsource (lib "eagle-import") (part "M03LOCK"))
    )
    (comp (ref "J5")
      (value "M09LOCK")
      (footprint "eagle-import:1X09_LOCK")
      (libsource (lib "eagle-import") (part "M09LOCK"))
    )
    (comp (ref "J6")
      (value "M10LOCK")
      (footprint "eagle-import:1X10_LOCK")
      (libsource (lib "eagle-import") (part "M10LOCK"))
    )
    (comp (ref "J7")
      (value "M18_")
      (footprint "eagle-import:1X18")
      (libsource (lib "eagle-import") (part "M18_"))
    )
    (comp (ref "R19")
      (value "4K7'")
      (footprint "eagle-import:R0603")
      (fields (field (name "PARTNO") "RC1608J472CS"))
      (libsource (lib "eagle-import") (part "R-EU_R0603"))
    )
    (comp (ref "R20")
      (value "4K7")
      (footprint "eagle-import:R0603")
      (fields (field (name "PARTNO") "RC1608J472CS"))
      (libsource (lib "eagle-import") (part "R-EU_R0603"))
    )
    (comp (ref "R95")
      (value "1K")
      (footprint "eagle-import:R0603")
      (fields (field (name "PARTNO") "RMCF0603FT1K00"))
      (libsource (lib "eagle-import") (part "R-EU_R0603"))
    )
    (comp (ref "STATUS_LIGHTS")
      (value "HEADER_POS3_70555")
      (footprint "eagle-import:70555-POS3")
      (fields (field (name "PARTNO") "0705550037"))
      (libsource (lib "eagle-import") (part "HEADER_POS3_?70555"))
    )
    (comp (ref "C1")
      (value "100n")
      (footprint "eagle-import:C0603")
      (fields (field (name "PARTNO") "CC0603KRX7R9BB104"))
      (libsource (lib "eagle-import") (part "C-EUC0603"))
    )
    (comp (ref "C2")
      (value "100n")
      (footprint "eagle-import:C0603")
      (fields (field (name "PARTNO") "CC0603KRX7R9BB104"))
      (libsource (lib "eagle-import") (part "C-EUC0603"))
    )
    (comp (ref "C3")
      (value "100n")
      (footprint "eagle-import:C0603")
      (fields (field (name "PARTNO") "CC0603KRX7R9BB104"))
      (libsource (lib "eagle-import") (part "C-EUC0603"))
    )
    (comp (ref "C4")
      (value "100n")
      (footprint "eagle-import:C0603")
      (fields (field (name "PARTNO") "CC0603KRX7R9BB104"))
      (libsource (lib "eagle-import") (part "C-EUC0603"))
    )
    (comp (ref "C5")
      (value "100n")
      (footprint "eagle-import:C0603")
      (fields (field (name "PARTNO") "CC0603KRX7R9BB104"))
      (libsource (lib "eagle-import") (part "C-EUC0603"))
    )
    (comp (ref "C6")
      (value "100n")
      (footprint "eagle-import:C0603")
      (fields (field (name "PARTNO") "CC0603KRX7R9BB104"))
      (libsource (lib "eagle-import") (part "C-EUC0603"))
    )
    (comp (ref "U13")
      (value "TXB0108PWR")
      (footprint "eagle-import:TSSOP20")
      (libsource (lib "eagle-import") (part "TXB0108PWR"))
    )
    (comp (ref "U16")
      (value "TXB0108PWR")
      (footprint "eagle-import:TSSOP20")
      (libsource (lib "eagle-import") (part "TXB0108PWR"))
    )
    (comp (ref "U17")
      (value "TXB0108PWR")
      (footprint "eagle-import:TSSOP20")
      (libsource (lib "eagle-import") (part "TXB0108PWR"))
    )
    (comp (ref "15V-ENB")
      (value "SJ")
      (footprint "eagle-import:SJ")
      (fields (field (name "PARTNO") "?"))
      (libsource (lib "eagle-import") (part "SJ"))
    )
    (comp (ref "AUX_GPIO")
      (value "2X6 FEMALE")
      (footprint "eagle-import:2X6")
      (libsource (lib "eagle-import") (part "M06X2PTH_FEMALE"))
    )
    (comp (ref "C40")
      (value "100n")
      (footprint "eagle-import:C0603")
      (fields (field (name "PARTNO") "CC0603KRX7R9BB104"))
      (libsource (lib "eagle-import") (part "C-EUC0603"))
    )
    (comp (ref "C43")
      (value "4u7")
      (footprint "eagle-import:C1210")
      (fields (field (name "PARTNO") "UMK325F475ZH"))
      (libsource (lib "eagle-import") (part "C-EUC1210"))
    )
    (comp (ref "C44")
      (value "4u7")
      (footprint "eagle-import:C1210")
      (fields (field (name "PARTNO") "UMK325F475ZH"))
      (libsource (lib "eagle-import") (part "C-EUC1210"))
    )
    (comp (ref "C45")
      (value "47n")
      (footprint "eagle-import:C0603")
      (fields (field (name "PARTNO") "C1608X7R1H473M"))
      (libsource (lib "eagle-import") (part "C-EUC0603"))
    )
    (comp (ref "C46")
      (value "68n")
      (footprint "eagle-import:C0603")
      (fields (field (name "PARTNO") "CL10C680JB8NNNC"))
      (libsource (lib "eagle-import") (part "C-EUC0603"))
    )
    (comp (ref "D20")
      (value "SPARKFUN_DIODESMA")
      (footprint "eagle-import:SPARKFUN_SMA-DIODE")
      (fields (field (name "PARTNO") "SK310A-LTP"))
      (libsource (lib "eagle-import") (part "SPARKFUN_DIODESMA"))
    )
    (comp (ref "D21")
      (value "5V")
      (footprint "eagle-import:SOD-123")
      (fields (field (name "PARTNO") "SMF5.0A"))
      (libsource (lib "eagle-import") (part "DIODESOD-123"))
    )
    (comp (ref "D22")
      (value "5V")
      (footprint "eagle-import:SOD-123")
      (fields (field (name "PARTNO") "SMF5.0A"))
      (libsource (lib "eagle-import") (part "DIODESOD-123"))
    )
    (comp (ref "D23")
      (value "5V")
      (footprint "eagle-import:SOD-123")
      (fields (field (name "PARTNO") "SMF5.0A"))
      (libsource (lib "eagle-import") (part "DIODESOD-123"))
    )
    (comp (ref "DISARM")
      (value "AMB")
      (footprint "eagle-import:CHIPLED_0805")
      (fields (field (name "PARTNO") "HSMA-C170"))
      (libsource (lib "eagle-import") (part "LEDCHIPLED_0805"))
    )
    (comp (ref "ENABLE")
      (value "GRN")
      (footprint "eagle-import:CHIPLED_0805")
      (fields (field (name "PARTNO") "LG R971-KN-1"))
      (libsource (lib "eagle-import") (part "LEDCHIPLED_0805"))
    )
    (comp (ref "ENABLE/DISARM")
      (value "M05LOCK")
      (footprint "eagle-import:1X05_LOCK")
      (libsource (lib "eagle-import") (part "M05LOCK"))
    )
    (comp (ref "IC2")
      (value "74AUC1G06DBV")
      (footprint "eagle-import:SOT23-5")
      (fields (field (name "PARTNO") "SN74LVC1G06DBVR"))
      (libsource (lib "eagle-import") (part "741G06DBVAUC"))
    )
    (comp (ref "L3")
      (value "22u")
      (footprint "eagle-import:SRN8040")
      (fields (field (name "PARTNO") "SRN8040-220M"))
      (libsource (lib "eagle-import") (part "SRN8040"))
    )
    (comp (ref "MOTOR-CTRL-RELAYS")
      (value "DB9FEMALE")
      (footprint "eagle-import:DB9")
      (fields (field (name "PARTNO") "1734354-1"))
      (libsource (lib "eagle-import") (part "DB9FEMALE"))
    )
    (comp (ref "POWER_STATE")
      (value "HEADER_POS5_70555")
      (footprint "eagle-import:70555-POS5")
      (fields (field (name "PARTNO") "0705550039"))
      (libsource (lib "eagle-import") (part "HEADER_POS5_?70555"))
    )
    (comp (ref "R57")
      (value "10K")
      (footprint "eagle-import:R0603")
      (fields (field (name "PARTNO") "RNCP0603FTD10K0"))
      (libsource (lib "eagle-import") (part "R-EU_R0603"))
    )
    (comp (ref "R58")
      (value "174K")
      (footprint "eagle-import:R0603")
      (fields (field (name "PARTNO") "RC0603FR-07174KL"))
      (libsource (lib "eagle-import") (part "R-EU_R0603"))
    )
    (comp (ref "R59")
      (value "1K62")
      (footprint "eagle-import:R0603")
      (fields (field (name "PARTNO") "RC0603FR-071K62L"))
      (libsource (lib "eagle-import") (part "R-EU_R0603"))
    )
    (comp (ref "R60")
      (value "182K")
      (footprint "eagle-import:R0603")
      (fields (field (name "PARTNO") "ERJ-3EKF1823V"))
      (libsource (lib "eagle-import") (part "R-EU_R0603"))
    )
    (comp (ref "R61")
      (value "16K2")
      (footprint "eagle-import:R0603")
      (fields (field (name "PARTNO") "RC0603FR-0716K2L"))
      (libsource (lib "eagle-import") (part "R-EU_R0603"))
    )
    (comp (ref "R62")
      (value "1K")
      (footprint "eagle-import:R0603")
      (fields (field (name "PARTNO") "RMCF0603FT1K00"))
      (libsource (lib "eagle-import") (part "R-EU_R0603"))
    )
    (comp (ref "R63")
      (value "1K")
      (footprint "eagle-import:R0603")
      (fields (field (name "PARTNO") "RMCF0603FT1K00"))
      (libsource (lib "eagle-import") (part "R-EU_R0603"))
    )
    (comp (ref "R64")
      (value "1K")
      (footprint "eagle-import:R0603")
      (fields (field (name "PARTNO") "RMCF0603FT1K00"))
      (libsource (lib "eagle-import") (part "R-EU_R0603"))
    )
    (comp (ref "R65")
      (value "1K")
      (footprint "eagle-import:R0603")
      (fields (field (name "PARTNO") "RMCF0603FT1K00"))
      (libsource (lib "eagle-import") (part "R-EU_R0603"))
    )
    (comp (ref "R66")
      (value "1K")
      (footprint "eagle-import:R0603")
      (fields (field (name "PARTNO") "RMCF0603FT1K00"))
      (libsource (lib "eagle-import") (part "R-EU_R0603"))
    )
    (comp (ref "R67")
      (value "1K")
      (footprint "eagle-import:R0603")
      (fields (field (name "PARTNO") "RMCF0603FT1K00"))
      (libsource (lib "eagle-import") (part "R-EU_R0603"))
    )
    (comp (ref "R68")
      (value "1K")
      (footprint "eagle-import:R0603")
      (fields (field (name "PARTNO") "RMCF0603FT1K00"))
      (libsource (lib "eagle-import") (part "R-EU_R0603"))
    )
    (comp (ref "R87")
      (value "1K")
      (footprint "eagle-import:R0603")
      (fields (field (name "PARTNO") "RMCF0603FT1K00"))
      (libsource (lib "eagle-import") (part "R-EU_R0603"))
    )
    (comp (ref "R89")
      (value "1K")
      (footprint "eagle-import:R0603")
      (fields (field (name "PARTNO") "RMCF0603FT1K00"))
      (libsource (lib "eagle-import") (part "R-EU_R0603"))
    )
    (comp (ref "R90")
      (value "1K")
      (footprint "eagle-import:R0603")
      (fields (field (name "PARTNO") "RMCF0603FT1K00"))
      (libsource (lib "eagle-import") (part "R-EU_R0603"))
    )
    (comp (ref "R91")
      (value "1K")
      (footprint "eagle-import:R0603")
      (fields (field (name "PARTNO") "RMCF0603FT1K00"))
      (libsource (lib "eagle-import") (part "R-EU_R0603"))
    )
    (comp (ref "RLY0")
      (value "GRN")
      (footprint "eagle-import:CHIPLED_0805")
      (fields (field (name "PARTNO") "LG R971-KN-1"))
      (libsource (lib "eagle-import") (part "LEDCHIPLED_0805"))
    )
    (comp (ref "RLY1")
      (value "GRN")
      (footprint "eagle-import:CHIPLED_0805")
      (fields (field (name "PARTNO") "LG R971-KN-1"))
      (libsource (lib "eagle-import") (part "LEDCHIPLED_0805"))
    )
    (comp (ref "RLY2")
      (value "GRN")
      (footprint "eagle-import:CHIPLED_0805")
      (fields (field (name "PARTNO") "LG R971-KN-1"))
      (libsource (lib "eagle-import") (part "LEDCHIPLED_0805"))
    )
    (comp (ref "RLY3")
      (value "GRN")
      (footprint "eagle-import:CHIPLED_0805")
      (fields (field (name "PARTNO") "LG R971-KN-1"))
      (libsource (lib "eagle-import") (part "LEDCHIPLED_0805"))
    )
    (comp (ref "RLY4")
      (value "GRN")
      (footprint "eagle-import:CHIPLED_0805")
      (fields (field (name "PARTNO") "LG R971-KN-1"))
      (libsource (lib "eagle-import") (part "LEDCHIPLED_0805"))
    )
    (comp (ref "RLY5")
      (value "GRN")
      (footprint "eagle-import:CHIPLED_0805")
      (fields (field (name "PARTNO") "LG R971-KN-1"))
      (libsource (lib "eagle-import") (part "LEDCHIPLED_0805"))
    )
    (comp (ref "SBUS-IN")
      (value "HEADER_POS3_70545")
      (footprint "eagle-import:70545-POS3")
      (fields (field (name "PARTNO") "0705450037"))
      (libsource (lib "eagle-import") (part "HEADER_POS3_?70545"))
    )
    (comp (ref "SBUS-OUT")
      (value "HEADER_POS3_70545")
      (footprint "eagle-import:70545-POS3")
      (fields (field (name "PARTNO") "0705450037"))
      (libsource (lib "eagle-import") (part "HEADER_POS3_?70545"))
    )
    (comp (ref "SJ1")
      (value "SJ2W")
      (footprint "eagle-import:SJ_2")
      (fields (field (name "PARTNO") "?"))
      (libsource (lib "eagle-import") (part "SJ2W"))
    )
    (comp (ref "SJ2") (value "SJ") (footprint "eagle-import:SJ") (libsource (lib "eagle-import") (part "SJ")))
    (comp (ref "U29")
      (value "TPS61175")
      (footprint "eagle-import:HTSSOP14")
      (fields (field (name "PARTNO") "TPS61175PWPR"))
      (libsource (lib "eagle-import") (part "TPS61175"))
    )
  )
  (nets
    (net (code "1") (name "+3V3") (class "Default")
      (node (ref "ACC_POWER") (pin "10") (pinfunction "10_10") (pintype "passive"))
      (node (ref "ACC_POWER") (pin "7") (pinfunction "7_7") (pintype "passive"))
      (node (ref "ACC_POWER") (pin "8") (pinfunction "8_8") (pintype "passive"))
      (node (ref "ACC_POWER") (pin "9") (pinfunction "9_9") (pintype "passive"))
      (node (ref "C1") (pin "1") (pinfunction "1_1") (pintype "passive"))
      (node (ref "C3") (pin "1") (pinfunction "1_1") (pintype "passive"))
      (node (ref "C5") (pin "1") (pinfunction "1_1") (pintype "passive"))
      (node (ref "C8") (pin "2") (pinfunction "2_2") (pintype "passive"))
      (node (ref "CELL") (pin "VIO") (pinfunction "15_VIO") (pintype "passive"))
      (node (ref "J7") (pin "15") (pinfunction "15_15") (pintype "passive"))
      (node (ref "R14") (pin "2") (pinfunction "2_2") (pintype "passive"))
      (node (ref "R19") (pin "2") (pinfunction "2_2") (pintype "passive"))
      (node (ref "R2") (pin "2") (pinfunction "2_2") (pintype "passive"))
      (node (ref "R20") (pin "2") (pinfunction "2_2") (pintype "passive"))
      (node (ref "R29") (pin "2") (pinfunction "2_2") (pintype "passive"))
      (node (ref "R35") (pin "2") (pinfunction "2_2") (pintype "passive"))
      (node (ref "R43") (pin "2") (pinfunction "2_2") (pintype "passive"))
      (node (ref "R48") (pin "1") (pinfunction "1_1") (pintype "passive"))
      (node (ref "R53") (pin "2") (pinfunction "2_2") (pintype "passive"))
      (node (ref "R54") (pin "2") (pinfunction "2_2") (pintype "passive"))
      (node (ref "R57") (pin "2") (pinfunction "2_2") (pintype "passive"))
      (node (ref "R70") (pin "2") (pinfunction "2_2") (pintype "passive"))
      (node (ref "R76") (pin "2") (pinfunction "2_2") (pintype "passive"))
      (node (ref "R8") (pin "2") (pinfunction "2_2") (pintype "passive"))
      (node (ref "R82") (pin "2") (pinfunction "2_2") (pintype "passive"))
      (node (ref "U$1") (pin "49") (pinfunction "VDD_3V3EXP_49") (pintype "power_in"))
      (node (ref "U$1") (pin "50") (pinfunction "VDD_3V3EXP_50") (pintype "power_in"))
      (node (ref "U$2") (pin "24") (pinfunction "24_24") (pintype "passive"))
      (node (ref "U$5") (pin "24") (pinfunction "24_24") (pintype "passive"))
      (node (ref "U13") (pin "10") (pinfunction "OE_10") (pintype "bidirectional"))
      (node (ref "U13") (pin "2") (pinfunction "VCCA_2") (pintype "bidirectional"))
      (node (ref "U16") (pin "10") (pinfunction "OE_10") (pintype "bidirectional"))
      (node (ref "U16") (pin "2") (pinfunction "VCCA_2") (pintype "bidirectional"))
      (node (ref "U17") (pin "10") (pinfunction "OE_10") (pintype "bidirectional"))
      (node (ref "U17") (pin "2") (pinfunction "VCCA_2") (pintype "bidirectional"))
      (node (ref "U26") (pin "P$3") (pinfunction "VCCA_P$3") (pintype "bidirectional"))
      (node (ref "U26") (pin "P$6") (pinfunction "OE_P$6") (pintype "bidirectional"))
    )
    (net (code "2") (name "+5V") (class "Default")
      (node (ref "ACC_POWER") (pin "1") (pinfunction "1_1") (pintype "passive"))
      (node (ref "ACC_POWER") (pin "2") (pinfunction "2_2") (pintype "passive"))
      (node (ref "ACC_POWER") (pin "3") (pinfunction "3_3") (pintype "passive"))
      (node (ref "ACC_POWER") (pin "4") (pinfunction "4_4") (pintype "passive"))
      (node (ref "AUX_GPIO") (pin "1") (pinfunction "1_1") (pintype "passive"))
      (node (ref "AUX_GPIO") (pin "2") (pinfunction "2_2") (pintype "passive"))
      (node (ref "BBB_RESET") (pin "P$1") (pinfunction "1_P$1") (pintype "passive"))
      (node (ref "C10") (pin "1") (pinfunction "1_1") (pintype "passive"))
      (node (ref "C11") (pin "1") (pinfunction "1_1") (pintype "passive"))
      (node (ref "C12") (pin "1") (pinfunction "1_1") (pintype "passive"))
      (node (ref "C13") (pin "2") (pinfunction "2_2") (pintype "passive"))
      (node (ref "C14") (pin "2") (pinfunction "2_2") (pintype "passive"))
      (node (ref "C15") (pin "2") (pinfunction "2_2") (pintype "passive"))
      (node (ref "C16") (pin "2") (pinfunction "2_2") (pintype "passive"))
      (node (ref "C18") (pin "1") (pinfunction "1_1") (pintype "passive"))
      (node (ref "C2") (pin "1") (pinfunction "1_1") (pintype "passive"))
      (node (ref "C35") (pin "2") (pinfunction "2_2") (pintype "passive"))
      (node (ref "C36") (pin "2") (pinfunction "2_2") (pintype "passive"))
      (node (ref "C37") (pin "2") (pinfunction "2_2") (pintype "passive"))
      (node (ref "C38") (pin "2") (pinfunction "2_2") (pintype "passive"))
      (node (ref "C39") (pin "2") (pinfunction "2_2") (pintype "passive"))
      (node (ref "C4") (pin "1") (pinfunction "1_1") (pintype "passive"))
      (node (ref "C40") (pin "1") (pinfunction "1_1") (pintype "passive"))
      (node (ref "C47") (pin "1") (pinfunction "1_1") (pintype "passive"))
      (node (ref "C48") (pin "1") (pinfunction "1_1") (pintype "passive"))
      (node (ref "C6") (pin "1") (pinfunction "1_1") (pintype "passive"))
      (node (ref "C7") (pin "1") (pinfunction "1_1") (pintype "passive"))
      (node (ref "C9") (pin "1") (pinfunction "1_1") (pintype "passive"))
      (node (ref "CELL") (pin "5V") (pinfunction "18_5V") (pintype "passive"))
      (node (ref "GPS") (pin "VIN") (pinfunction "5_VIN") (pintype "passive"))
      (node (ref "IC1") (pin "5") (pinfunction "VCC_5") (pintype "power_in"))
      (node (ref "IC2") (pin "5") (pinfunction "VCC_5") (pintype "power_in"))
      (node (ref "IC3") (pin "5") (pinfunction "VCC_5") (pintype "power_in"))
      (node (ref "IC4") (pin "3") (pinfunction "VO_3") (pintype "passive"))
      (node (ref "IMU") (pin "VIN") (pinfunction "1_VIN") (pintype "passive"))
      (node (ref "J10") (pin "1") (pinfunction "1_1") (pintype "passive"))
      (node (ref "J5") (pin "2") (pinfunction "2_2") (pintype "passive"))
      (node (ref "J6") (pin "1") (pinfunction "1_1") (pintype "passive"))
      (node (ref "J7") (pin "18") (pinfunction "18_18") (pintype "passive"))
      (node (ref "POWER_MON") (pin "1") (pinfunction "1_1") (pintype "passive"))
      (node (ref "POWER_MON") (pin "5") (pinfunction "5_5") (pintype "passive"))
      (node (ref "POWER_MON") (pin "9") (pinfunction "9_9") (pintype "passive"))
      (node (ref "R101") (pin "2") (pinfunction "2_2") (pintype "passive"))
      (node (ref "R102") (pin "2") (pinfunction "2_2") (pintype "passive"))
      (node (ref "R103") (pin "2") (pinfunction "2_2") (pintype "passive"))
      (node (ref "R104") (pin "2") (pinfunction "2_2") (pintype "passive"))
      (node (ref "R105") (pin "2") (pinfunction "2_2") (pintype "passive"))
      (node (ref "R106") (pin "2") (pinfunction "2_2") (pintype "passive"))
      (node (ref "R107") (pin "2") (pinfunction "2_2") (pintype "passive"))
      (node (ref "R108") (pin "2") (pinfunction "2_2") (pintype "passive"))
      (node (ref "R109") (pin "2") (pinfunction "2_2") (pintype "passive"))
      (node (ref "R38") (pin "2") (pinfunction "2_2") (pintype "passive"))
      (node (ref "R51") (pin "2") (pinfunction "2_2") (pintype "passive"))
      (node (ref "R52") (pin "2") (pinfunction "2_2") (pintype "passive"))
      (node (ref "SBUS-IN") (pin "P$2") (pinfunction "2_P$2") (pintype "passive"))
      (node (ref "SBUS-OUT") (pin "P$2") (pinfunction "2_P$2") (pintype "passive"))
      (node (ref "U$1") (pin "51") (pinfunction "VDD_5V_51") (pintype "power_in"))
      (node (ref "U$1") (pin "52") (pinfunction "VDD_5V_52") (pintype "power_in"))
      (node (ref "U$2") (pin "23") (pinfunction "23_23") (pintype "passive"))
      (node (ref "U$5") (pin "23") (pinfunction "23_23") (pintype "passive"))
      (node (ref "U10") (pin "5") (pinfunction "VCC_5") (pintype "bidirectional"))
      (node (ref "U12") (pin "5") (pinfunction "VCC_5") (pintype "bidirectional"))
      (node (ref "U13") (pin "19") (pinfunction "VCCB_19") (pintype "bidirectional"))
      (node (ref "U16") (pin "19") (pinfunction "VCCB_19") (pintype "bidirectional"))
      (node (ref "U17") (pin "19") (pinfunction "VCCB_19") (pintype "bidirectional"))
      (node (ref "U18") (pin "1") (pinfunction "VREF_1") (pintype "bidirectional"))
      (node (ref "U18") (pin "5") (pinfunction "VCC_5") (pintype "bidirectional"))
      (node (ref "U18") (pin "7") (pinfunction "A0_7") (pintype "bidirectional"))
      (node (ref "U19") (pin "1") (pinfunction "VREF_1") (pintype "bidirectional"))
      (node (ref "U19") (pin "5") (pinfunction "VCC_5") (pintype "bidirectional"))
      (node (ref "U21") (pin "5") (pinfunction "VCC_5") (pintype "bidirectional"))
      (node (ref "U23") (pin "5") (pinfunction "VCC_5") (pintype "bidirectional"))
      (node (ref "U25") (pin "5") (pinfunction "VCC_5") (pintype "bidirectional"))
      (node (ref "U26") (pin "P$7") (pinfunction "VCCB_P$7") (pintype "bidirectional"))
      (node (ref "U27") (pin "5") (pinfunction "VCC_5") (pintype "bidirectional"))
      (node (ref "U28") (pin "8") (pinfunction "VCC_8") (pintype "bidirectional"))
      (node (ref "U3") (pin "5") (pinfunction "VCC_5") (pintype "bidirectional"))
      (node (ref "U5") (pin "5") (pinfunction "VCC_5") (pintype "bidirectional"))
      (node (ref "U7") (pin "5") (pinfunction "VCC_5") (pintype "bidirectional"))
      (node (ref "U9") (pin "5") (pinfunction "VCC_5") (pintype "bidirectional"))
    )
    (net (code "3") (name "+7V4") (class "Default")
      (node (ref "ACC_POWER") (pin "15") (pinfunction "15_15") (pintype "passive"))
      (node (ref "ACC_POWER") (pin "16") (pinfunction "16_16") (pintype "passive"))
      (node (ref "J1") (pin "1") (pinfunction "1_1") (pintype "passive"))
      (node (ref "R39") (pin "2") (pinfunction "2_2") (pintype "passive"))
      (node (ref "R55") (pin "2") (pinfunction "2_2") (pintype "passive"))
      (node (ref "STEERING") (pin "P$1") (pinfunction "1_P$1") (pintype "passive"))
      (node (ref "U27") (pin "4") (pinfunction "VIN-_4") (pintype "bidirectional"))
    )
    (net (code "4") (name "+12V") (class "Default")
      (node (ref "15V-ENB") (pin "1") (pinfunction "1_1") (pintype "passive"))
      (node (ref "C17") (pin "1") (pinfunction "1_1") (pintype "passive"))
      (node (ref "C19") (pin "1") (pinfunction "1_1") (pintype "passive"))
      (node (ref "C28") (pin "1") (pinfunction "1_1") (pintype "passive"))
      (node (ref "C29") (pin "1") (pinfunction "1_1") (pintype "passive"))
      (node (ref "C30") (pin "1") (pinfunction "1_1") (pintype "passive"))
      (node (ref "C43") (pin "1") (pinfunction "1_1") (pintype "passive"))
      (node (ref "D1") (pin "C") (pinfunction "C_C") (pintype "passive"))
      (node (ref "D10") (pin "C") (pinfunction "C_C") (pintype "passive"))
      (node (ref "D11") (pin "C") (pinfunction "C_C") (pintype "passive"))
      (node (ref "D14") (pin "C") (pinfunction "C_C") (pintype "passive"))
      (node (ref "D16") (pin "C") (pinfunction "C_C") (pintype "passive"))
      (node (ref "D18") (pin "C") (pinfunction "C_C") (pintype "passive"))
      (node (ref "D3") (pin "C") (pinfunction "C_C") (pintype "passive"))
      (node (ref "D5") (pin "C") (pinfunction "C_C") (pintype "passive"))
      (node (ref "D8") (pin "C") (pinfunction "C_C") (pintype "passive"))
      (node (ref "IC4") (pin "1") (pinfunction "VI_1") (pintype "input"))
      (node (ref "IC5") (pin "1") (pinfunction "VI_1") (pintype "input"))
      (node (ref "R10") (pin "2") (pinfunction "2_2") (pintype "passive"))
      (node (ref "R16") (pin "2") (pinfunction "2_2") (pintype "passive"))
      (node (ref "R31") (pin "2") (pinfunction "2_2") (pintype "passive"))
      (node (ref "R37") (pin "2") (pinfunction "2_2") (pintype "passive"))
      (node (ref "R4") (pin "2") (pinfunction "2_2") (pintype "passive"))
      (node (ref "R45") (pin "2") (pinfunction "2_2") (pintype "passive"))
      (node (ref "R49") (pin "2") (pinfunction "2_2") (pintype "passive"))
      (node (ref "R72") (pin "2") (pinfunction "2_2") (pintype "passive"))
      (node (ref "R78") (pin "2") (pinfunction "2_2") (pintype "passive"))
      (node (ref "R84") (pin "2") (pinfunction "2_2") (pintype "passive"))
      (node (ref "T1") (pin "1") (pinfunction "S_1") (pintype "bidirectional"))
      (node (ref "T1") (pin "2") (pinfunction "S_2") (pintype "bidirectional"))
      (node (ref "T1") (pin "3") (pinfunction "S_3") (pintype "bidirectional"))
      (node (ref "U1") (pin "5") (pinfunction "VCC_5") (pintype "passive"))
      (node (ref "U1") (pin "6") (pinfunction "VCC_6") (pintype "passive"))
      (node (ref "U1") (pin "7") (pinfunction "VCC_7") (pintype "passive"))
      (node (ref "U1") (pin "8") (pinfunction "VCC_8") (pintype "passive"))
      (node (ref "U11") (pin "5") (pinfunction "VCC_5") (pintype "passive"))
      (node (ref "U11") (pin "6") (pinfunction "VCC_6") (pintype "passive"))
      (node (ref "U11") (pin "7") (pinfunction "VCC_7") (pintype "passive"))
      (node (ref "U11") (pin "8") (pinfunction "VCC_8") (pintype "passive"))
      (node (ref "U15") (pin "2") (pinfunction "VIN_2") (pintype "bidirectional"))
      (node (ref "U2") (pin "5") (pinfunction "VCC_5") (pintype "passive"))
      (node (ref "U2") (pin "6") (pinfunction "VCC_6") (pintype "passive"))
      (node (ref "U2") (pin "7") (pinfunction "VCC_7") (pintype "passive"))
      (node (ref "U2") (pin "8") (pinfunction "VCC_8") (pintype "passive"))
      (node (ref "U20") (pin "5") (pinfunction "VCC_5") (pintype "passive"))
      (node (ref "U20") (pin "6") (pinfunction "VCC_6") (pintype "passive"))
      (node (ref "U20") (pin "7") (pinfunction "VCC_7") (pintype "passive"))
      (node (ref "U20") (pin "8") (pinfunction "VCC_8") (pintype "passive"))
      (node (ref "U22") (pin "5") (pinfunction "VCC_5") (pintype "passive"))
      (node (ref "U22") (pin "6") (pinfunction "VCC_6") (pintype "passive"))
      (node (ref "U22") (pin "7") (pinfunction "VCC_7") (pintype "passive"))
      (node (ref "U22") (pin "8") (pinfunction "VCC_8") (pintype "passive"))
      (node (ref "U24") (pin "5") (pinfunction "VCC_5") (pintype "passive"))
      (node (ref "U24") (pin "6") (pinfunction "VCC_6") (pintype "passive"))
      (node (ref "U24") (pin "7") (pinfunction "VCC_7") (pintype "passive"))
      (node (ref "U24") (pin "8") (pinfunction "VCC_8") (pintype "passive"))
      (node (ref "U4") (pin "5") (pinfunction "VCC_5") (pintype "passive"))
      (node (ref "U4") (pin "6") (pinfunction "VCC_6") (pintype "passive"))
      (node (ref "U4") (pin "7") (pinfunction "VCC_7") (pintype "passive"))
      (node (ref "U4") (pin "8") (pinfunction "VCC_8") (pintype "passive"))
      (node (ref "U6") (pin "5") (pinfunction "VCC_5") (pintype "passive"))
      (node (ref "U6") (pin "6") (pinfunction "VCC_6") (pintype "passive"))
      (node (ref "U6") (pin "7") (pinfunction "VCC_7") (pintype "passive"))
      (node (ref "U6") (pin "8") (pinfunction "VCC_8") (pintype "passive"))
      (node (ref "U8") (pin "5") (pinfunction "VCC_5") (pintype "passive"))
      (node (ref "U8") (pin "6") (pinfunction "VCC_6") (pintype "passive"))
      (node (ref "U8") (pin "7") (pinfunction "VCC_7") (pintype "passive"))
      (node (ref "U8") (pin "8") (pinfunction "VCC_8") (pintype "passive"))
    )
    (net (code "5") (name "+15V") (class "Default")
      (node (ref "ACC_POWER") (pin "13") (pinfunction "13_13") (pintype "passive"))
      (node (ref "ACC_POWER") (pin "14") (pinfunction "14_14") (pintype "passive"))
      (node (ref "C44") (pin "1") (pinfunction "1_1") (pintype "passive"))
      (node (ref "D20") (pin "C") (pinfunction "C_C") (pintype "passive"))
      (node (ref "POE-DEVICE") (pin "4") (pinfunction "4_4") (pintype "bidirectional"))
      (node (ref "POE-DEVICE") (pin "5") (pinfunction "5_5") (pintype "bidirectional"))
      (node (ref "R60") (pin "2") (pinfunction "2_2") (pintype "passive"))
    )
    (net (code "6") (name "AUX_ADC_0") (class "Default")
      (node (ref "POWER_MON") (pin "10") (pinfunction "10_10") (pintype "passive"))
      (node (ref "R113") (pin "4") (pinfunction "2_4") (pintype "passive"))
    )
    (net (code "7") (name "AUX_ADC_1") (class "Default")
      (node (ref "POWER_MON") (pin "11") (pinfunction "11_11") (pintype "passive"))
      (node (ref "R113") (pin "6") (pinfunction "2_6") (pintype "passive"))
    )
    (net (code "8") (name "AUX_GPIO_0_3V3") (class "Default")
      (node (ref "U$1") (pin "21") (pinfunction "GPIO1_30_21") (pintype "passive"))
      (node (ref "U$4") (pin "14") (pinfunction "14_14") (pintype "passive"))
      (node (ref "U17") (pin "3") (pinfunction "A2_3") (pintype "bidirectional"))
    )
    (net (code "9") (name "AUX_GPIO_0_5V") (class "Default")
      (node (ref "AUX_GPIO") (pin "5") (pinfunction "5_5") (pintype "passive"))
      (node (ref "U17") (pin "18") (pinfunction "B2_18") (pintype "bidirectional"))
    )
    (net (code "10") (name "AUX_GPIO_1_3V3") (class "Default")
      (node (ref "U$1") (pin "23") (pinfunction "GPIO1_4_23") (pintype "passive"))
      (node (ref "U$4") (pin "13") (pinfunction "13_13") (pintype "passive"))
      (node (ref "U17") (pin "1") (pinfunction "A1_1") (pintype "bidirectional"))
    )
    (net (code "11") (name "AUX_GPIO_1_5V") (class "Default")
      (node (ref "AUX_GPIO") (pin "6") (pinfunction "6_6") (pintype "passive"))
      (node (ref "U17") (pin "20") (pinfunction "B1_20") (pintype "bidirectional"))
    )
    (net (code "12") (name "AUX_GPIO_2_3V3") (class "Default")
      (node (ref "U$1") (pin "25") (pinfunction "GPIO1_0_25") (pintype "passive"))
      (node (ref "U$4") (pin "12") (pinfunction "12_12") (pintype "passive"))
      (node (ref "U17") (pin "5") (pinfunction "A4_5") (pintype "bidirectional"))
    )
    (net (code "13") (name "AUX_GPIO_2_5V") (class "Default")
      (node (ref "AUX_GPIO") (pin "7") (pinfunction "7_7") (pintype "passive"))
      (node (ref "U17") (pin "16") (pinfunction "B4_16") (pintype "bidirectional"))
    )
    (net (code "14") (name "BATMON") (class "Default")
      (node (ref "D13") (pin "C") (pinfunction "C_C") (pintype "passive"))
      (node (ref "R49") (pin "1") (pinfunction "1_1") (pintype "passive"))
      (node (ref "R50") (pin "2") (pinfunction "2_2") (pintype "passive"))
      (node (ref "U$1") (pin "86") (pinfunction "AIN1_86") (pintype "passive"))
      (node (ref "U$2") (pin "6") (pinfunction "6_6") (pintype "passive"))
    )
    (net (code "15") (name "BBB_I2C_1_SCL") (class "Default")
      (node (ref "IMU") (pin "SCL") (pinfunction "4_SCL") (pintype "passive"))
      (node (ref "J6") (pin "4") (pinfunction "4_4") (pintype "passive"))
      (node (ref "R19") (pin "1") (pinfunction "1_1") (pintype "passive"))
      (node (ref "U$1") (pin "63") (pinfunction "I2C1_SCL_63") (pintype "passive"))
      (node (ref "U$5") (pin "17") (pinfunction "17_17") (pintype "passive"))
    )
    (net (code "16") (name "BBB_I2C_1_SDA") (class "Default")
      (node (ref "IMU") (pin "SDA") (pinfunction "5_SDA") (pintype "passive"))
      (node (ref "J6") (pin "5") (pinfunction "5_5") (pintype "passive"))
      (node (ref "R20") (pin "1") (pinfunction "1_1") (pintype "passive"))
      (node (ref "U$1") (pin "64") (pinfunction "I2C1_SDA_64") (pintype "passive"))
      (node (ref "U$2") (pin "17") (pinfunction "17_17") (pintype "passive"))
    )
    (net (code "17") (name "BBB_I2C_2_SCL") (class "Default")
      (node (ref "R53") (pin "1") (pinfunction "1_1") (pintype "passive"))
      (node (ref "U$1") (pin "65") (pinfunction "I2C2_SCL_65") (pintype "passive"))
      (node (ref "U$5") (pin "16") (pinfunction "16_16") (pintype "passive"))
      (node (ref "U26") (pin "P$4") (pinfunction "A2_P$4") (pintype "bidirectional"))
    )
    (net (code "18") (name "BBB_I2C_2_SDA") (class "Default")
      (node (ref "R54") (pin "1") (pinfunction "1_1") (pintype "passive"))
      (node (ref "U$1") (pin "66") (pinfunction "I2C2_SDA_66") (pintype "passive"))
      (node (ref "U$2") (pin "16") (pinfunction "16_16") (pintype "passive"))
      (node (ref "U26") (pin "P$5") (pinfunction "A1_P$5") (pintype "bidirectional"))
    )
    (net (code "19") (name "BBB_MISO") (class "Default")
      (node (ref "U$1") (pin "76") (pinfunction "SPI1_DI_76") (pintype "passive"))
      (node (ref "U$2") (pin "11") (pinfunction "11_11") (pintype "passive"))
      (node (ref "U17") (pin "6") (pinfunction "A5_6") (pintype "bidirectional"))
    )
    (net (code "20") (name "BBB_MISO_5V") (class "Default")
      (node (ref "AUX_GPIO") (pin "10") (pinfunction "10_10") (pintype "passive"))
      (node (ref "U17") (pin "15") (pinfunction "B5_15") (pintype "bidirectional"))
    )
    (net (code "21") (name "BBB_MOSI") (class "Default")
      (node (ref "U$1") (pin "75") (pinfunction "SPI1_DO_75") (pintype "passive"))
      (node (ref "U$5") (pin "11") (pinfunction "11_11") (pintype "passive"))
      (node (ref "U17") (pin "7") (pinfunction "A6_7") (pintype "bidirectional"))
    )
    (net (code "22") (name "BBB_MOSI_5V") (class "Default")
      (node (ref "AUX_GPIO") (pin "9") (pinfunction "9_9") (pintype "passive"))
      (node (ref "U17") (pin "14") (pinfunction "B6_14") (pintype "bidirectional"))
    )
    (net (code "23") (name "BBB_RESET_3V3") (class "Default")
      (node (ref "R48") (pin "2") (pinfunction "2_2") (pintype "passive"))
      (node (ref "U$1") (pin "56") (pinfunction "SYS_RESETN_56") (pintype "passive"))
      (node (ref "U$2") (pin "21") (pinfunction "21_21") (pintype "passive"))
      (node (ref "U16") (pin "8") (pinfunction "A7_8") (pintype "bidirectional"))
    )
    (net (code "24") (name "BBB_RESET_5V") (class "Default")
      (node (ref "IC3") (pin "4") (pinfunction "O_4") (pintype "output"))
      (node (ref "U16") (pin "13") (pinfunction "B7_13") (pintype "bidirectional"))
    )
    (net (code "25") (name "BBB_SCLK") (class "Default")
      (node (ref "U$1") (pin "77") (pinfunction "SPI1_SCLK_77") (pintype "passive"))
      (node (ref "U$5") (pin "10") (pinfunction "10_10") (pintype "passive"))
      (node (ref "U17") (pin "4") (pinfunction "A3_4") (pintype "bidirectional"))
    )
    (net (code "26") (name "BBB_SCLK_5V") (class "Default")
      (node (ref "AUX_GPIO") (pin "8") (pinfunction "8_8") (pintype "passive"))
      (node (ref "U17") (pin "17") (pinfunction "B3_17") (pintype "bidirectional"))
    )
    (net (code "27") (name "BBB_STATUS_LIGHTS_5V") (class "Default")
      (node (ref "D27") (pin "C") (pinfunction "C_C") (pintype "passive"))
      (node (ref "R95") (pin "2") (pinfunction "2_2") (pintype "passive"))
      (node (ref "U16") (pin "14") (pinfunction "B6_14") (pintype "bidirectional"))
    )
    (net (code "28") (name "BBB_STATUS_LIGHT_3V3") (class "Default")
      (node (ref "U16") (pin "7") (pinfunction "A6_7") (pintype "bidirectional"))
    )
    (net (code "29") (name "BBB_STAT_LIGHT_3V3") (class "Default")
      (node (ref "U$1") (pin "68") (pinfunction "UART2_RXD_68") (pintype "passive"))
      (node (ref "U$2") (pin "15") (pinfunction "15_15") (pintype "passive"))
    )
    (net (code "30") (name "BBB_UART0_RX") (class "Default")
      (node (ref "BBB_CONSOLE") (pin "RXI") (pinfunction "2_RXI") (pintype "passive"))
      (node (ref "D26") (pin "C") (pinfunction "C_C") (pintype "passive"))
      (node (ref "R93") (pin "2") (pinfunction "2_2") (pintype "passive"))
    )
    (net (code "31") (name "BBB_UART0_TX") (class "Default")
      (node (ref "BBB_CONSOLE") (pin "TXO") (pinfunction "3_TXO") (pintype "passive"))
      (node (ref "D25") (pin "C") (pinfunction "C_C") (pintype "passive"))
      (node (ref "R94") (pin "2") (pinfunction "2_2") (pintype "passive"))
    )
    (net (code "32") (name "BBB_UART1_RX_3V3") (class "Default")
      (node (ref "U$1") (pin "70") (pinfunction "UART1_TXD_70") (pintype "passive"))
      (node (ref "U$2") (pin "14") (pinfunction "14_14") (pintype "passive"))
      (node (ref "U17") (pin "8") (pinfunction "A7_8") (pintype "bidirectional"))
    )
    (net (code "33") (name "BBB_UART1_RX_5V") (class "Default")
      (node (ref "U17") (pin "13") (pinfunction "B7_13") (pintype "bidirectional"))
      (node (ref "U28") (pin "1") (pinfunction "RO_1") (pintype "bidirectional"))
    )
    (net (code "34") (name "BBB_UART1_TX_3V3") (class "Default")
      (node (ref "U$1") (pin "72") (pinfunction "UART1_RXD_72") (pintype "passive"))
      (node (ref "U$2") (pin "13") (pinfunction "13_13") (pintype "passive"))
      (node (ref "U17") (pin "9") (pinfunction "A8_9") (pintype "bidirectional"))
    )
    (net (code "35") (name "BBB_UART1_TX_5V") (class "Default")
      (node (ref "U17") (pin "12") (pinfunction "B8_12") (pintype "bidirectional"))
      (node (ref "U28") (pin "4") (pinfunction "DI_4") (pintype "bidirectional"))
    )
    (net (code "36") (name "CELL_CTS") (class "Default")
      (node (ref "CELL") (pin "CTS") (pinfunction "9_CTS") (pintype "passive"))
      (node (ref "J7") (pin "9") (pinfunction "9_9") (pintype "passive"))
      (node (ref "U$1") (pin "31") (pinfunction "UART5_CTSN_31") (pintype "passive"))
      (node (ref "U$4") (pin "9") (pinfunction "9_9") (pintype "passive"))
    )
    (net (code "37") (name "CELL_KEY") (class "Default")
      (node (ref "CELL") (pin "KEY") (pinfunction "8_KEY") (pintype "passive"))
      (node (ref "J7") (pin "8") (pinfunction "8_8") (pintype "passive"))
      (node (ref "U$1") (pin "40") (pinfunction "GPIO2_13_40") (pintype "passive"))
      (node (ref "U$3") (pin "5") (pinfunction "5_5") (pintype "passive"))
    )
    (net (code "38") (name "CELL_NET_STATUS") (class "Default")
      (node (ref "CELL") (pin "NS") (pinfunction "5_NS") (pintype "passive"))
      (node (ref "J7") (pin "5") (pinfunction "5_5") (pintype "passive"))
      (node (ref "U$1") (pin "34") (pinfunction "UART3_RTSN_34") (pintype "passive"))
      (node (ref "U$3") (pin "8") (pinfunction "8_8") (pintype "passive"))
    )
    (net (code "39") (name "CELL_POWER_STATUS") (class "Default")
      (node (ref "CELL") (pin "PS") (pinfunction "6_PS") (pintype "passive"))
      (node (ref "J7") (pin "6") (pinfunction "6_6") (pintype "passive"))
      (node (ref "U$1") (pin "28") (pinfunction "GPIO2_24_28") (pintype "passive"))
      (node (ref "U$3") (pin "11") (pinfunction "11_11") (pintype "passive"))
    )
    (net (code "40") (name "CELL_RESET") (class "Default")
      (node (ref "CELL") (pin "RST") (pinfunction "14_RST") (pintype "passive"))
      (node (ref "J7") (pin "14") (pinfunction "14_14") (pintype "passive"))
      (node (ref "U$1") (pin "36") (pinfunction "UART3_CTSN_36") (pintype "passive"))
      (node (ref "U$3") (pin "7") (pinfunction "7_7") (pintype "passive"))
    )
    (net (code "41") (name "CELL_RING") (class "Default")
      (node (ref "CELL") (pin "RI") (pinfunction "7_RI") (pintype "passive"))
      (node (ref "J7") (pin "7") (pinfunction "7_7") (pintype "passive"))
      (node (ref "U$1") (pin "30") (pinfunction "GPIO2_25_30") (pintype "passive"))
      (node (ref "U$3") (pin "10") (pinfunction "10_10") (pintype "passive"))
    )
    (net (code "42") (name "CELL_RTS") (class "Default")
      (node (ref "CELL") (pin "RTS") (pinfunction "11_RTS") (pintype "passive"))
      (node (ref "J7") (pin "11") (pinfunction "11_11") (pintype "passive"))
      (node (ref "U$1") (pin "32") (pinfunction "UART5_RTSN_32") (pintype "passive"))
      (node (ref "U$3") (pin "9") (pinfunction "9_9") (pintype "passive"))
    )
    (net (code "43") (name "CELL_RX") (class "Default")
      (node (ref "CELL") (pin "RX") (pinfunction "13_RX") (pintype "passive"))
      (node (ref "J7") (pin "13") (pinfunction "13_13") (pintype "passive"))
      (node (ref "U$1") (pin "37") (pinfunction "UART5_TXD_37") (pintype "passive"))
      (node (ref "U$4") (pin "6") (pinfunction "6_6") (pintype "passive"))
    )
    (net (code "44") (name "CELL_TX") (class "Default")
      (node (ref "CELL") (pin "TX") (pinfunction "12_TX") (pintype "passive"))
      (node (ref "J7") (pin "12") (pinfunction "12_12") (pintype "passive"))
      (node (ref "SJ1") (pin "3") (pinfunction "3_3") (pintype "passive"))
      (node (ref "U$1") (pin "38") (pinfunction "UART5_RXD_38") (pintype "passive"))
      (node (ref "U$3") (pin "6") (pinfunction "6_6") (pintype "passive"))
    )
    (net (code "45") (name "CHARGE_CURRENT") (class "Default")
      (node (ref "POWER_MON") (pin "7") (pinfunction "7_7") (pintype "passive"))
      (node (ref "R113") (pin "2") (pinfunction "2_2") (pintype "passive"))
    )
    (net (code "46") (name "CHARGE_VOLTAGE") (class "Default")
      (node (ref "POWER_MON") (pin "6") (pinfunction "6_6") (pintype "passive"))
      (node (ref "R112") (pin "8") (pinfunction "2_8") (pintype "passive"))
    )
    (net (code "47") (name "DISARM_RELAY_IN_3V3") (class "Default")
      (node (ref "U$1") (pin "22") (pinfunction "GPIO1_5_22") (pintype "passive"))
      (node (ref "U$3") (pin "14") (pinfunction "14_14") (pintype "passive"))
      (node (ref "U16") (pin "6") (pinfunction "A5_6") (pintype "bidirectional"))
    )
    (net (code "48") (name "DISARM_RELAY_IN_5V") (class "Default")
      (node (ref "D22") (pin "C") (pinfunction "C_C") (pintype "passive"))
      (node (ref "R90") (pin "2") (pinfunction "2_2") (pintype "passive"))
      (node (ref "U16") (pin "15") (pinfunction "B5_15") (pintype "bidirectional"))
    )
    (net (code "49") (name "ENABLE_RELAY_IN_3V3") (class "Default")
      (node (ref "U$1") (pin "20") (pinfunction "GPIO1_31_20") (pintype "passive"))
      (node (ref "U$3") (pin "15") (pinfunction "15_15") (pintype "passive"))
      (node (ref "U16") (pin "5") (pinfunction "A4_5") (pintype "bidirectional"))
    )
    (net (code "50") (name "ENABLE_RELAY_IN_5V") (class "Default")
      (node (ref "D23") (pin "C") (pinfunction "C_C") (pintype "passive"))
      (node (ref "IC1") (pin "2") (pinfunction "I1_2") (pintype "input"))
      (node (ref "R89") (pin "2") (pinfunction "2_2") (pintype "passive"))
      (node (ref "R98") (pin "1") (pinfunction "1_1") (pintype "passive"))
      (node (ref "U16") (pin "16") (pinfunction "B4_16") (pintype "bidirectional"))
    )
    (net (code "51") (name "GND") (class "Default")
      (node (ref "5V-STAT") (pin "C") (pinfunction "C_C") (pintype "passive"))
      (node (ref "7V4-STAT") (pin "C") (pinfunction "C_C") (pintype "passive"))
      (node (ref "ACC_POWER") (pin "11") (pinfunction "11_11") (pintype "passive"))
      (node (ref "ACC_POWER") (pin "12") (pinfunction "12_12") (pintype "passive"))
      (node (ref "ACC_POWER") (pin "5") (pinfunction "5_5") (pintype "passive"))
      (node (ref "ACC_POWER") (pin "6") (pinfunction "6_6") (pintype "passive"))
      (node (ref "AUX_GPIO") (pin "11") (pinfunction "11_11") (pintype "passive"))
      (node (ref "AUX_GPIO") (pin "12") (pinfunction "12_12") (pintype "passive"))
      (node (ref "BBB_CONSOLE") (pin "GND") (pinfunction "6_GND") (pintype "passive"))
      (node (ref "BBB_RESET") (pin "P$3") (pinfunction "3_P$3") (pintype "passive"))
      (node (ref "C1") (pin "2") (pinfunction "2_2") (pintype "passive"))
      (node (ref "C10") (pin "2") (pinfunction "2_2") (pintype "passive"))
      (node (ref "C11") (pin "2") (pinfunction "2_2") (pintype "passive"))
      (node (ref "C12") (pin "2") (pinfunction "2_2") (pintype "passive"))
      (node (ref "C13") (pin "1") (pinfunction "1_1") (pintype "passive"))
      (node (ref "C14") (pin "1") (pinfunction "1_1") (pintype "passive"))
      (node (ref "C15") (pin "1") (pinfunction "1_1") (pintype "passive"))
      (node (ref "C16") (pin "1") (pinfunction "1_1") (pintype "passive"))
      (node (ref "C17") (pin "2") (pinfunction "2_2") (pintype "passive"))
      (node (ref "C18") (pin "2") (pinfunction "2_2") (pintype "passive"))
      (node (ref "C19") (pin "2") (pinfunction "2_2") (pintype "passive"))
      (node (ref "C2") (pin "2") (pinfunction "2_2") (pintype "passive"))
      (node (ref "C20") (pin "2") (pinfunction "2_2") (pintype "passive"))
      (node (ref "C26") (pin "2") (pinfunction "2_2") (pintype "passive"))
      (node (ref "C27") (pin "2") (pinfunction "2_2") (pintype "passive"))
      (node (ref "C28") (pin "2") (pinfunction "2_2") (pintype "passive"))
      (node (ref "C29") (pin "2") (pinfunction "2_2") (pintype "passive"))
      (node (ref "C3") (pin "2") (pinfunction "2_2") (pintype "passive"))
      (node (ref "C30") (pin "2") (pinfunction "2_2") (pintype "passive"))
      (node (ref "C31") (pin "2") (pinfunction "2_2") (pintype "passive"))
      (node (ref "C33") (pin "2") (pinfunction "2_2") (pintype "passive"))
      (node (ref "C34") (pin "2") (pinfunction "2_2") (pintype "passive"))
      (node (ref "C35") (pin "1") (pinfunction "1_1") (pintype "passive"))
      (node (ref "C36") (pin "1") (pinfunction "1_1") (pintype "passive"))
      (node (ref "C37") (pin "1") (pinfunction "1_1") (pintype "passive"))
      (node (ref "C38") (pin "1") (pinfunction "1_1") (pintype "passive"))
      (node (ref "C39") (pin "1") (pinfunction "1_1") (pintype "passive"))
      (node (ref "C4") (pin "2") (pinfunction "2_2") (pintype "passive"))
      (node (ref "C40") (pin "2") (pinfunction "2_2") (pintype "passive"))
      (node (ref "C41") (pin "2") (pinfunction "2_2") (pintype "passive"))
      (node (ref "C41") (pin "4") (pinfunction "2_4") (pintype "passive"))
      (node (ref "C41") (pin "6") (pinfunction "2_6") (pintype "passive"))
      (node (ref "C41") (pin "8") (pinfunction "2_8") (pintype "passive"))
      (node (ref "C42") (pin "2") (pinfunction "2_2") (pintype "passive"))
      (node (ref "C42") (pin "4") (pinfunction "2_4") (pintype "passive"))
      (node (ref "C42") (pin "6") (pinfunction "2_6") (pintype "passive"))
      (node (ref "C42") (pin "8") (pinfunction "2_8") (pintype "passive"))
      (node (ref "C43") (pin "2") (pinfunction "2_2") (pintype "passive"))
      (node (ref "C44") (pin "2") (pinfunction "2_2") (pintype "passive"))
      (node (ref "C45") (pin "2") (pinfunction "2_2") (pintype "passive"))
      (node (ref "C46") (pin "2") (pinfunction "2_2") (pintype "passive"))
      (node (ref "C47") (pin "2") (pinfunction "2_2") (pintype "passive"))
      (node (ref "C48") (pin "2") (pinfunction "2_2") (pintype "passive"))
      (node (ref "C49") (pin "2") (pinfunction "2_2") (pintype "passive"))
      (node (ref "C49") (pin "4") (pinfunction "2_4") (pintype "passive"))
      (node (ref "C49") (pin "6") (pinfunction "2_6") (pintype "passive"))
      (node (ref "C49") (pin "8") (pinfunction "2_8") (pintype "passive"))
      (node (ref "C5") (pin "2") (pinfunction "2_2") (pintype "passive"))
      (node (ref "C50") (pin "2") (pinfunction "2_2") (pintype "passive"))
      (node (ref "C50") (pin "4") (pinfunction "2_4") (pintype "passive"))
      (node (ref "C50") (pin "6") (pinfunction "2_6") (pintype "passive"))
      (node (ref "C50") (pin "8") (pinfunction "2_8") (pintype "passive"))
      (node (ref "C6") (pin "2") (pinfunction "2_2") (pintype "passive"))
      (node (ref "C7") (pin "2") (pinfunction "2_2") (pintype "passive"))
      (node (ref "C8") (pin "1") (pinfunction "1_1") (pintype "passive"))
      (node (ref "C9") (pin "2") (pinfunction "2_2") (pintype "passive"))
      (node (ref "CELL") (pin "GND") (pinfunction "16_GND") (pintype "passive"))
      (node (ref "CELL") (pin "P$1") (pinfunction "9_P$1") (pintype "passive"))
      (node (ref "CELL") (pin "P$2") (pinfunction "9_P$2") (pintype "passive"))
      (node (ref "D12") (pin "A") (pinfunction "A_A") (pintype "passive"))
      (node (ref "D13") (pin "A") (pinfunction "A_A") (pintype "passive"))
      (node (ref "D15") (pin "A") (pinfunction "A_A") (pintype "passive"))
      (node (ref "D17") (pin "A") (pinfunction "A_A") (pintype "passive"))
      (node (ref "D19") (pin "A") (pinfunction "A_A") (pintype "passive"))
      (node (ref "D2") (pin "A") (pinfunction "A_A") (pintype "passive"))
      (node (ref "D21") (pin "A") (pinfunction "A_A") (pintype "passive"))
      (node (ref "D22") (pin "A") (pinfunction "A_A") (pintype "passive"))
      (node (ref "D23") (pin "A") (pinfunction "A_A") (pintype "passive"))
      (node (ref "D24") (pin "A") (pinfunction "A_A") (pintype "passive"))
      (node (ref "D25") (pin "A") (pinfunction "A_A") (pintype "passive"))
      (node (ref "D26") (pin "A") (pinfunction "A_A") (pintype "passive"))
      (node (ref "D27") (pin "A") (pinfunction "A_A") (pintype "passive"))
      (node (ref "D28") (pin "A") (pinfunction "A_A") (pintype "passive"))
      (node (ref "D36") (pin "A") (pinfunction "A_A") (pintype "passive"))
      (node (ref "D4") (pin "A") (pinfunction "A_A") (pintype "passive"))
      (node (ref "D6") (pin "A") (pinfunction "A_A") (pintype "passive"))
      (node (ref "D7") (pin "A") (pinfunction "A_A") (pintype "passive"))
      (node (ref "D9") (pin "A") (pinfunction "A_A") (pintype "passive"))
      (node (ref "DISARM") (pin "C") (pinfunction "C_C") (pintype "passive"))
      (node (ref "ENABLE") (pin "C") (pinfunction "C_C") (pintype "passive"))
      (node (ref "ENABLE/DISARM") (pin "3") (pinfunction "3_3") (pintype "passive"))
      (node (ref "GPS") (pin "GND") (pinfunction "6_GND") (pintype "passive"))
      (node (ref "GPS") (pin "MNT@0") (pinfunction "9_MNT@0") (pintype "passive"))
      (node (ref "GPS") (pin "MNT@1") (pinfunction "9_MNT@1") (pintype "passive"))
      (node (ref "H1") (pin "B3,2") (pinfunction "MOUNT_B3,2") (pintype "passive"))
      (node (ref "H3") (pin "B3,2") (pinfunction "MOUNT_B3,2") (pintype "passive"))
      (node (ref "H4") (pin "B3,2") (pinfunction "MOUNT_B3,2") (pintype "passive"))
      (node (ref "H7") (pin "B3,2") (pinfunction "MOUNT_B3,2") (pintype "passive"))
      (node (ref "HORN") (pin "P$2") (pinfunction "2_P$2") (pintype "passive"))
      (node (ref "HORN-RLY") (pin "C") (pinfunction "C_C") (pintype "passive"))
      (node (ref "IC1") (pin "3") (pinfunction "GND_3") (pintype "power_in"))
      (node (ref "IC2") (pin "3") (pinfunction "GND_3") (pintype "power_in"))
      (node (ref "IC3") (pin "3") (pinfunction "GND_3") (pintype "power_in"))
      (node (ref "IC4") (pin "2") (pinfunction "GND_2") (pintype "passive"))
      (node (ref "IC5") (pin "2") (pinfunction "GND_2") (pintype "passive"))
      (node (ref "IMU") (pin "GND") (pinfunction "3_GND") (pintype "passive"))
      (node (ref "IMU") (pin "MNT@0") (pinfunction "9_MNT@0") (pintype "passive"))
      (node (ref "IMU") (pin "MNT@1") (pinfunction "9_MNT@1") (pintype "passive"))
      (node (ref "IMU") (pin "MNT@2") (pinfunction "9_MNT@2") (pintype "passive"))
      (node (ref "IMU") (pin "MNT@3") (pinfunction "9_MNT@3") (pintype "passive"))
      (node (ref "J1") (pin "3") (pinfunction "3_3") (pintype "passive"))
      (node (ref "J10") (pin "3") (pinfunction "3_3") (pintype "passive"))
      (node (ref "J11") (pin "3") (pinfunction "3_3") (pintype "passive"))
      (node (ref "J2") (pin "3") (pinfunction "3_3") (pintype "passive"))
      (node (ref "J3") (pin "4") (pinfunction "4_4") (pintype "passive"))
      (node (ref "J5") (pin "3") (pinfunction "3_3") (pintype "passive"))
      (node (ref "J6") (pin "3") (pinfunction "3_3") (pintype "passive"))
      (node (ref "J7") (pin "16") (pinfunction "16_16") (pintype "passive"))
      (node (ref "J9") (pin "2") (pinfunction "2_2") (pintype "passive"))
      (node (ref "MOTOR-CTRL-RELAYS") (pin "2") (pinfunction "2_2") (pintype "passive"))
      (node (ref "MOTOR-CTRL-RELAYS") (pin "4") (pinfunction "4_4") (pintype "passive"))
      (node (ref "MOTOR-CTRL-RELAYS") (pin "7") (pinfunction "7_7") (pintype "passive"))
      (node (ref "POE-DEVICE") (pin "7") (pinfunction "7_7") (pintype "bidirectional"))
      (node (ref "POE-DEVICE") (pin "8") (pinfunction "8_8") (pintype "bidirectional"))
      (node (ref "POWER_INPUT") (pin "1") (pinfunction "1_1") (pintype "passive"))
      (node (ref "POWER_MON") (pin "12") (pinfunction "12_12") (pintype "passive"))
      (node (ref "POWER_MON") (pin "4") (pinfunction "4_4") (pintype "passive"))
      (node (ref "POWER_MON") (pin "8") (pinfunction "8_8") (pintype "passive"))
      (node (ref "POWER_STATE") (pin "P$3") (pinfunction "3_P$3") (pintype "passive"))
      (node (ref "PWR") (pin "C") (pinfunction "C_C") (pintype "passive"))
      (node (ref "R12") (pin "1") (pinfunction "1_1") (pintype "passive"))
      (node (ref "R18") (pin "1") (pinfunction "1_1") (pintype "passive"))
      (node (ref "R28") (pin "1") (pinfunction "1_1") (pintype "passive"))
      (node (ref "R33") (pin "1") (pinfunction "1_1") (pintype "passive"))
      (node (ref "R41") (pin "1") (pinfunction "1_1") (pintype "passive"))
      (node (ref "R47") (pin "1") (pinfunction "1_1") (pintype "passive"))
      (node (ref "R50") (pin "1") (pinfunction "1_1") (pintype "passive"))
      (node (ref "R56") (pin "1") (pinfunction "1_1") (pintype "passive"))
      (node (ref "R58") (pin "1") (pinfunction "1_1") (pintype "passive"))
      (node (ref "R6") (pin "1") (pinfunction "1_1") (pintype "passive"))
      (node (ref "R61") (pin "1") (pinfunction "1_1") (pintype "passive"))
      (node (ref "R74") (pin "1") (pinfunction "1_1") (pintype "passive"))
      (node (ref "R80") (pin "1") (pinfunction "1_1") (pintype "passive"))
      (node (ref "R86") (pin "1") (pinfunction "1_1") (pintype "passive"))
      (node (ref "R97") (pin "2") (pinfunction "2_2") (pintype "passive"))
      (node (ref "R98") (pin "2") (pinfunction "2_2") (pintype "passive"))
      (node (ref "R99") (pin "1") (pinfunction "1_1") (pintype "passive"))
      (node (ref "REV") (pin "A") (pinfunction "A_A") (pintype "passive"))
      (node (ref "RLY0") (pin "C") (pinfunction "C_C") (pintype "passive"))
      (node (ref "RLY1") (pin "C") (pinfunction "C_C") (pintype "passive"))
      (node (ref "RLY2") (pin "C") (pinfunction "C_C") (pintype "passive"))
      (node (ref "RLY3") (pin "C") (pinfunction "C_C") (pintype "passive"))
      (node (ref "RLY4") (pin "C") (pinfunction "C_C") (pintype "passive"))
      (node (ref "RLY5") (pin "C") (pinfunction "C_C") (pintype "passive"))
      (node (ref "RS485") (pin "P$3") (pinfunction "3_P$3") (pintype "passive"))
      (node (ref "SBUS-IN") (pin "P$1") (pinfunction "1_P$1") (pintype "passive"))
      (node (ref "SBUS-OUT") (pin "P$1") (pinfunction "1_P$1") (pintype "passive"))
      (node (ref "SERIAL_CONSOLE") (pin "P$4") (pinfunction "4_P$4") (pintype "passive"))
      (node (ref "STATUS_LIGHTS") (pin "P$3") (pinfunction "3_P$3") (pintype "passive"))
      (node (ref "STEERING") (pin "P$3") (pinfunction "3_P$3") (pintype "passive"))
      (node (ref "U$1") (pin "1") (pinfunction "GND_1") (pintype "power_in"))
      (node (ref "U$1") (pin "2") (pinfunction "GND_2") (pintype "power_in"))
      (node (ref "U$1") (pin "47") (pinfunction "GND_47") (pintype "power_in"))
      (node (ref "U$1") (pin "48") (pinfunction "GND_48") (pintype "power_in"))
      (node (ref "U$1") (pin "80") (pinfunction "GNDA_ADC_80") (pintype "passive"))
      (node (ref "U$1") (pin "89") (pinfunction "GND_89") (pintype "power_in"))
      (node (ref "U$1") (pin "90") (pinfunction "GND_90") (pintype "power_in"))
      (node (ref "U$1") (pin "91") (pinfunction "GND_91") (pintype "power_in"))
      (node (ref "U$1") (pin "92") (pinfunction "GND_92") (pintype "power_in"))
      (node (ref "U$2") (pin "2") (pinfunction "2_2") (pintype "passive"))
      (node (ref "U$2") (pin "25") (pinfunction "25_25") (pintype "passive"))
      (node (ref "U$2") (pin "3") (pinfunction "3_3") (pintype "passive"))
      (node (ref "U$2") (pin "4") (pinfunction "4_4") (pintype "passive"))
      (node (ref "U$2") (pin "9") (pinfunction "9_9") (pintype "passive"))
      (node (ref "U$3") (pin "24") (pinfunction "24_24") (pintype "passive"))
      (node (ref "U$3") (pin "25") (pinfunction "25_25") (pintype "passive"))
      (node (ref "U$4") (pin "24") (pinfunction "24_24") (pintype "passive"))
      (node (ref "U$4") (pin "25") (pinfunction "25_25") (pintype "passive"))
      (node (ref "U$5") (pin "2") (pinfunction "2_2") (pintype "passive"))
      (node (ref "U$5") (pin "25") (pinfunction "25_25") (pintype "passive"))
      (node (ref "U$5") (pin "3") (pinfunction "3_3") (pintype "passive"))
      (node (ref "U$5") (pin "4") (pinfunction "4_4") (pintype "passive"))
      (node (ref "U1") (pin "1") (pinfunction "GND_1") (pintype "passive"))
      (node (ref "U10") (pin "2") (pinfunction "GND_2") (pintype "bidirectional"))
      (node (ref "U11") (pin "1") (pinfunction "GND_1") (pintype "passive"))
      (node (ref "U12") (pin "2") (pinfunction "GND_2") (pintype "bidirectional"))
      (node (ref "U13") (pin "11") (pinfunction "GND_11") (pintype "bidirectional"))
      (node (ref "U15") (pin "7") (pinfunction "GND_7") (pintype "bidirectional"))
      (node (ref "U16") (pin "11") (pinfunction "GND_11") (pintype "bidirectional"))
      (node (ref "U17") (pin "11") (pinfunction "GND_11") (pintype "bidirectional"))
      (node (ref "U18") (pin "4") (pinfunction "GND_4") (pintype "bidirectional"))
      (node (ref "U18") (pin "8") (pinfunction "A1_8") (pintype "bidirectional"))
      (node (ref "U19") (pin "4") (pinfunction "GND_4") (pintype "bidirectional"))
      (node (ref "U19") (pin "7") (pinfunction "A0_7") (pintype "bidirectional"))
      (node (ref "U19") (pin "8") (pinfunction "A1_8") (pintype "bidirectional"))
      (node (ref "U2") (pin "1") (pinfunction "GND_1") (pintype "passive"))
      (node (ref "U20") (pin "1") (pinfunction "GND_1") (pintype "passive"))
      (node (ref "U21") (pin "2") (pinfunction "GND_2") (pintype "bidirectional"))
      (node (ref "U22") (pin "1") (pinfunction "GND_1") (pintype "passive"))
      (node (ref "U23") (pin "2") (pinfunction "GND_2") (pintype "bidirectional"))
      (node (ref "U24") (pin "1") (pinfunction "GND_1") (pintype "passive"))
      (node (ref "U25") (pin "2") (pinfunction "GND_2") (pintype "bidirectional"))
      (node (ref "U26") (pin "P$2") (pinfunction "GND_P$2") (pintype "bidirectional"))
      (node (ref "U27") (pin "2") (pinfunction "GND_2") (pintype "bidirectional"))
      (node (ref "U28") (pin "5") (pinfunction "GND_5") (pintype "bidirectional"))
      (node (ref "U29") (pin "11") (pinfunction "NC_11") (pintype "bidirectional"))
      (node (ref "U29") (pin "12") (pinfunction "PGND_12") (pintype "bidirectional"))
      (node (ref "U29") (pin "13") (pinfunction "PGND_13") (pintype "bidirectional"))
      (node (ref "U29") (pin "14") (pinfunction "PGND_14") (pintype "bidirectional"))
      (node (ref "U29") (pin "6") (pinfunction "SYN_6") (pintype "bidirectional"))
      (node (ref "U29") (pin "7") (pinfunction "AGND_7") (pintype "bidirectional"))
      (node (ref "U29") (pin "P$1") (pinfunction "PAD_P$1") (pintype "bidirectional"))
      (node (ref "U3") (pin "2") (pinfunction "GND_2") (pintype "bidirectional"))
      (node (ref "U4") (pin "1") (pinfunction "GND_1") (pintype "passive"))
      (node (ref "U5") (pin "2") (pinfunction "GND_2") (pintype "bidirectional"))
      (node (ref "U6") (pin "1") (pinfunction "GND_1") (pintype "passive"))
      (node (ref "U7") (pin "2") (pinfunction "GND_2") (pintype "bidirectional"))
      (node (ref "U8") (pin "1") (pinfunction "GND_1") (pintype "passive"))
      (node (ref "U9") (pin "2") (pinfunction "GND_2") (pintype "bidirectional"))
    )
    (net (code "52") (name "GNSS_ENABLE") (class "Default")
      (node (ref "GPS") (pin "EN") (pinfunction "8_EN") (pintype "passive"))
      (node (ref "J5") (pin "8") (pinfunction "8_8") (pintype "passive"))
      (node (ref "U$1") (pin "58") (pinfunction "GPIO1_28_58") (pintype "passive"))
      (node (ref "U$2") (pin "20") (pinfunction "20_20") (pintype "passive"))
    )
    (net (code "53") (name "GNSS_FIX") (class "Default")
      (node (ref "GPS") (pin "FIX") (pinfunction "7_FIX") (pintype "passive"))
      (node (ref "J5") (pin "6") (pinfunction "6_6") (pintype "passive"))
      (node (ref "U$1") (pin "61") (pinfunction "GPIO1_16_61") (pintype "passive"))
      (node (ref "U$5") (pin "18") (pinfunction "18_18") (pintype "passive"))
    )
    (net (code "54") (name "GNSS_RX") (class "Default")
      (node (ref "GPS") (pin "RX") (pinfunction "2_RX") (pintype "passive"))
      (node (ref "J5") (pin "4") (pinfunction "4_4") (pintype "passive"))
      (node (ref "U$1") (pin "59") (pinfunction "UART4_TXD_59") (pintype "passive"))
      (node (ref "U$5") (pin "19") (pinfunction "19_19") (pintype "passive"))
    )
    (net (code "55") (name "GNSS_TX") (class "Default")
      (node (ref "GPS") (pin "TX") (pinfunction "3_TX") (pintype "passive"))
      (node (ref "J5") (pin "5") (pinfunction "5_5") (pintype "passive"))
      (node (ref "SJ1") (pin "1") (pinfunction "1_1") (pintype "passive"))
      (node (ref "U$1") (pin "57") (pinfunction "UART4_RXD_57") (pintype "passive"))
      (node (ref "U$5") (pin "20") (pinfunction "20_20") (pintype "passive"))
    )
    (net (code "56") (name "I2C_SCL_5V") (class "Default")
      (node (ref "AUX_GPIO") (pin "4") (pinfunction "4_4") (pintype "passive"))
      (node (ref "R51") (pin "1") (pinfunction "1_1") (pintype "passive"))
      (node (ref "U18") (pin "3") (pinfunction "SCL_3") (pintype "bidirectional"))
      (node (ref "U19") (pin "3") (pinfunction "SCL_3") (pintype "bidirectional"))
      (node (ref "U26") (pin "P$1") (pinfunction "B2_P$1") (pintype "bidirectional"))
    )
    (net (code "57") (name "I2C_SDA_5V") (class "Default")
      (node (ref "AUX_GPIO") (pin "3") (pinfunction "3_3") (pintype "passive"))
      (node (ref "R52") (pin "1") (pinfunction "1_1") (pintype "passive"))
      (node (ref "U18") (pin "2") (pinfunction "SDA_2") (pintype "bidirectional"))
      (node (ref "U19") (pin "2") (pinfunction "SDA_2") (pintype "bidirectional"))
      (node (ref "U26") (pin "P$8") (pinfunction "B1_P$8") (pintype "bidirectional"))
    )
    (net (code "58") (name "MOT_CURRENT") (class "Default")
      (node (ref "POWER_MON") (pin "3") (pinfunction "3_3") (pintype "passive"))
      (node (ref "R112") (pin "4") (pinfunction "2_4") (pintype "passive"))
    )
    (net (code "59") (name "MOT_VOLTAGE") (class "Default")
      (node (ref "POWER_MON") (pin "2") (pinfunction "2_2") (pintype "passive"))
      (node (ref "R112") (pin "6") (pinfunction "2_6") (pintype "passive"))
    )
    (net (code "60") (name "N$21") (class "Default")
      (node (ref "U$1") (pin "67") (pinfunction "UART2_TXD_67") (pintype "passive"))
      (node (ref "U$5") (pin "15") (pinfunction "15_15") (pintype "passive"))
    )
    (net (code "61") (name "N$22") (class "Default")
      (node (ref "U$1") (pin "74") (pinfunction "SPI1_CS0_74") (pintype "passive"))
      (node (ref "U$2") (pin "12") (pinfunction "12_12") (pintype "passive"))
    )
    (net (code "62") (name "N$104") (class "Default")
      (node (ref "U$1") (pin "88") (pinfunction "GPIO0_7_88") (pintype "passive"))
      (node (ref "U$2") (pin "5") (pinfunction "5_5") (pintype "passive"))
    )
    (net (code "63") (name "N$106") (class "Default")
      (node (ref "U$1") (pin "84") (pinfunction "AIN3_84") (pintype "passive"))
      (node (ref "U$2") (pin "7") (pinfunction "7_7") (pintype "passive"))
    )
    (net (code "64") (name "N$107") (class "Default")
      (node (ref "U$1") (pin "82") (pinfunction "AIN5_82") (pintype "passive"))
      (node (ref "U$2") (pin "8") (pinfunction "8_8") (pintype "passive"))
    )
    (net (code "65") (name "N$108") (class "Default")
      (node (ref "U$1") (pin "78") (pinfunction "VDD_ADC_78") (pintype "passive"))
      (node (ref "U$2") (pin "10") (pinfunction "10_10") (pintype "passive"))
    )
    (net (code "66") (name "N$119") (class "Default")
      (node (ref "U$1") (pin "46") (pinfunction "GPIO2_7_46") (pintype "passive"))
      (node (ref "U$3") (pin "2") (pinfunction "2_2") (pintype "passive"))
    )
    (net (code "67") (name "N$120") (class "Default")
      (node (ref "U$1") (pin "44") (pinfunction "GPIO2_9_44") (pintype "passive"))
      (node (ref "U$3") (pin "3") (pinfunction "3_3") (pintype "passive"))
    )
    (net (code "68") (name "N$121") (class "Default")
      (node (ref "U$1") (pin "42") (pinfunction "GPIO2_11_42") (pintype "passive"))
      (node (ref "U$3") (pin "4") (pinfunction "4_4") (pintype "passive"))
    )
    (net (code "69") (name "N$141") (class "Default")
      (node (ref "U$1") (pin "45") (pinfunction "GPIO2_6_45") (pintype "passive"))
      (node (ref "U$4") (pin "2") (pinfunction "2_2") (pintype "passive"))
    )
    (net (code "70") (name "N$142") (class "Default")
      (node (ref "U$1") (pin "43") (pinfunction "GPIO2_8_43") (pintype "passive"))
      (node (ref "U$4") (pin "3") (pinfunction "3_3") (pintype "passive"))
    )
    (net (code "71") (name "N$143") (class "Default")
      (node (ref "U$1") (pin "41") (pinfunction "GPIO2_10_41") (pintype "passive"))
      (node (ref "U$4") (pin "4") (pinfunction "4_4") (pintype "passive"))
    )
    (net (code "72") (name "N$163") (class "Default")
      (node (ref "U$1") (pin "87") (pinfunction "CLKOUT2_87") (pintype "input"))
      (node (ref "U$5") (pin "5") (pinfunction "5_5") (pintype "passive"))
    )
    (net (code "73") (name "N$164") (class "Default")
      (node (ref "U$1") (pin "85") (pinfunction "AIN0_85") (pintype "power_in"))
      (node (ref "U$5") (pin "6") (pinfunction "6_6") (pintype "passive"))
    )
    (net (code "74") (name "N$165") (class "Default")
      (node (ref "U$1") (pin "83") (pinfunction "AIN2_83") (pintype "passive"))
      (node (ref "U$5") (pin "7") (pinfunction "7_7") (pintype "passive"))
    )
    (net (code "75") (name "N$166") (class "Default")
      (node (ref "U$1") (pin "81") (pinfunction "AIN6_81") (pintype "passive"))
      (node (ref "U$5") (pin "8") (pinfunction "8_8") (pintype "passive"))
    )
    (net (code "76") (name "N$167") (class "Default")
      (node (ref "U$1") (pin "79") (pinfunction "AIN4_79") (pintype "passive"))
      (node (ref "U$5") (pin "9") (pinfunction "9_9") (pintype "passive"))
    )
    (net (code "77") (name "N$170") (class "Default")
      (node (ref "U$1") (pin "73") (pinfunction "GPIO3_19_73") (pintype "passive"))
      (node (ref "U$5") (pin "12") (pinfunction "12_12") (pintype "passive"))
    )
    (net (code "78") (name "N$171") (class "Default")
      (node (ref "U$1") (pin "71") (pinfunction "GPIO3_21_71") (pintype "passive"))
      (node (ref "U$5") (pin "13") (pinfunction "13_13") (pintype "passive"))
    )
    (net (code "79") (name "N$172") (class "Default")
      (node (ref "U$1") (pin "69") (pinfunction "GPIO1_17_69") (pintype "passive"))
      (node (ref "U$5") (pin "14") (pinfunction "14_14") (pintype "passive"))
    )
    (net (code "80") (name "Net-(5V-STAT-PadA)") (class "Default")
      (node (ref "5V-STAT") (pin "A") (pinfunction "A_A") (pintype "passive"))
      (node (ref "R38") (pin "1") (pinfunction "1_1") (pintype "passive"))
    )
    (net (code "81") (name "Net-(7V4-STAT-PadA)") (class "Default")
      (node (ref "7V4-STAT") (pin "A") (pinfunction "A_A") (pintype "passive"))
      (node (ref "R39") (pin "1") (pinfunction "1_1") (pintype "passive"))
    )
    (net (code "82") (name "Net-(BBB_RESET-2)") (class "Default")
      (node (ref "BBB_RESET") (pin "P$2") (pinfunction "2_P$2") (pintype "passive"))
      (node (ref "J10") (pin "2") (pinfunction "2_2") (pintype "passive"))
      (node (ref "R96") (pin "1") (pinfunction "1_1") (pintype "passive"))
    )
    (net (code "83") (name "Net-(BLOWN-PadA)") (class "Default")
      (node (ref "BLOWN") (pin "A") (pinfunction "A_A") (pintype "passive"))
      (node (ref "R100") (pin "2") (pinfunction "2_2") (pintype "passive"))
    )
    (net (code "84") (name "Net-(C33-Pad1)") (class "Default")
      (node (ref "C33") (pin "1") (pinfunction "1_1") (pintype "passive"))
      (node (ref "R26") (pin "1") (pinfunction "1_1") (pintype "passive"))
    )
    (net (code "85") (name "Net-(C41B-1)") (class "Default")
      (node (ref "C41") (pin "3") (pinfunction "1_3") (pintype "passive"))
      (node (ref "R110") (pin "5") (pinfunction "1_5") (pintype "passive"))
      (node (ref "U18") (pin "14") (pinfunction "IN2_14") (pintype "bidirectional"))
    )
    (net (code "86") (name "Net-(C41C-1)") (class "Default")
      (node (ref "C41") (pin "5") (pinfunction "1_5") (pintype "passive"))
      (node (ref "R110") (pin "3") (pinfunction "1_3") (pintype "passive"))
      (node (ref "U18") (pin "15") (pinfunction "IN1_15") (pintype "bidirectional"))
    )
    (net (code "87") (name "Net-(C41D-1)") (class "Default")
      (node (ref "C41") (pin "7") (pinfunction "1_7") (pintype "passive"))
      (node (ref "R110") (pin "1") (pinfunction "1_1") (pintype "passive"))
      (node (ref "U18") (pin "16") (pinfunction "IN0_16") (pintype "bidirectional"))
    )
    (net (code "88") (name "Net-(C42B-1)") (class "Default")
      (node (ref "C42") (pin "3") (pinfunction "1_3") (pintype "passive"))
      (node (ref "R111") (pin "5") (pinfunction "1_5") (pintype "passive"))
      (node (ref "U18") (pin "10") (pinfunction "IN6_10") (pintype "bidirectional"))
    )
    (net (code "89") (name "Net-(C42C-1)") (class "Default")
      (node (ref "C42") (pin "5") (pinfunction "1_5") (pintype "passive"))
      (node (ref "R111") (pin "3") (pinfunction "1_3") (pintype "passive"))
      (node (ref "U18") (pin "11") (pinfunction "IN5_11") (pintype "bidirectional"))
    )
    (net (code "90") (name "Net-(C42D-1)") (class "Default")
      (node (ref "C42") (pin "7") (pinfunction "1_7") (pintype "passive"))
      (node (ref "R111") (pin "1") (pinfunction "1_1") (pintype "passive"))
      (node (ref "U18") (pin "12") (pinfunction "IN4_12") (pintype "bidirectional"))
    )
    (net (code "91") (name "Net-(C46-Pad1)") (class "Default")
      (node (ref "C46") (pin "1") (pinfunction "1_1") (pintype "passive"))
      (node (ref "R59") (pin "1") (pinfunction "1_1") (pintype "passive"))
    )
    (net (code "92") (name "Net-(C49B-1)") (class "Default")
      (node (ref "C49") (pin "3") (pinfunction "1_3") (pintype "passive"))
      (node (ref "R112") (pin "5") (pinfunction "1_5") (pintype "passive"))
      (node (ref "U19") (pin "14") (pinfunction "IN2_14") (pintype "bidirectional"))
    )
    (net (code "93") (name "Net-(C49C-1)") (class "Default")
      (node (ref "C49") (pin "5") (pinfunction "1_5") (pintype "passive"))
      (node (ref "R112") (pin "3") (pinfunction "1_3") (pintype "passive"))
      (node (ref "U19") (pin "15") (pinfunction "IN1_15") (pintype "bidirectional"))
    )
    (net (code "94") (name "Net-(C49D-1)") (class "Default")
      (node (ref "C49") (pin "7") (pinfunction "1_7") (pintype "passive"))
      (node (ref "R112") (pin "1") (pinfunction "1_1") (pintype "passive"))
      (node (ref "U19") (pin "16") (pinfunction "IN0_16") (pintype "bidirectional"))
    )
    (net (code "95") (name "Net-(C50B-1)") (class "Default")
      (node (ref "C50") (pin "3") (pinfunction "1_3") (pintype "passive"))
      (node (ref "R113") (pin "5") (pinfunction "1_5") (pintype "passive"))
      (node (ref "U19") (pin "10") (pinfunction "IN6_10") (pintype "bidirectional"))
    )
    (net (code "96") (name "Net-(C50C-1)") (class "Default")
      (node (ref "C50") (pin "5") (pinfunction "1_5") (pintype "passive"))
      (node (ref "R113") (pin "3") (pinfunction "1_3") (pintype "passive"))
      (node (ref "U19") (pin "11") (pinfunction "IN5_11") (pintype "bidirectional"))
    )
    (net (code "97") (name "Net-(C50D-1)") (class "Default")
      (node (ref "C50") (pin "7") (pinfunction "1_7") (pintype "passive"))
      (node (ref "R113") (pin "1") (pinfunction "1_1") (pintype "passive"))
      (node (ref "U19") (pin "12") (pinfunction "IN4_12") (pintype "bidirectional"))
    )
    (net (code "98") (name "Net-(CELLA-1)") (class "Default")
      (node (ref "CELL") (pin "SPKR-") (pinfunction "1_SPKR-") (pintype "passive"))
      (node (ref "J7") (pin "1") (pinfunction "1_1") (pintype "passive"))
    )
    (net (code "99") (name "Net-(CELLA-2)") (class "Default")
      (node (ref "CELL") (pin "SPKR+") (pinfunction "2_SPKR+") (pintype "passive"))
      (node (ref "J7") (pin "2") (pinfunction "2_2") (pintype "passive"))
    )
    (net (code "100") (name "Net-(CELLA-3)") (class "Default")
      (node (ref "CELL") (pin "MIC-") (pinfunction "3_MIC-") (pintype "passive"))
      (node (ref "J7") (pin "3") (pinfunction "3_3") (pintype "passive"))
    )
    (net (code "101") (name "Net-(CELLA-4)") (class "Default")
      (node (ref "CELL") (pin "MIC+") (pinfunction "4_MIC+") (pintype "passive"))
      (node (ref "J7") (pin "4") (pinfunction "4_4") (pintype "passive"))
    )
    (net (code "102") (name "Net-(CELLA-10)") (class "Default")
      (node (ref "CELL") (pin "DTR") (pinfunction "10_DTR") (pintype "passive"))
      (node (ref "J7") (pin "10") (pinfunction "10_10") (pintype "passive"))
    )
    (net (code "103") (name "Net-(CELLA-17)") (class "Default")
      (node (ref "CELL") (pin "BAT") (pinfunction "17_BAT") (pintype "passive"))
      (node (ref "J7") (pin "17") (pinfunction "17_17") (pintype "passive"))
    )
    (net (code "104") (name "Net-(D20-PadA)") (class "Default")
      (node (ref "D20") (pin "A") (pinfunction "A_A") (pintype "passive"))
      (node (ref "L3") (pin "2") (pinfunction "2_2") (pintype "passive"))
      (node (ref "U29") (pin "1") (pinfunction "SW_1") (pintype "bidirectional"))
      (node (ref "U29") (pin "2") (pinfunction "SW_2") (pintype "bidirectional"))
    )
    (net (code "105") (name "Net-(DISARM-PadA)") (class "Default")
      (node (ref "DISARM") (pin "A") (pinfunction "A_A") (pintype "passive"))
      (node (ref "R68") (pin "1") (pinfunction "1_1") (pintype "passive"))
    )
    (net (code "106") (name "Net-(ENABLE-PadA)") (class "Default")
      (node (ref "ENABLE") (pin "A") (pinfunction "A_A") (pintype "passive"))
      (node (ref "R87") (pin "1") (pinfunction "1_1") (pintype "passive"))
    )
    (net (code "107") (name "Net-(F1-1)") (class "Default")
      (node (ref "F1") (pin "P$1") (pinfunction "1_P$1") (pintype "passive"))
      (node (ref "POWER_INPUT") (pin "2") (pinfunction "2_2") (pintype "passive"))
      (node (ref "R100") (pin "1") (pinfunction "1_1") (pintype "passive"))
      (node (ref "R24") (pin "2") (pinfunction "2_2") (pintype "passive"))
    )
    (net (code "108") (name "Net-(F1-2)") (class "Default")
      (node (ref "BLOWN") (pin "C") (pinfunction "C_C") (pintype "passive"))
      (node (ref "F1") (pin "P$2") (pinfunction "2_P$2") (pintype "passive"))
      (node (ref "T1") (pin "5") (pinfunction "D_5") (pintype "bidirectional"))
      (node (ref "T1") (pin "6") (pinfunction "D_6") (pintype "bidirectional"))
      (node (ref "T1") (pin "7") (pinfunction "D_7") (pintype "bidirectional"))
      (node (ref "T1") (pin "8") (pinfunction "D_8") (pintype "bidirectional"))
    )
    (net (code "109") (name "Net-(F2-1)") (class "Default")
      (node (ref "F2") (pin "P$1") (pinfunction "1_P$1") (pintype "passive"))
      (node (ref "J2") (pin "1") (pinfunction "1_1") (pintype "passive"))
      (node (ref "STATUS_LIGHTS") (pin "P$1") (pinfunction "1_P$1") (pintype "passive"))
    )
    (net (code "110") (name "Net-(F2-2)") (class "Default")
      (node (ref "C20") (pin "1") (pinfunction "1_1") (pintype "passive"))
      (node (ref "F2") (pin "P$2") (pinfunction "2_P$2") (pintype "passive"))
      (node (ref "IC5") (pin "3") (pinfunction "VO_3") (pintype "passive"))
    )
    (net (code "111") (name "Net-(FAULT_0-PadA)") (class "Default")
      (node (ref "FAULT_0") (pin "A") (pinfunction "A_A") (pintype "passive"))
      (node (ref "R101") (pin "1") (pinfunction "1_1") (pintype "passive"))
    )
    (net (code "112") (name "Net-(FAULT_1-PadA)") (class "Default")
      (node (ref "FAULT_1") (pin "A") (pinfunction "A_A") (pintype "passive"))
      (node (ref "R102") (pin "1") (pinfunction "1_1") (pintype "passive"))
    )
    (net (code "113") (name "Net-(FAULT_2-PadA)") (class "Default")
      (node (ref "FAULT_2") (pin "A") (pinfunction "A_A") (pintype "passive"))
      (node (ref "R103") (pin "1") (pinfunction "1_1") (pintype "passive"))
    )
    (net (code "114") (name "Net-(FAULT_3-PadA)") (class "Default")
      (node (ref "FAULT_3") (pin "A") (pinfunction "A_A") (pintype "passive"))
      (node (ref "R104") (pin "1") (pinfunction "1_1") (pintype "passive"))
    )
    (net (code "115") (name "Net-(FAULT_4-PadA)") (class "Default")
      (node (ref "FAULT_4") (pin "A") (pinfunction "A_A") (pintype "passive"))
      (node (ref "R105") (pin "1") (pinfunction "1_1") (pintype "passive"))
    )
    (net (code "116") (name "Net-(FAULT_5-PadA)") (class "Default")
      (node (ref "FAULT_5") (pin "A") (pinfunction "A_A") (pintype "passive"))
      (node (ref "R106") (pin "1") (pinfunction "1_1") (pintype "passive"))
    )
    (net (code "117") (name "Net-(FAULT_DISARM-PadA)") (class "Default")
      (node (ref "FAULT_DISARM") (pin "A") (pinfunction "A_A") (pintype "passive"))
      (node (ref "R108") (pin "1") (pinfunction "1_1") (pintype "passive"))
    )
    (net (code "118") (name "Net-(FAULT_ENABLE-PadA)") (class "Default")
      (node (ref "FAULT_ENABLE") (pin "A") (pinfunction "A_A") (pintype "passive"))
      (node (ref "R107") (pin "1") (pinfunction "1_1") (pintype "passive"))
    )
    (net (code "119") (name "Net-(FAULT_HORN-PadA)") (class "Default")
      (node (ref "FAULT_HORN") (pin "A") (pinfunction "A_A") (pintype "passive"))
      (node (ref "R109") (pin "1") (pinfunction "1_1") (pintype "passive"))
    )
    (net (code "120") (name "Net-(GPSA-1)") (class "Default")
      (node (ref "GPS") (pin "PPS") (pinfunction "1_PPS") (pintype "passive"))
      (node (ref "J5") (pin "1") (pinfunction "1_1") (pintype "passive"))
    )
    (net (code "121") (name "Net-(GPSA-4)") (class "Default")
      (node (ref "GPS") (pin "VBAT") (pinfunction "4_VBAT") (pintype "passive"))
      (node (ref "J5") (pin "7") (pinfunction "7_7") (pintype "passive"))
    )
    (net (code "122") (name "Net-(GPSA-9)") (class "Default")
      (node (ref "GPS") (pin "3V3") (pinfunction "9_3V3") (pintype "passive"))
      (node (ref "J5") (pin "9") (pinfunction "9_9") (pintype "passive"))
    )
    (net (code "123") (name "Net-(HORN-1)") (class "Default")
      (node (ref "D16") (pin "A") (pinfunction "A_A") (pintype "passive"))
      (node (ref "D17") (pin "C") (pinfunction "C_C") (pintype "passive"))
      (node (ref "HORN") (pin "P$1") (pinfunction "1_P$1") (pintype "passive"))
      (node (ref "J9") (pin "1") (pinfunction "1_1") (pintype "passive"))
      (node (ref "R79") (pin "2") (pinfunction "2_2") (pintype "passive"))
      (node (ref "R88") (pin "2") (pinfunction "2_2") (pintype "passive"))
      (node (ref "U23") (pin "4") (pinfunction "VIN-_4") (pintype "bidirectional"))
    )
    (net (code "124") (name "Net-(HORN-RLY-PadA)") (class "Default")
      (node (ref "HORN-RLY") (pin "A") (pinfunction "A_A") (pintype "passive"))
      (node (ref "R88") (pin "1") (pinfunction "1_1") (pintype "passive"))
    )
    (net (code "125") (name "Net-(IC1A-O)") (class "Default")
      (node (ref "IC1") (pin "4") (pinfunction "O_4") (pintype "output"))
      (node (ref "U15") (pin "3") (pinfunction "EN_3") (pintype "bidirectional"))
    )
    (net (code "126") (name "Net-(IC2A-I)") (class "Default")
      (node (ref "D21") (pin "C") (pinfunction "C_C") (pintype "passive"))
      (node (ref "IC2") (pin "2") (pinfunction "I_2") (pintype "input"))
      (node (ref "R91") (pin "2") (pinfunction "2_2") (pintype "passive"))
    )
    (net (code "127") (name "Net-(IC2A-O)") (class "Default")
      (node (ref "IC2") (pin "4") (pinfunction "O_4") (pintype "open_collector"))
      (node (ref "R57") (pin "1") (pinfunction "1_1") (pintype "passive"))
      (node (ref "SJ1") (pin "2") (pinfunction "2_2") (pintype "passive"))
    )
    (net (code "128") (name "Net-(IC3A-I)") (class "Default")
      (node (ref "D28") (pin "C") (pinfunction "C_C") (pintype "passive"))
      (node (ref "IC3") (pin "2") (pinfunction "I_2") (pintype "input"))
      (node (ref "R96") (pin "2") (pinfunction "2_2") (pintype "passive"))
    )
    (net (code "129") (name "Net-(IMUA-2)") (class "Default")
      (node (ref "IMU") (pin "3VO") (pinfunction "2_3VO") (pintype "passive"))
      (node (ref "J6") (pin "2") (pinfunction "2_2") (pintype "passive"))
    )
    (net (code "130") (name "Net-(IMUA-6)") (class "Default")
      (node (ref "IMU") (pin "GINT") (pinfunction "6_GINT") (pintype "passive"))
      (node (ref "J6") (pin "6") (pinfunction "6_6") (pintype "passive"))
    )
    (net (code "131") (name "Net-(IMUA-7)") (class "Default")
      (node (ref "IMU") (pin "GRDY") (pinfunction "7_GRDY") (pintype "passive"))
      (node (ref "J6") (pin "7") (pinfunction "7_7") (pintype "passive"))
    )
    (net (code "132") (name "Net-(IMUA-8)") (class "Default")
      (node (ref "IMU") (pin "LIN1") (pinfunction "8_LIN1") (pintype "passive"))
      (node (ref "J6") (pin "8") (pinfunction "8_8") (pintype "passive"))
    )
    (net (code "133") (name "Net-(IMUA-9)") (class "Default")
      (node (ref "IMU") (pin "LIN2") (pinfunction "9_LIN2") (pintype "passive"))
      (node (ref "J6") (pin "9") (pinfunction "9_9") (pintype "passive"))
    )
    (net (code "134") (name "Net-(IMUA-10)") (class "Default")
      (node (ref "IMU") (pin "LRDY") (pinfunction "10_LRDY") (pintype "passive"))
      (node (ref "J6") (pin "10") (pinfunction "10_10") (pintype "passive"))
    )
    (net (code "135") (name "Net-(POE-DEVICE-Pad1)") (class "Default")
      (node (ref "POE-DEVICE") (pin "1") (pinfunction "1_1") (pintype "bidirectional"))
      (node (ref "POE-LAN") (pin "1") (pinfunction "1_1") (pintype "bidirectional"))
    )
    (net (code "136") (name "Net-(POE-DEVICE-Pad2)") (class "Default")
      (node (ref "POE-DEVICE") (pin "2") (pinfunction "2_2") (pintype "bidirectional"))
      (node (ref "POE-LAN") (pin "2") (pinfunction "2_2") (pintype "bidirectional"))
    )
    (net (code "137") (name "Net-(POE-DEVICE-Pad3)") (class "Default")
      (node (ref "POE-DEVICE") (pin "3") (pinfunction "3_3") (pintype "bidirectional"))
      (node (ref "POE-LAN") (pin "3") (pinfunction "3_3") (pintype "bidirectional"))
    )
    (net (code "138") (name "Net-(POE-DEVICE-Pad6)") (class "Default")
      (node (ref "POE-DEVICE") (pin "6") (pinfunction "6_6") (pintype "bidirectional"))
      (node (ref "POE-LAN") (pin "6") (pinfunction "6_6") (pintype "bidirectional"))
    )
    (net (code "139") (name "Net-(POWER_STATE-1)") (class "Default")
      (node (ref "ENABLE/DISARM") (pin "1") (pinfunction "1_1") (pintype "passive"))
      (node (ref "POWER_STATE") (pin "P$1") (pinfunction "1_P$1") (pintype "passive"))
      (node (ref "R89") (pin "1") (pinfunction "1_1") (pintype "passive"))
    )
    (net (code "140") (name "Net-(POWER_STATE-2)") (class "Default")
      (node (ref "ENABLE/DISARM") (pin "2") (pinfunction "2_2") (pintype "passive"))
      (node (ref "POWER_STATE") (pin "P$2") (pinfunction "2_P$2") (pintype "passive"))
      (node (ref "R90") (pin "1") (pinfunction "1_1") (pintype "passive"))
    )
    (net (code "141") (name "Net-(POWER_STATE-5)") (class "Default")
      (node (ref "ENABLE/DISARM") (pin "5") (pinfunction "5_5") (pintype "passive"))
      (node (ref "POWER_STATE") (pin "P$5") (pinfunction "5_P$5") (pintype "passive"))
      (node (ref "SJ2") (pin "1") (pinfunction "1_1") (pintype "passive"))
    )
    (net (code "142") (name "Net-(PWR-PadA)") (class "Default")
      (node (ref "PWR") (pin "A") (pinfunction "A_A") (pintype "passive"))
      (node (ref "R24") (pin "1") (pinfunction "1_1") (pintype "passive"))
      (node (ref "REV") (pin "C") (pinfunction "C_C") (pintype "passive"))
    )
    (net (code "143") (name "Net-(R62-Pad1)") (class "Default")
      (node (ref "R62") (pin "1") (pinfunction "1_1") (pintype "passive"))
      (node (ref "RLY0") (pin "A") (pinfunction "A_A") (pintype "passive"))
    )
    (net (code "144") (name "Net-(R63-Pad1)") (class "Default")
      (node (ref "R63") (pin "1") (pinfunction "1_1") (pintype "passive"))
      (node (ref "RLY1") (pin "A") (pinfunction "A_A") (pintype "passive"))
    )
    (net (code "145") (name "Net-(R64-Pad1)") (class "Default")
      (node (ref "R64") (pin "1") (pinfunction "1_1") (pintype "passive"))
      (node (ref "RLY2") (pin "A") (pinfunction "A_A") (pintype "passive"))
    )
    (net (code "146") (name "Net-(R65-Pad1)") (class "Default")
      (node (ref "R65") (pin "1") (pinfunction "1_1") (pintype "passive"))
      (node (ref "RLY3") (pin "A") (pinfunction "A_A") (pintype "passive"))
    )
    (net (code "147") (name "Net-(R66-Pad1)") (class "Default")
      (node (ref "R66") (pin "1") (pinfunction "1_1") (pintype "passive"))
      (node (ref "RLY4") (pin "A") (pinfunction "A_A") (pintype "passive"))
    )
    (net (code "148") (name "Net-(R67-Pad1)") (class "Default")
      (node (ref "R67") (pin "1") (pinfunction "1_1") (pintype "passive"))
      (node (ref "RLY5") (pin "A") (pinfunction "A_A") (pintype "passive"))
    )
    (net (code "149") (name "Net-(R110D-1)") (class "Default")
      (node (ref "C41") (pin "1") (pinfunction "1_1") (pintype "passive"))
      (node (ref "R110") (pin "7") (pinfunction "1_7") (pintype "passive"))
      (node (ref "U18") (pin "13") (pinfunction "IN3_13") (pintype "bidirectional"))
    )
    (net (code "150") (name "Net-(R111D-1)") (class "Default")
      (node (ref "C42") (pin "1") (pinfunction "1_1") (pintype "passive"))
      (node (ref "R111") (pin "7") (pinfunction "1_7") (pintype "passive"))
      (node (ref "U18") (pin "9") (pinfunction "IN7_9") (pintype "bidirectional"))
    )
    (net (code "151") (name "Net-(R112D-1)") (class "Default")
      (node (ref "C49") (pin "1") (pinfunction "1_1") (pintype "passive"))
      (node (ref "R112") (pin "7") (pinfunction "1_7") (pintype "passive"))
      (node (ref "U19") (pin "13") (pinfunction "IN3_13") (pintype "bidirectional"))
    )
    (net (code "152") (name "Net-(R113D-1)") (class "Default")
      (node (ref "C50") (pin "1") (pinfunction "1_1") (pintype "passive"))
      (node (ref "R113") (pin "7") (pinfunction "1_7") (pintype "passive"))
      (node (ref "U19") (pin "9") (pinfunction "IN7_9") (pintype "bidirectional"))
    )
    (net (code "153") (name "Net-(RS485-1)") (class "Default")
      (node (ref "J11") (pin "1") (pinfunction "1_1") (pintype "passive"))
      (node (ref "RS485") (pin "P$1") (pinfunction "1_P$1") (pintype "passive"))
      (node (ref "U28") (pin "7") (pinfunction "B_7") (pintype "bidirectional"))
    )
    (net (code "154") (name "Net-(RS485-2)") (class "Default")
      (node (ref "J11") (pin "2") (pinfunction "2_2") (pintype "passive"))
      (node (ref "RS485") (pin "P$2") (pinfunction "2_P$2") (pintype "passive"))
      (node (ref "U28") (pin "6") (pinfunction "A_6") (pintype "bidirectional"))
    )
    (net (code "155") (name "Net-(SBUS-IN-3)") (class "Default")
      (node (ref "R91") (pin "1") (pinfunction "1_1") (pintype "passive"))
      (node (ref "SBUS-IN") (pin "P$3") (pinfunction "3_P$3") (pintype "passive"))
      (node (ref "SBUS-OUT") (pin "P$3") (pinfunction "3_P$3") (pintype "passive"))
    )
    (net (code "156") (name "Net-(SERIAL_CONSOLE-2)") (class "Default")
      (node (ref "J3") (pin "2") (pinfunction "2_2") (pintype "passive"))
      (node (ref "R93") (pin "1") (pinfunction "1_1") (pintype "passive"))
      (node (ref "SERIAL_CONSOLE") (pin "P$2") (pinfunction "2_P$2") (pintype "passive"))
    )
    (net (code "157") (name "Net-(SERIAL_CONSOLE-3)") (class "Default")
      (node (ref "J3") (pin "3") (pinfunction "3_3") (pintype "passive"))
      (node (ref "R94") (pin "1") (pinfunction "1_1") (pintype "passive"))
      (node (ref "SERIAL_CONSOLE") (pin "P$3") (pinfunction "3_P$3") (pintype "passive"))
    )
    (net (code "158") (name "Net-(STATUS_LIGHTS-2)") (class "Default")
      (node (ref "J2") (pin "2") (pinfunction "2_2") (pintype "passive"))
      (node (ref "R95") (pin "1") (pinfunction "1_1") (pintype "passive"))
      (node (ref "STATUS_LIGHTS") (pin "P$2") (pinfunction "2_P$2") (pintype "passive"))
    )
    (net (code "159") (name "Net-(STEERING-2)") (class "Default")
      (node (ref "J1") (pin "2") (pinfunction "2_2") (pintype "passive"))
      (node (ref "R92") (pin "1") (pinfunction "1_1") (pintype "passive"))
      (node (ref "STEERING") (pin "P$2") (pinfunction "2_P$2") (pintype "passive"))
    )
    (net (code "160") (name "Net-(T1-G)") (class "Default")
      (node (ref "R99") (pin "2") (pinfunction "2_2") (pintype "passive"))
      (node (ref "T1") (pin "4") (pinfunction "G_4") (pintype "bidirectional"))
    )
    (net (code "161") (name "Net-(U$1-GPIO2_12)") (class "Default")
      (node (ref "U$1") (pin "39") (pinfunction "GPIO2_12_39") (pintype "passive"))
      (node (ref "U$4") (pin "5") (pinfunction "5_5") (pintype "passive"))
    )
    (net (code "162") (name "Net-(U$1-GPIO2_22)") (class "Default")
      (node (ref "U$1") (pin "27") (pinfunction "GPIO2_22_27") (pintype "passive"))
      (node (ref "U$4") (pin "11") (pinfunction "11_11") (pintype "passive"))
    )
    (net (code "163") (name "Net-(U$1-GPIO2_23)") (class "Default")
      (node (ref "U$1") (pin "29") (pinfunction "GPIO2_23_29") (pintype "passive"))
      (node (ref "U$4") (pin "10") (pinfunction "10_10") (pintype "passive"))
    )
    (net (code "164") (name "Net-(U$1-PWR_BUT)") (class "Default")
      (node (ref "U$1") (pin "55") (pinfunction "PWR_BUT_55") (pintype "passive"))
      (node (ref "U$5") (pin "21") (pinfunction "21_21") (pintype "passive"))
    )
    (net (code "165") (name "Net-(U$1-SYS_5V-Pad53)") (class "Default")
      (node (ref "U$1") (pin "53") (pinfunction "SYS_5V_53") (pintype "power_in"))
      (node (ref "U$5") (pin "22") (pinfunction "22_22") (pintype "passive"))
    )
    (net (code "166") (name "Net-(U$1-SYS_5V-Pad54)") (class "Default")
      (node (ref "U$1") (pin "54") (pinfunction "SYS_5V_54") (pintype "passive"))
      (node (ref "U$2") (pin "22") (pinfunction "22_22") (pintype "passive"))
    )
    (net (code "167") (name "Net-(U$1-UART4_CTSN)") (class "Default")
      (node (ref "U$1") (pin "35") (pinfunction "UART4_CTSN_35") (pintype "passive"))
      (node (ref "U$4") (pin "7") (pinfunction "7_7") (pintype "passive"))
    )
    (net (code "168") (name "Net-(U$1-UART4_RTSN)") (class "Default")
      (node (ref "U$1") (pin "33") (pinfunction "UART4_RTSN_33") (pintype "passive"))
      (node (ref "U$4") (pin "8") (pinfunction "8_8") (pintype "passive"))
    )
    (net (code "169") (name "Net-(U1-DGS)") (class "Default")
      (node (ref "R1") (pin "2") (pinfunction "2_2") (pintype "passive"))
      (node (ref "R2") (pin "1") (pinfunction "1_1") (pintype "passive"))
      (node (ref "U1") (pin "3") (pinfunction "DGS_3") (pintype "output"))
    )
    (net (code "170") (name "Net-(U1-IN)") (class "Default")
      (node (ref "R3") (pin "2") (pinfunction "2_2") (pintype "passive"))
      (node (ref "U1") (pin "2") (pinfunction "IN_2") (pintype "input"))
    )
    (net (code "171") (name "Net-(U1-OUT)") (class "Default")
      (node (ref "R4") (pin "1") (pinfunction "1_1") (pintype "passive"))
      (node (ref "R5") (pin "1") (pinfunction "1_1") (pintype "passive"))
      (node (ref "U1") (pin "4") (pinfunction "OUT_4") (pintype "output"))
      (node (ref "U9") (pin "3") (pinfunction "VIN+_3") (pintype "bidirectional"))
    )
    (net (code "172") (name "Net-(U2-DGS)") (class "Default")
      (node (ref "R7") (pin "2") (pinfunction "2_2") (pintype "passive"))
      (node (ref "R8") (pin "1") (pinfunction "1_1") (pintype "passive"))
      (node (ref "U2") (pin "3") (pinfunction "DGS_3") (pintype "output"))
    )
    (net (code "173") (name "Net-(U2-IN)") (class "Default")
      (node (ref "R9") (pin "2") (pinfunction "2_2") (pintype "passive"))
      (node (ref "U2") (pin "2") (pinfunction "IN_2") (pintype "input"))
    )
    (net (code "174") (name "Net-(U2-OUT)") (class "Default")
      (node (ref "R10") (pin "1") (pinfunction "1_1") (pintype "passive"))
      (node (ref "R11") (pin "1") (pinfunction "1_1") (pintype "passive"))
      (node (ref "U2") (pin "4") (pinfunction "OUT_4") (pintype "output"))
      (node (ref "U3") (pin "3") (pinfunction "VIN+_3") (pintype "bidirectional"))
    )
    (net (code "175") (name "Net-(U4-DGS)") (class "Default")
      (node (ref "R13") (pin "2") (pinfunction "2_2") (pintype "passive"))
      (node (ref "R14") (pin "1") (pinfunction "1_1") (pintype "passive"))
      (node (ref "U4") (pin "3") (pinfunction "DGS_3") (pintype "output"))
    )
    (net (code "176") (name "Net-(U4-IN)") (class "Default")
      (node (ref "R15") (pin "2") (pinfunction "2_2") (pintype "passive"))
      (node (ref "U4") (pin "2") (pinfunction "IN_2") (pintype "input"))
    )
    (net (code "177") (name "Net-(U4-OUT)") (class "Default")
      (node (ref "R16") (pin "1") (pinfunction "1_1") (pintype "passive"))
      (node (ref "R17") (pin "1") (pinfunction "1_1") (pintype "passive"))
      (node (ref "U4") (pin "4") (pinfunction "OUT_4") (pintype "output"))
      (node (ref "U5") (pin "3") (pinfunction "VIN+_3") (pintype "bidirectional"))
    )
    (net (code "178") (name "Net-(U6-DGS)") (class "Default")
      (node (ref "R25") (pin "2") (pinfunction "2_2") (pintype "passive"))
      (node (ref "R29") (pin "1") (pinfunction "1_1") (pintype "passive"))
      (node (ref "U6") (pin "3") (pinfunction "DGS_3") (pintype "output"))
    )
    (net (code "179") (name "Net-(U6-IN)") (class "Default")
      (node (ref "R30") (pin "2") (pinfunction "2_2") (pintype "passive"))
      (node (ref "U6") (pin "2") (pinfunction "IN_2") (pintype "input"))
    )
    (net (code "180") (name "Net-(U6-OUT)") (class "Default")
      (node (ref "R31") (pin "1") (pinfunction "1_1") (pintype "passive"))
      (node (ref "R32") (pin "1") (pinfunction "1_1") (pintype "passive"))
      (node (ref "U6") (pin "4") (pinfunction "OUT_4") (pintype "output"))
      (node (ref "U7") (pin "3") (pinfunction "VIN+_3") (pintype "bidirectional"))
    )
    (net (code "181") (name "Net-(U8-DGS)") (class "Default")
      (node (ref "R34") (pin "2") (pinfunction "2_2") (pintype "passive"))
      (node (ref "R35") (pin "1") (pinfunction "1_1") (pintype "passive"))
      (node (ref "U8") (pin "3") (pinfunction "DGS_3") (pintype "output"))
    )
    (net (code "182") (name "Net-(U8-IN)") (class "Default")
      (node (ref "R36") (pin "2") (pinfunction "2_2") (pintype "passive"))
      (node (ref "U8") (pin "2") (pinfunction "IN_2") (pintype "input"))
    )
    (net (code "183") (name "Net-(U10-VIN+)") (class "Default")
      (node (ref "R37") (pin "1") (pinfunction "1_1") (pintype "passive"))
      (node (ref "R40") (pin "1") (pinfunction "1_1") (pintype "passive"))
      (node (ref "U10") (pin "3") (pinfunction "VIN+_3") (pintype "bidirectional"))
      (node (ref "U8") (pin "4") (pinfunction "OUT_4") (pintype "output"))
    )
    (net (code "184") (name "Net-(U11-DGS)") (class "Default")
      (node (ref "R42") (pin "2") (pinfunction "2_2") (pintype "passive"))
      (node (ref "R43") (pin "1") (pinfunction "1_1") (pintype "passive"))
      (node (ref "U11") (pin "3") (pinfunction "DGS_3") (pintype "output"))
    )
    (net (code "185") (name "Net-(U11-IN)") (class "Default")
      (node (ref "R44") (pin "2") (pinfunction "2_2") (pintype "passive"))
      (node (ref "U11") (pin "2") (pinfunction "IN_2") (pintype "input"))
    )
    (net (code "186") (name "Net-(U11-OUT)") (class "Default")
      (node (ref "R45") (pin "1") (pinfunction "1_1") (pintype "passive"))
      (node (ref "R46") (pin "1") (pinfunction "1_1") (pintype "passive"))
      (node (ref "U11") (pin "4") (pinfunction "OUT_4") (pintype "output"))
      (node (ref "U12") (pin "3") (pinfunction "VIN+_3") (pintype "bidirectional"))
    )
    (net (code "187") (name "Net-(U15-BOOT)") (class "Default")
      (node (ref "C32") (pin "2") (pinfunction "2_2") (pintype "passive"))
      (node (ref "U15") (pin "1") (pinfunction "BOOT_1") (pintype "bidirectional"))
    )
    (net (code "188") (name "Net-(U15-COMP)") (class "Default")
      (node (ref "C34") (pin "1") (pinfunction "1_1") (pintype "passive"))
      (node (ref "R26") (pin "2") (pinfunction "2_2") (pintype "passive"))
      (node (ref "U15") (pin "6") (pinfunction "COMP_6") (pintype "bidirectional"))
    )
    (net (code "189") (name "Net-(U15-PH)") (class "Default")
      (node (ref "C32") (pin "1") (pinfunction "1_1") (pintype "passive"))
      (node (ref "D36") (pin "C") (pinfunction "C_C") (pintype "passive"))
      (node (ref "L2") (pin "1") (pinfunction "1_1") (pintype "passive"))
      (node (ref "U15") (pin "8") (pinfunction "PH_8") (pintype "bidirectional"))
    )
    (net (code "190") (name "Net-(U15-SS)") (class "Default")
      (node (ref "C31") (pin "1") (pinfunction "1_1") (pintype "passive"))
      (node (ref "U15") (pin "4") (pinfunction "SS_4") (pintype "bidirectional"))
    )
    (net (code "191") (name "Net-(U15-VSENSE)") (class "Default")
      (node (ref "R27") (pin "1") (pinfunction "1_1") (pintype "passive"))
      (node (ref "R28") (pin "2") (pinfunction "2_2") (pintype "passive"))
      (node (ref "U15") (pin "5") (pinfunction "VSENSE_5") (pintype "bidirectional"))
    )
    (net (code "192") (name "Net-(U20-DGS)") (class "Default")
      (node (ref "R69") (pin "2") (pinfunction "2_2") (pintype "passive"))
      (node (ref "R70") (pin "1") (pinfunction "1_1") (pintype "passive"))
      (node (ref "U20") (pin "3") (pinfunction "DGS_3") (pintype "output"))
    )
    (net (code "193") (name "Net-(U20-IN)") (class "Default")
      (node (ref "R71") (pin "2") (pinfunction "2_2") (pintype "passive"))
      (node (ref "U20") (pin "2") (pinfunction "IN_2") (pintype "input"))
    )
    (net (code "194") (name "Net-(U20-OUT)") (class "Default")
      (node (ref "R72") (pin "1") (pinfunction "1_1") (pintype "passive"))
      (node (ref "R73") (pin "1") (pinfunction "1_1") (pintype "passive"))
      (node (ref "U20") (pin "4") (pinfunction "OUT_4") (pintype "output"))
      (node (ref "U21") (pin "3") (pinfunction "VIN+_3") (pintype "bidirectional"))
    )
    (net (code "195") (name "Net-(U22-DGS)") (class "Default")
      (node (ref "R75") (pin "2") (pinfunction "2_2") (pintype "passive"))
      (node (ref "R76") (pin "1") (pinfunction "1_1") (pintype "passive"))
      (node (ref "U22") (pin "3") (pinfunction "DGS_3") (pintype "output"))
    )
    (net (code "196") (name "Net-(U22-IN)") (class "Default")
      (node (ref "R77") (pin "2") (pinfunction "2_2") (pintype "passive"))
      (node (ref "U22") (pin "2") (pinfunction "IN_2") (pintype "input"))
    )
    (net (code "197") (name "Net-(U22-OUT)") (class "Default")
      (node (ref "R78") (pin "1") (pinfunction "1_1") (pintype "passive"))
      (node (ref "R79") (pin "1") (pinfunction "1_1") (pintype "passive"))
      (node (ref "U22") (pin "4") (pinfunction "OUT_4") (pintype "output"))
      (node (ref "U23") (pin "3") (pinfunction "VIN+_3") (pintype "bidirectional"))
    )
    (net (code "198") (name "Net-(U24-DGS)") (class "Default")
      (node (ref "R81") (pin "2") (pinfunction "2_2") (pintype "passive"))
      (node (ref "R82") (pin "1") (pinfunction "1_1") (pintype "passive"))
      (node (ref "U24") (pin "3") (pinfunction "DGS_3") (pintype "output"))
    )
    (net (code "199") (name "Net-(U24-IN)") (class "Default")
      (node (ref "R83") (pin "2") (pinfunction "2_2") (pintype "passive"))
      (node (ref "U24") (pin "2") (pinfunction "IN_2") (pintype "input"))
    )
    (net (code "200") (name "Net-(U24-OUT)") (class "Default")
      (node (ref "R84") (pin "1") (pinfunction "1_1") (pintype "passive"))
      (node (ref "R85") (pin "1") (pinfunction "1_1") (pintype "passive"))
      (node (ref "U24") (pin "4") (pinfunction "OUT_4") (pintype "output"))
      (node (ref "U25") (pin "3") (pinfunction "VIN+_3") (pintype "bidirectional"))
    )
    (net (code "201") (name "Net-(U27-VIN+)") (class "Default")
      (node (ref "C26") (pin "1") (pinfunction "1_1") (pintype "passive"))
      (node (ref "C27") (pin "1") (pinfunction "1_1") (pintype "passive"))
      (node (ref "L2") (pin "2") (pinfunction "2_2") (pintype "passive"))
      (node (ref "R27") (pin "2") (pinfunction "2_2") (pintype "passive"))
      (node (ref "R55") (pin "1") (pinfunction "1_1") (pintype "passive"))
      (node (ref "U27") (pin "3") (pinfunction "VIN+_3") (pintype "bidirectional"))
    )
    (net (code "202") (name "Net-(U29-COMP)") (class "Default")
      (node (ref "R59") (pin "2") (pinfunction "2_2") (pintype "passive"))
      (node (ref "U29") (pin "8") (pinfunction "COMP_8") (pintype "bidirectional"))
    )
    (net (code "203") (name "Net-(U29-EN)") (class "Default")
      (node (ref "15V-ENB") (pin "2") (pinfunction "2_2") (pintype "passive"))
      (node (ref "L3") (pin "1") (pinfunction "1_1") (pintype "passive"))
      (node (ref "U29") (pin "3") (pinfunction "VIN_3") (pintype "bidirectional"))
      (node (ref "U29") (pin "4") (pinfunction "EN_4") (pintype "bidirectional"))
    )
    (net (code "204") (name "Net-(U29-FB)") (class "Default")
      (node (ref "R60") (pin "1") (pinfunction "1_1") (pintype "passive"))
      (node (ref "R61") (pin "2") (pinfunction "2_2") (pintype "passive"))
      (node (ref "U29") (pin "9") (pinfunction "FB_9") (pintype "bidirectional"))
    )
    (net (code "205") (name "Net-(U29-FREQ)") (class "Default")
      (node (ref "R58") (pin "2") (pinfunction "2_2") (pintype "passive"))
      (node (ref "U29") (pin "10") (pinfunction "FREQ_10") (pintype "bidirectional"))
    )
    (net (code "206") (name "Net-(U29-SS)") (class "Default")
      (node (ref "C45") (pin "1") (pinfunction "1_1") (pintype "passive"))
      (node (ref "U29") (pin "5") (pinfunction "SS_5") (pintype "bidirectional"))
    )
    (net (code "207") (name "RELAY_CURRENT_0") (class "Default")
      (node (ref "R110") (pin "2") (pinfunction "2_2") (pintype "passive"))
      (node (ref "R6") (pin "2") (pinfunction "2_2") (pintype "passive"))
      (node (ref "U9") (pin "1") (pinfunction "OUT_1") (pintype "bidirectional"))
    )
    (net (code "208") (name "RELAY_CURRENT_1") (class "Default")
      (node (ref "R110") (pin "4") (pinfunction "2_4") (pintype "passive"))
      (node (ref "R12") (pin "2") (pinfunction "2_2") (pintype "passive"))
      (node (ref "U3") (pin "1") (pinfunction "OUT_1") (pintype "bidirectional"))
    )
    (net (code "209") (name "RELAY_CURRENT_2") (class "Default")
      (node (ref "R110") (pin "6") (pinfunction "2_6") (pintype "passive"))
      (node (ref "R18") (pin "2") (pinfunction "2_2") (pintype "passive"))
      (node (ref "U5") (pin "1") (pinfunction "OUT_1") (pintype "bidirectional"))
    )
    (net (code "210") (name "RELAY_CURRENT_3") (class "Default")
      (node (ref "R110") (pin "8") (pinfunction "2_8") (pintype "passive"))
      (node (ref "R33") (pin "2") (pinfunction "2_2") (pintype "passive"))
      (node (ref "U7") (pin "1") (pinfunction "OUT_1") (pintype "bidirectional"))
    )
    (net (code "211") (name "RELAY_CURRENT_4") (class "Default")
      (node (ref "R111") (pin "2") (pinfunction "2_2") (pintype "passive"))
      (node (ref "R41") (pin "2") (pinfunction "2_2") (pintype "passive"))
      (node (ref "U10") (pin "1") (pinfunction "OUT_1") (pintype "bidirectional"))
    )
    (net (code "212") (name "RELAY_CURRENT_5") (class "Default")
      (node (ref "R111") (pin "4") (pinfunction "2_4") (pintype "passive"))
      (node (ref "R47") (pin "2") (pinfunction "2_2") (pintype "passive"))
      (node (ref "U12") (pin "1") (pinfunction "OUT_1") (pintype "bidirectional"))
    )
    (net (code "213") (name "RELAY_CURRENT_DISARM") (class "Default")
      (node (ref "R111") (pin "6") (pinfunction "2_6") (pintype "passive"))
      (node (ref "R74") (pin "2") (pinfunction "2_2") (pintype "passive"))
      (node (ref "U21") (pin "1") (pinfunction "OUT_1") (pintype "bidirectional"))
    )
    (net (code "214") (name "RELAY_CURRENT_ENABLE") (class "Default")
      (node (ref "R111") (pin "8") (pinfunction "2_8") (pintype "passive"))
      (node (ref "R86") (pin "2") (pinfunction "2_2") (pintype "passive"))
      (node (ref "U25") (pin "1") (pinfunction "OUT_1") (pintype "bidirectional"))
    )
    (net (code "215") (name "RELAY_CURRENT_HORN") (class "Default")
      (node (ref "R112") (pin "2") (pinfunction "2_2") (pintype "passive"))
      (node (ref "R80") (pin "2") (pinfunction "2_2") (pintype "passive"))
      (node (ref "U23") (pin "1") (pinfunction "OUT_1") (pintype "bidirectional"))
    )
    (net (code "216") (name "RELAY_DISARM_3V3") (class "Default")
      (node (ref "U$1") (pin "15") (pinfunction "GPIO1_15_15") (pintype "passive"))
      (node (ref "U$4") (pin "17") (pinfunction "17_17") (pintype "passive"))
      (node (ref "U13") (pin "8") (pinfunction "A7_8") (pintype "bidirectional"))
    )
    (net (code "217") (name "RELAY_DISARM_5V") (class "Default")
      (node (ref "R71") (pin "1") (pinfunction "1_1") (pintype "passive"))
      (node (ref "U13") (pin "13") (pinfunction "B7_13") (pintype "bidirectional"))
    )
    (net (code "218") (name "RELAY_DISARM_FAULT") (class "Default")
      (node (ref "FAULT_DISARM") (pin "C") (pinfunction "C_C") (pintype "passive"))
      (node (ref "R69") (pin "1") (pinfunction "1_1") (pintype "passive"))
      (node (ref "U$1") (pin "16") (pinfunction "GPIO1_14_16") (pintype "passive"))
      (node (ref "U$3") (pin "17") (pinfunction "17_17") (pintype "passive"))
    )
    (net (code "219") (name "RELAY_ENABLE_3V3") (class "Default")
      (node (ref "U$1") (pin "24") (pinfunction "GPIO1_1_24") (pintype "passive"))
      (node (ref "U$3") (pin "13") (pinfunction "13_13") (pintype "passive"))
      (node (ref "U16") (pin "1") (pinfunction "A1_1") (pintype "bidirectional"))
    )
    (net (code "220") (name "RELAY_ENABLE_5V") (class "Default")
      (node (ref "R83") (pin "1") (pinfunction "1_1") (pintype "passive"))
      (node (ref "U16") (pin "20") (pinfunction "B1_20") (pintype "bidirectional"))
    )
    (net (code "221") (name "RELAY_ENABLE_FAULT") (class "Default")
      (node (ref "FAULT_ENABLE") (pin "C") (pinfunction "C_C") (pintype "passive"))
      (node (ref "R81") (pin "1") (pinfunction "1_1") (pintype "passive"))
      (node (ref "U$1") (pin "26") (pinfunction "GPIO1_29_26") (pintype "passive"))
      (node (ref "U$3") (pin "12") (pinfunction "12_12") (pintype "passive"))
    )
    (net (code "222") (name "RELAY_FAULT_0") (class "Default")
      (node (ref "FAULT_0") (pin "C") (pinfunction "C_C") (pintype "passive"))
      (node (ref "R1") (pin "1") (pinfunction "1_1") (pintype "passive"))
      (node (ref "U$1") (pin "4") (pinfunction "GPIO1_7_4") (pintype "passive"))
      (node (ref "U$3") (pin "23") (pinfunction "23_23") (pintype "passive"))
    )
    (net (code "223") (name "RELAY_FAULT_1") (class "Default")
      (node (ref "FAULT_1") (pin "C") (pinfunction "C_C") (pintype "passive"))
      (node (ref "R7") (pin "1") (pinfunction "1_1") (pintype "passive"))
      (node (ref "U$1") (pin "6") (pinfunction "GPIO1_3_6") (pintype "passive"))
      (node (ref "U$3") (pin "22") (pinfunction "22_22") (pintype "passive"))
    )
    (net (code "224") (name "RELAY_FAULT_2") (class "Default")
      (node (ref "FAULT_2") (pin "C") (pinfunction "C_C") (pintype "passive"))
      (node (ref "R13") (pin "1") (pinfunction "1_1") (pintype "passive"))
      (node (ref "U$1") (pin "8") (pinfunction "TIMER7_8") (pintype "passive"))
      (node (ref "U$3") (pin "21") (pinfunction "21_21") (pintype "passive"))
    )
    (net (code "225") (name "RELAY_FAULT_3") (class "Default")
      (node (ref "FAULT_3") (pin "C") (pinfunction "C_C") (pintype "passive"))
      (node (ref "R25") (pin "1") (pinfunction "1_1") (pintype "passive"))
      (node (ref "U$1") (pin "10") (pinfunction "TIMER6_10") (pintype "passive"))
      (node (ref "U$3") (pin "20") (pinfunction "20_20") (pintype "passive"))
    )
    (net (code "226") (name "RELAY_FAULT_4") (class "Default")
      (node (ref "FAULT_4") (pin "C") (pinfunction "C_C") (pintype "passive"))
      (node (ref "R34") (pin "1") (pinfunction "1_1") (pintype "passive"))
      (node (ref "U$1") (pin "12") (pinfunction "GPIO1_12_12") (pintype "passive"))
      (node (ref "U$3") (pin "19") (pinfunction "19_19") (pintype "passive"))
    )
    (net (code "227") (name "RELAY_FAULT_5") (class "Default")
      (node (ref "FAULT_5") (pin "C") (pinfunction "C_C") (pintype "passive"))
      (node (ref "R42") (pin "1") (pinfunction "1_1") (pintype "passive"))
      (node (ref "U$1") (pin "14") (pinfunction "GPIO0_26_14") (pintype "passive"))
      (node (ref "U$3") (pin "18") (pinfunction "18_18") (pintype "passive"))
    )
    (net (code "228") (name "RELAY_HORN_3V3") (class "Default")
      (node (ref "U$1") (pin "17") (pinfunction "GPIO0_27_17") (pintype "passive"))
      (node (ref "U$4") (pin "16") (pinfunction "16_16") (pintype "passive"))
      (node (ref "U13") (pin "9") (pinfunction "A8_9") (pintype "bidirectional"))
    )
    (net (code "229") (name "RELAY_HORN_5V") (class "Default")
      (node (ref "R77") (pin "1") (pinfunction "1_1") (pintype "passive"))
      (node (ref "U13") (pin "12") (pinfunction "B8_12") (pintype "bidirectional"))
    )
    (net (code "230") (name "RELAY_HORN_FAULT") (class "Default")
      (node (ref "FAULT_HORN") (pin "C") (pinfunction "C_C") (pintype "passive"))
      (node (ref "R75") (pin "1") (pinfunction "1_1") (pintype "passive"))
      (node (ref "U$1") (pin "18") (pinfunction "GPIO2_1_18") (pintype "passive"))
      (node (ref "U$3") (pin "16") (pinfunction "16_16") (pintype "passive"))
    )
    (net (code "231") (name "RELAY_IN_0_3V3") (class "Default")
      (node (ref "U$1") (pin "3") (pinfunction "GPIO1_6_3") (pintype "passive"))
      (node (ref "U$4") (pin "23") (pinfunction "23_23") (pintype "passive"))
      (node (ref "U13") (pin "1") (pinfunction "A1_1") (pintype "bidirectional"))
    )
    (net (code "232") (name "RELAY_IN_0_5V") (class "Default")
      (node (ref "R3") (pin "1") (pinfunction "1_1") (pintype "passive"))
      (node (ref "U13") (pin "20") (pinfunction "B1_20") (pintype "bidirectional"))
    )
    (net (code "233") (name "RELAY_IN_1_3V3") (class "Default")
      (node (ref "U$1") (pin "5") (pinfunction "GPIO1_2_5") (pintype "passive"))
      (node (ref "U$4") (pin "22") (pinfunction "22_22") (pintype "passive"))
      (node (ref "U13") (pin "3") (pinfunction "A2_3") (pintype "bidirectional"))
    )
    (net (code "234") (name "RELAY_IN_1_5V") (class "Default")
      (node (ref "R9") (pin "1") (pinfunction "1_1") (pintype "passive"))
      (node (ref "U13") (pin "18") (pinfunction "B2_18") (pintype "bidirectional"))
    )
    (net (code "235") (name "RELAY_IN_2_3V3") (class "Default")
      (node (ref "U$1") (pin "7") (pinfunction "TIMER4_7") (pintype "passive"))
      (node (ref "U$4") (pin "21") (pinfunction "21_21") (pintype "passive"))
      (node (ref "U13") (pin "4") (pinfunction "A3_4") (pintype "bidirectional"))
    )
    (net (code "236") (name "RELAY_IN_2_5V") (class "Default")
      (node (ref "R15") (pin "1") (pinfunction "1_1") (pintype "passive"))
      (node (ref "U13") (pin "17") (pinfunction "B3_17") (pintype "bidirectional"))
    )
    (net (code "237") (name "RELAY_IN_3_3V3") (class "Default")
      (node (ref "U$1") (pin "9") (pinfunction "TIMER5_9") (pintype "passive"))
      (node (ref "U$4") (pin "20") (pinfunction "20_20") (pintype "passive"))
      (node (ref "U13") (pin "5") (pinfunction "A4_5") (pintype "bidirectional"))
    )
    (net (code "238") (name "RELAY_IN_3_5V") (class "Default")
      (node (ref "R30") (pin "1") (pinfunction "1_1") (pintype "passive"))
      (node (ref "U13") (pin "16") (pinfunction "B4_16") (pintype "bidirectional"))
    )
    (net (code "239") (name "RELAY_IN_4_3V3") (class "Default")
      (node (ref "U$1") (pin "11") (pinfunction "GPIO1_13_11") (pintype "passive"))
      (node (ref "U$4") (pin "19") (pinfunction "19_19") (pintype "passive"))
      (node (ref "U13") (pin "6") (pinfunction "A5_6") (pintype "bidirectional"))
    )
    (net (code "240") (name "RELAY_IN_4_5V") (class "Default")
      (node (ref "R36") (pin "1") (pinfunction "1_1") (pintype "passive"))
      (node (ref "U13") (pin "15") (pinfunction "B5_15") (pintype "bidirectional"))
    )
    (net (code "241") (name "RELAY_IN_5_3V3") (class "Default")
      (node (ref "U$1") (pin "13") (pinfunction "EHRPWM2B_13") (pintype "passive"))
      (node (ref "U$4") (pin "18") (pinfunction "18_18") (pintype "passive"))
      (node (ref "U13") (pin "7") (pinfunction "A6_7") (pintype "bidirectional"))
    )
    (net (code "242") (name "RELAY_IN_5_5V") (class "Default")
      (node (ref "R44") (pin "1") (pinfunction "1_1") (pintype "passive"))
      (node (ref "U13") (pin "14") (pinfunction "B6_14") (pintype "bidirectional"))
    )
    (net (code "243") (name "RELAY_OUT_0") (class "Default")
      (node (ref "D1") (pin "A") (pinfunction "A_A") (pintype "passive"))
      (node (ref "D2") (pin "C") (pinfunction "C_C") (pintype "passive"))
      (node (ref "MOTOR-CTRL-RELAYS") (pin "1") (pinfunction "1_1") (pintype "passive"))
      (node (ref "R5") (pin "2") (pinfunction "2_2") (pintype "passive"))
      (node (ref "R62") (pin "2") (pinfunction "2_2") (pintype "passive"))
      (node (ref "U9") (pin "4") (pinfunction "VIN-_4") (pintype "bidirectional"))
    )
    (net (code "244") (name "RELAY_OUT_1") (class "Default")
      (node (ref "D3") (pin "A") (pinfunction "A_A") (pintype "passive"))
      (node (ref "D4") (pin "C") (pinfunction "C_C") (pintype "passive"))
      (node (ref "MOTOR-CTRL-RELAYS") (pin "3") (pinfunction "3_3") (pintype "passive"))
      (node (ref "R11") (pin "2") (pinfunction "2_2") (pintype "passive"))
      (node (ref "R63") (pin "2") (pinfunction "2_2") (pintype "passive"))
      (node (ref "U3") (pin "4") (pinfunction "VIN-_4") (pintype "bidirectional"))
    )
    (net (code "245") (name "RELAY_OUT_2") (class "Default")
      (node (ref "D5") (pin "A") (pinfunction "A_A") (pintype "passive"))
      (node (ref "D6") (pin "C") (pinfunction "C_C") (pintype "passive"))
      (node (ref "MOTOR-CTRL-RELAYS") (pin "5") (pinfunction "5_5") (pintype "passive"))
      (node (ref "R17") (pin "2") (pinfunction "2_2") (pintype "passive"))
      (node (ref "R64") (pin "2") (pinfunction "2_2") (pintype "passive"))
      (node (ref "U5") (pin "4") (pinfunction "VIN-_4") (pintype "bidirectional"))
    )
    (net (code "246") (name "RELAY_OUT_3") (class "Default")
      (node (ref "D11") (pin "A") (pinfunction "A_A") (pintype "passive"))
      (node (ref "D12") (pin "C") (pinfunction "C_C") (pintype "passive"))
      (node (ref "MOTOR-CTRL-RELAYS") (pin "6") (pinfunction "6_6") (pintype "passive"))
      (node (ref "R32") (pin "2") (pinfunction "2_2") (pintype "passive"))
      (node (ref "R65") (pin "2") (pinfunction "2_2") (pintype "passive"))
      (node (ref "U7") (pin "4") (pinfunction "VIN-_4") (pintype "bidirectional"))
    )
    (net (code "247") (name "RELAY_OUT_4") (class "Default")
      (node (ref "D10") (pin "A") (pinfunction "A_A") (pintype "passive"))
      (node (ref "D9") (pin "C") (pinfunction "C_C") (pintype "passive"))
      (node (ref "MOTOR-CTRL-RELAYS") (pin "8") (pinfunction "8_8") (pintype "passive"))
      (node (ref "R40") (pin "2") (pinfunction "2_2") (pintype "passive"))
      (node (ref "R66") (pin "2") (pinfunction "2_2") (pintype "passive"))
      (node (ref "U10") (pin "4") (pinfunction "VIN-_4") (pintype "bidirectional"))
    )
    (net (code "248") (name "RELAY_OUT_5") (class "Default")
      (node (ref "D7") (pin "C") (pinfunction "C_C") (pintype "passive"))
      (node (ref "D8") (pin "A") (pinfunction "A_A") (pintype "passive"))
      (node (ref "MOTOR-CTRL-RELAYS") (pin "9") (pinfunction "9_9") (pintype "passive"))
      (node (ref "R46") (pin "2") (pinfunction "2_2") (pintype "passive"))
      (node (ref "R67") (pin "2") (pinfunction "2_2") (pintype "passive"))
      (node (ref "U12") (pin "4") (pinfunction "VIN-_4") (pintype "bidirectional"))
    )
    (net (code "249") (name "RELAY_OUT_DISARM") (class "Default")
      (node (ref "D14") (pin "A") (pinfunction "A_A") (pintype "passive"))
      (node (ref "D15") (pin "C") (pinfunction "C_C") (pintype "passive"))
      (node (ref "ENABLE/DISARM") (pin "4") (pinfunction "4_4") (pintype "passive"))
      (node (ref "POWER_STATE") (pin "P$4") (pinfunction "4_P$4") (pintype "passive"))
      (node (ref "R68") (pin "2") (pinfunction "2_2") (pintype "passive"))
      (node (ref "R73") (pin "2") (pinfunction "2_2") (pintype "passive"))
      (node (ref "U21") (pin "4") (pinfunction "VIN-_4") (pintype "bidirectional"))
    )
    (net (code "250") (name "RELAY_OUT_ENABLE") (class "Default")
      (node (ref "D18") (pin "A") (pinfunction "A_A") (pintype "passive"))
      (node (ref "D19") (pin "C") (pinfunction "C_C") (pintype "passive"))
      (node (ref "R85") (pin "2") (pinfunction "2_2") (pintype "passive"))
      (node (ref "R87") (pin "2") (pinfunction "2_2") (pintype "passive"))
      (node (ref "SJ2") (pin "2") (pinfunction "2_2") (pintype "passive"))
      (node (ref "U25") (pin "4") (pinfunction "VIN-_4") (pintype "bidirectional"))
    )
    (net (code "251") (name "RS_485_DIR_SELECT_3V3") (class "Default")
      (node (ref "U$1") (pin "60") (pinfunction "EHRPWM1A_60") (pintype "passive"))
      (node (ref "U$2") (pin "19") (pinfunction "19_19") (pintype "passive"))
      (node (ref "U16") (pin "3") (pinfunction "A2_3") (pintype "bidirectional"))
    )
    (net (code "252") (name "RS_485_DIR_SELECT_5V") (class "Default")
      (node (ref "U16") (pin "18") (pinfunction "B2_18") (pintype "bidirectional"))
      (node (ref "U28") (pin "2") (pinfunction "/RE_2") (pintype "bidirectional"))
      (node (ref "U28") (pin "3") (pinfunction "DE_3") (pintype "bidirectional"))
    )
    (net (code "253") (name "SERVO_CURRENT_MON") (class "Default")
      (node (ref "R113") (pin "8") (pinfunction "2_8") (pintype "passive"))
      (node (ref "R56") (pin "2") (pinfunction "2_2") (pintype "passive"))
      (node (ref "U27") (pin "1") (pinfunction "OUT_1") (pintype "bidirectional"))
    )
    (net (code "254") (name "SERVO_ENABLE_3V3") (class "Default")
      (node (ref "U$1") (pin "19") (pinfunction "EHRPWM2A_19") (pintype "passive"))
      (node (ref "U$4") (pin "15") (pinfunction "15_15") (pintype "passive"))
      (node (ref "U16") (pin "4") (pinfunction "A3_4") (pintype "bidirectional"))
    )
    (net (code "255") (name "SERVO_ENABLE_5V") (class "Default")
      (node (ref "IC1") (pin "1") (pinfunction "I0_1") (pintype "input"))
      (node (ref "R97") (pin "1") (pinfunction "1_1") (pintype "passive"))
      (node (ref "U16") (pin "17") (pinfunction "B3_17") (pintype "bidirectional"))
    )
    (net (code "256") (name "SERVO_RUDDER_3V3") (class "Default")
      (node (ref "U$1") (pin "62") (pinfunction "EHRPWM1B_62") (pintype "passive"))
      (node (ref "U$2") (pin "18") (pinfunction "18_18") (pintype "passive"))
      (node (ref "U16") (pin "9") (pinfunction "A8_9") (pintype "bidirectional"))
    )
    (net (code "257") (name "SERVO_RUDDER_5V") (class "Default")
      (node (ref "D24") (pin "C") (pinfunction "C_C") (pintype "passive"))
      (node (ref "R92") (pin "2") (pinfunction "2_2") (pintype "passive"))
      (node (ref "U16") (pin "12") (pinfunction "B8_12") (pintype "bidirectional"))
    )
    (net (code "258") (name "unconnected-(BBB_CONSOLE-1-PadDTR)") (class "Default")
      (node (ref "BBB_CONSOLE") (pin "DTR") (pinfunction "1_DTR") (pintype "passive"))
    )
    (net (code "259") (name "unconnected-(BBB_CONSOLE-4-PadVCC)") (class "Default")
      (node (ref "BBB_CONSOLE") (pin "VCC") (pinfunction "4_VCC") (pintype "passive"))
    )
    (net (code "260") (name "unconnected-(BBB_CONSOLE-5-PadCTS)") (class "Default")
      (node (ref "BBB_CONSOLE") (pin "CTS") (pinfunction "5_CTS") (pintype "passive"))
    )
    (net (code "261") (name "unconnected-(J3-Pad1)") (class "Default")
      (node (ref "J3") (pin "1") (pinfunction "1_1") (pintype "passive"))
    )
    (net (code "262") (name "unconnected-(POE-LAN-Pad4)") (class "Default")
      (node (ref "POE-LAN") (pin "4") (pinfunction "4_4") (pintype "bidirectional"))
    )
    (net (code "263") (name "unconnected-(POE-LAN-Pad5)") (class "Default")
      (node (ref "POE-LAN") (pin "5") (pinfunction "5_5") (pintype "bidirectional"))
    )
    (net (code "264") (name "unconnected-(POE-LAN-Pad7)") (class "Default")
      (node (ref "POE-LAN") (pin "7") (pinfunction "7_7") (pintype "bidirectional"))
    )
    (net (code "265") (name "unconnected-(POE-LAN-Pad8)") (class "Default")
      (node (ref "POE-LAN") (pin "8") (pinfunction "8_8") (pintype "bidirectional"))
    )
    (net (code "266") (name "unconnected-(SERIAL_CONSOLE-1-PadP$1)") (class "Default")
      (node (ref "SERIAL_CONSOLE") (pin "P$1") (pinfunction "1_P$1") (pintype "passive"))
    )
    (net (code "267") (name "unconnected-(U18-~{INT}-Pad6)") (class "Default")
      (node (ref "U18") (pin "6") (pinfunction "~{INT}_6") (pintype "bidirectional"))
    )
    (net (code "268") (name "unconnected-(U19-~{INT}-Pad6)") (class "Default")
      (node (ref "U19") (pin "6") (pinfunction "~{INT}_6") (pintype "bidirectional"))
    )
  )
)
